# haasoscope_pro_fpga_board.net
KiCad netlist of a schematic drawn in EAGLE
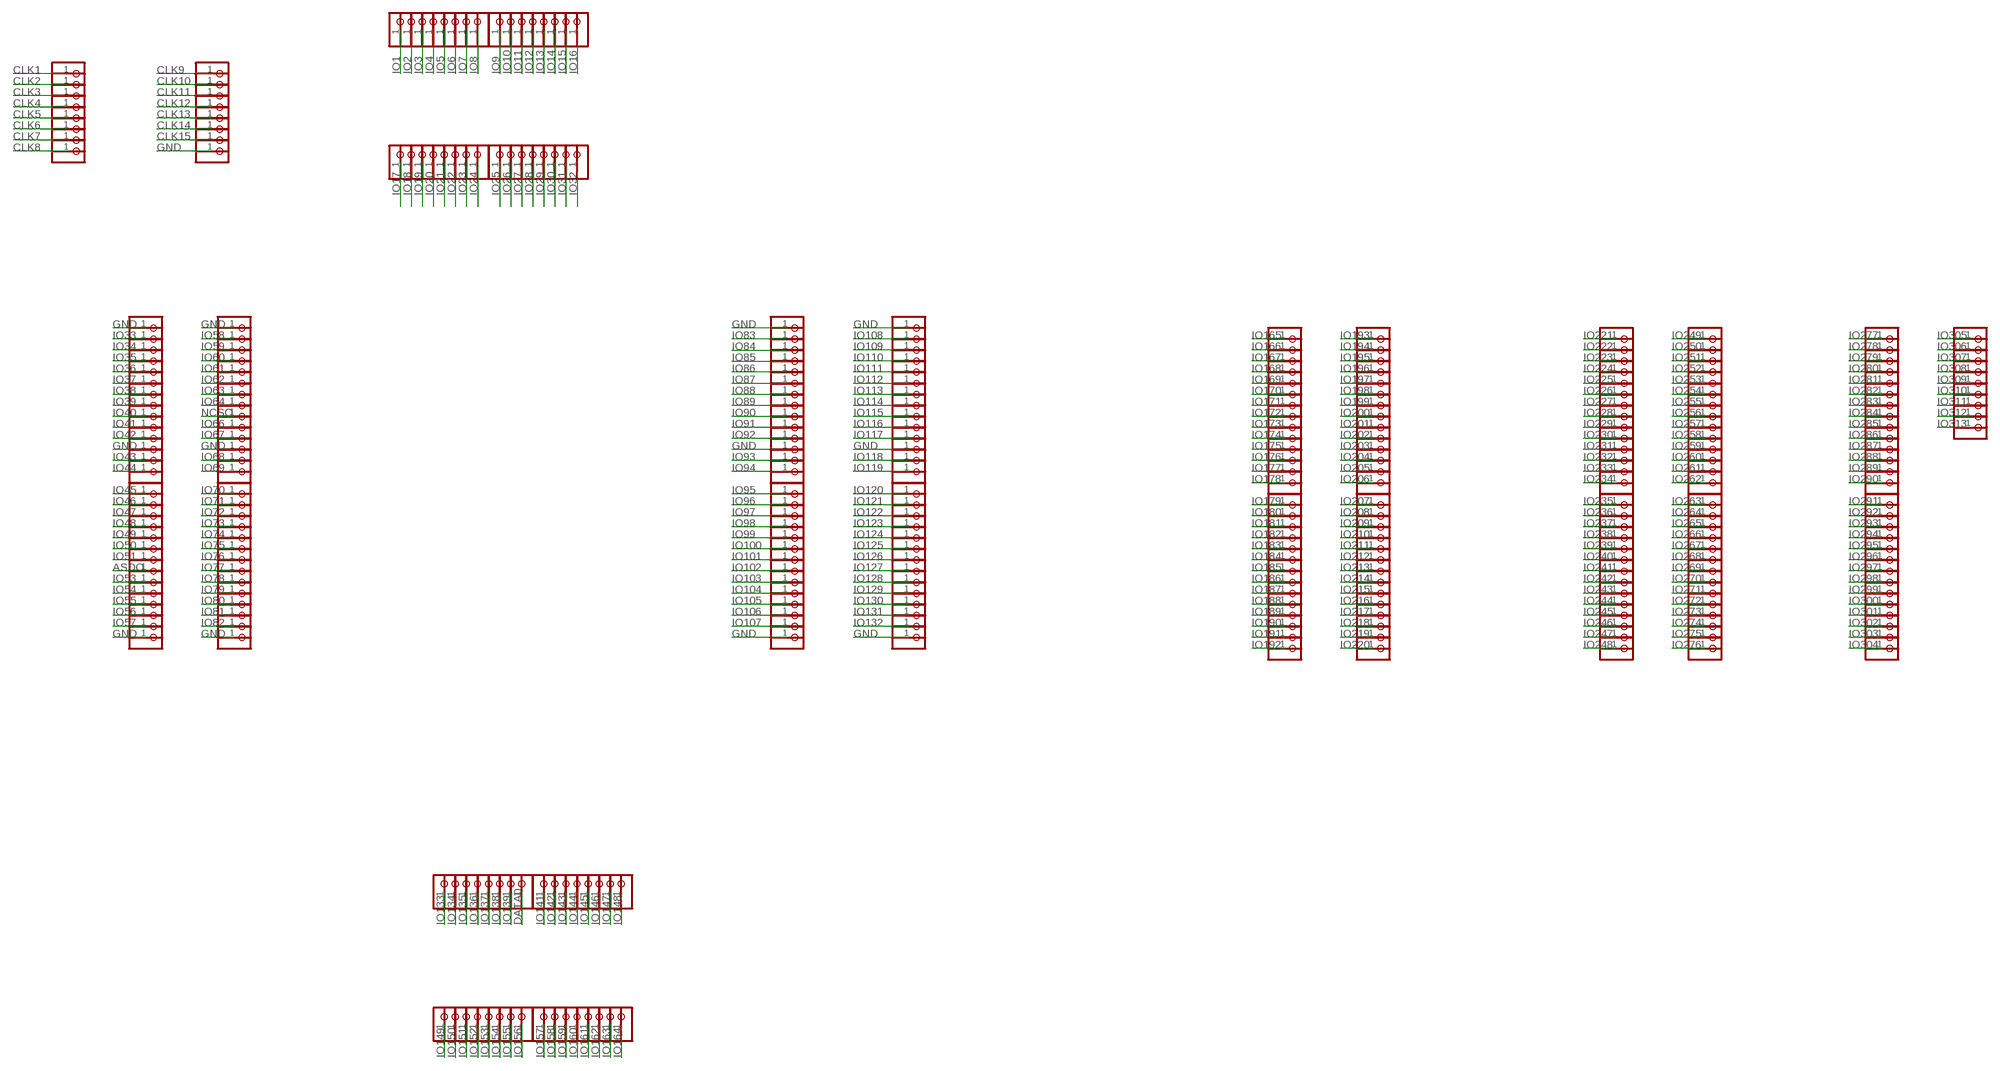
[diagram p0: schematic, sheet 1]
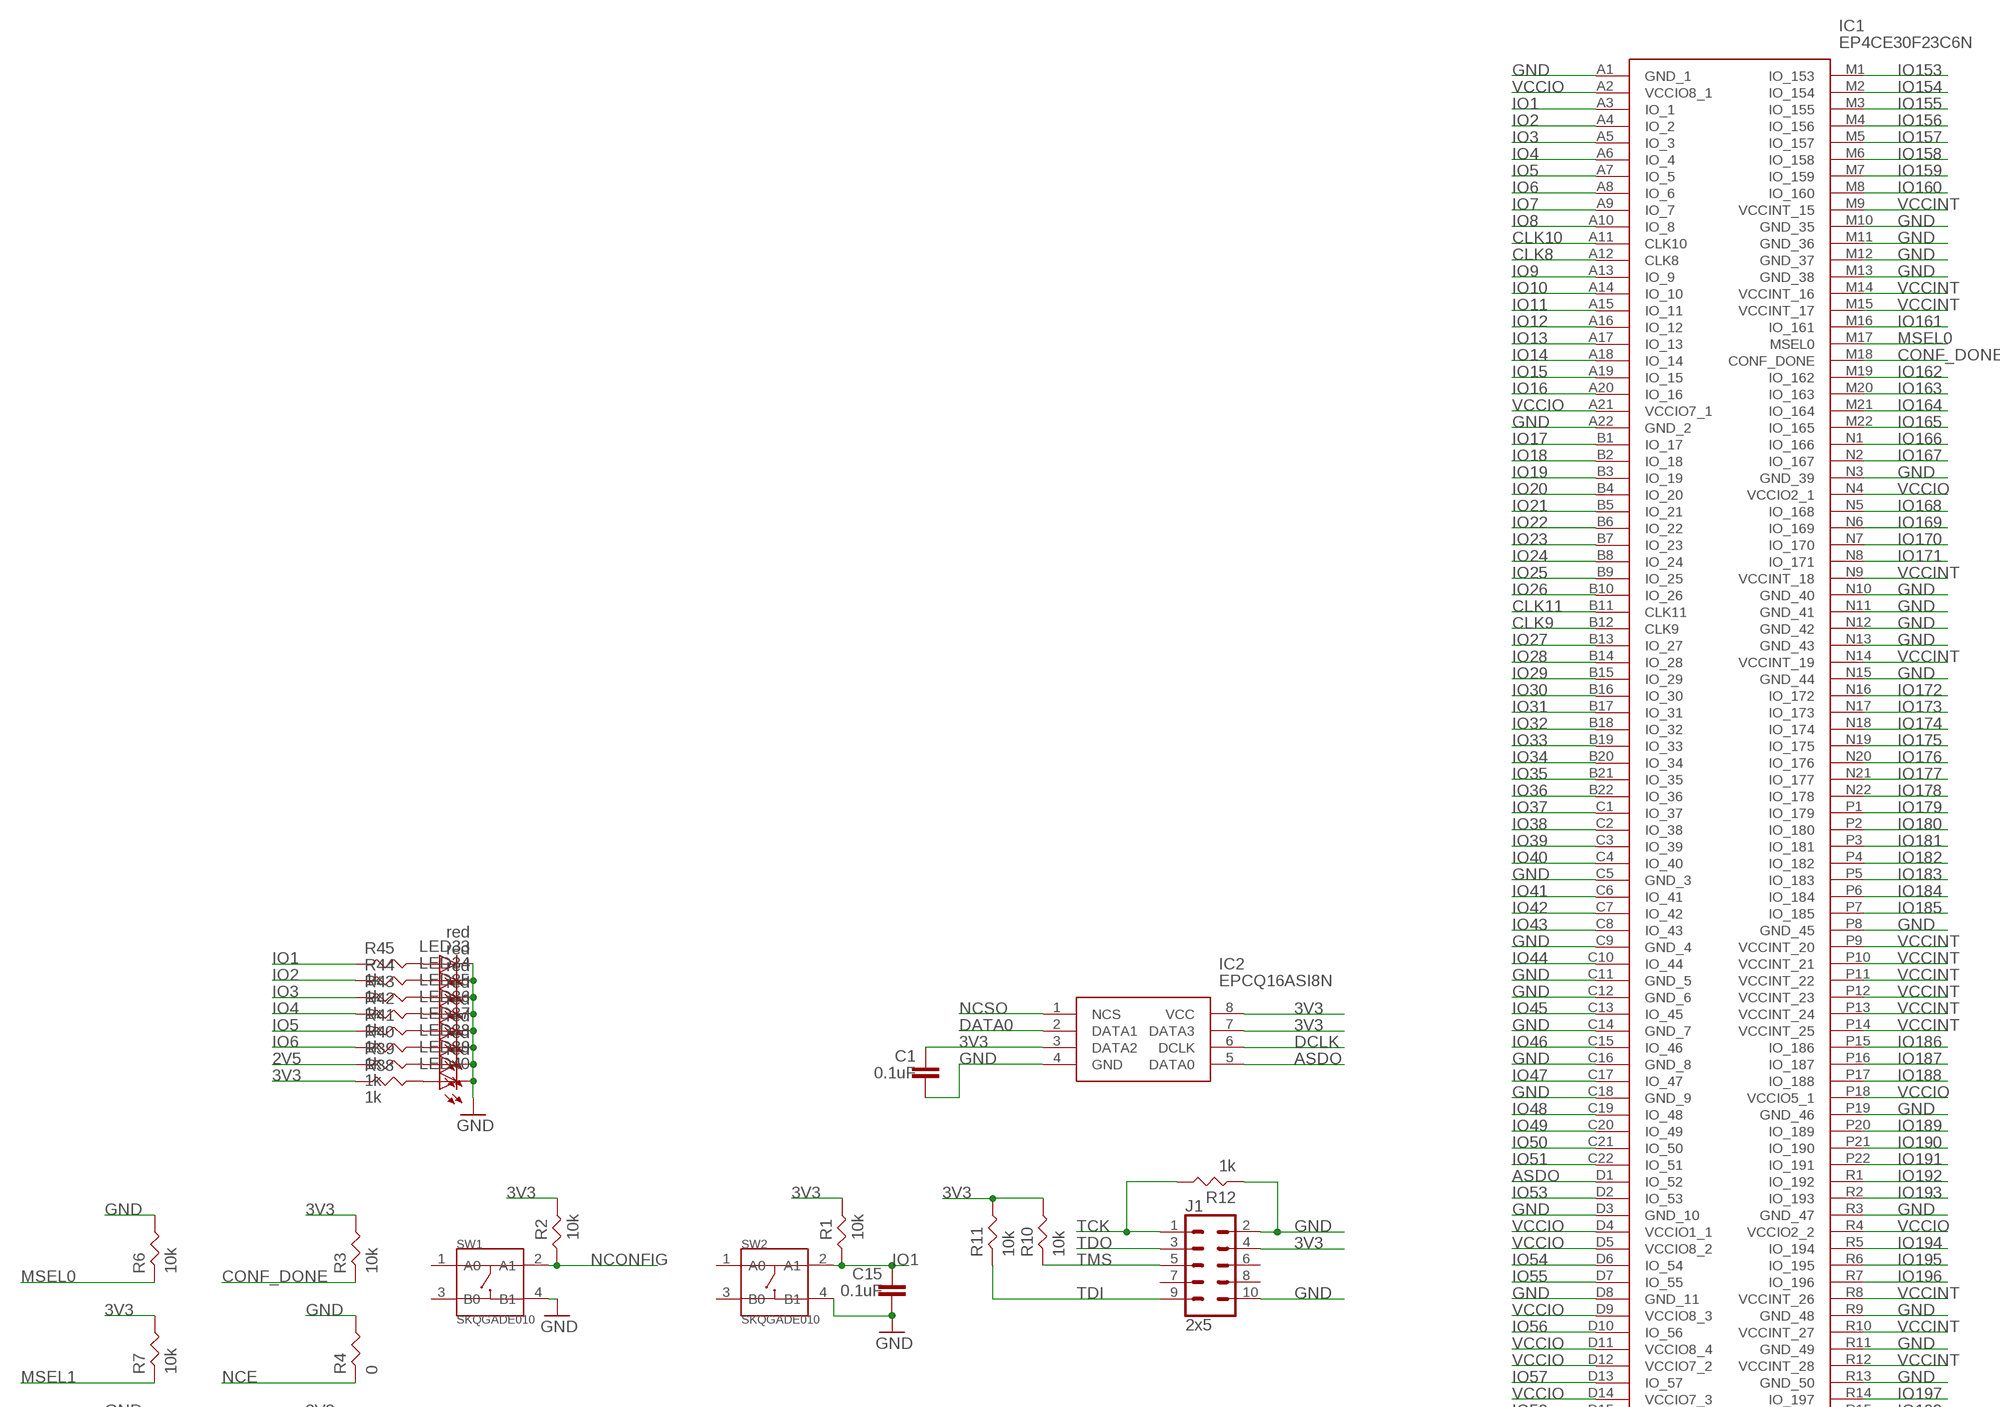
[diagram p1: schematic, sheet 2, part 1 of 2]
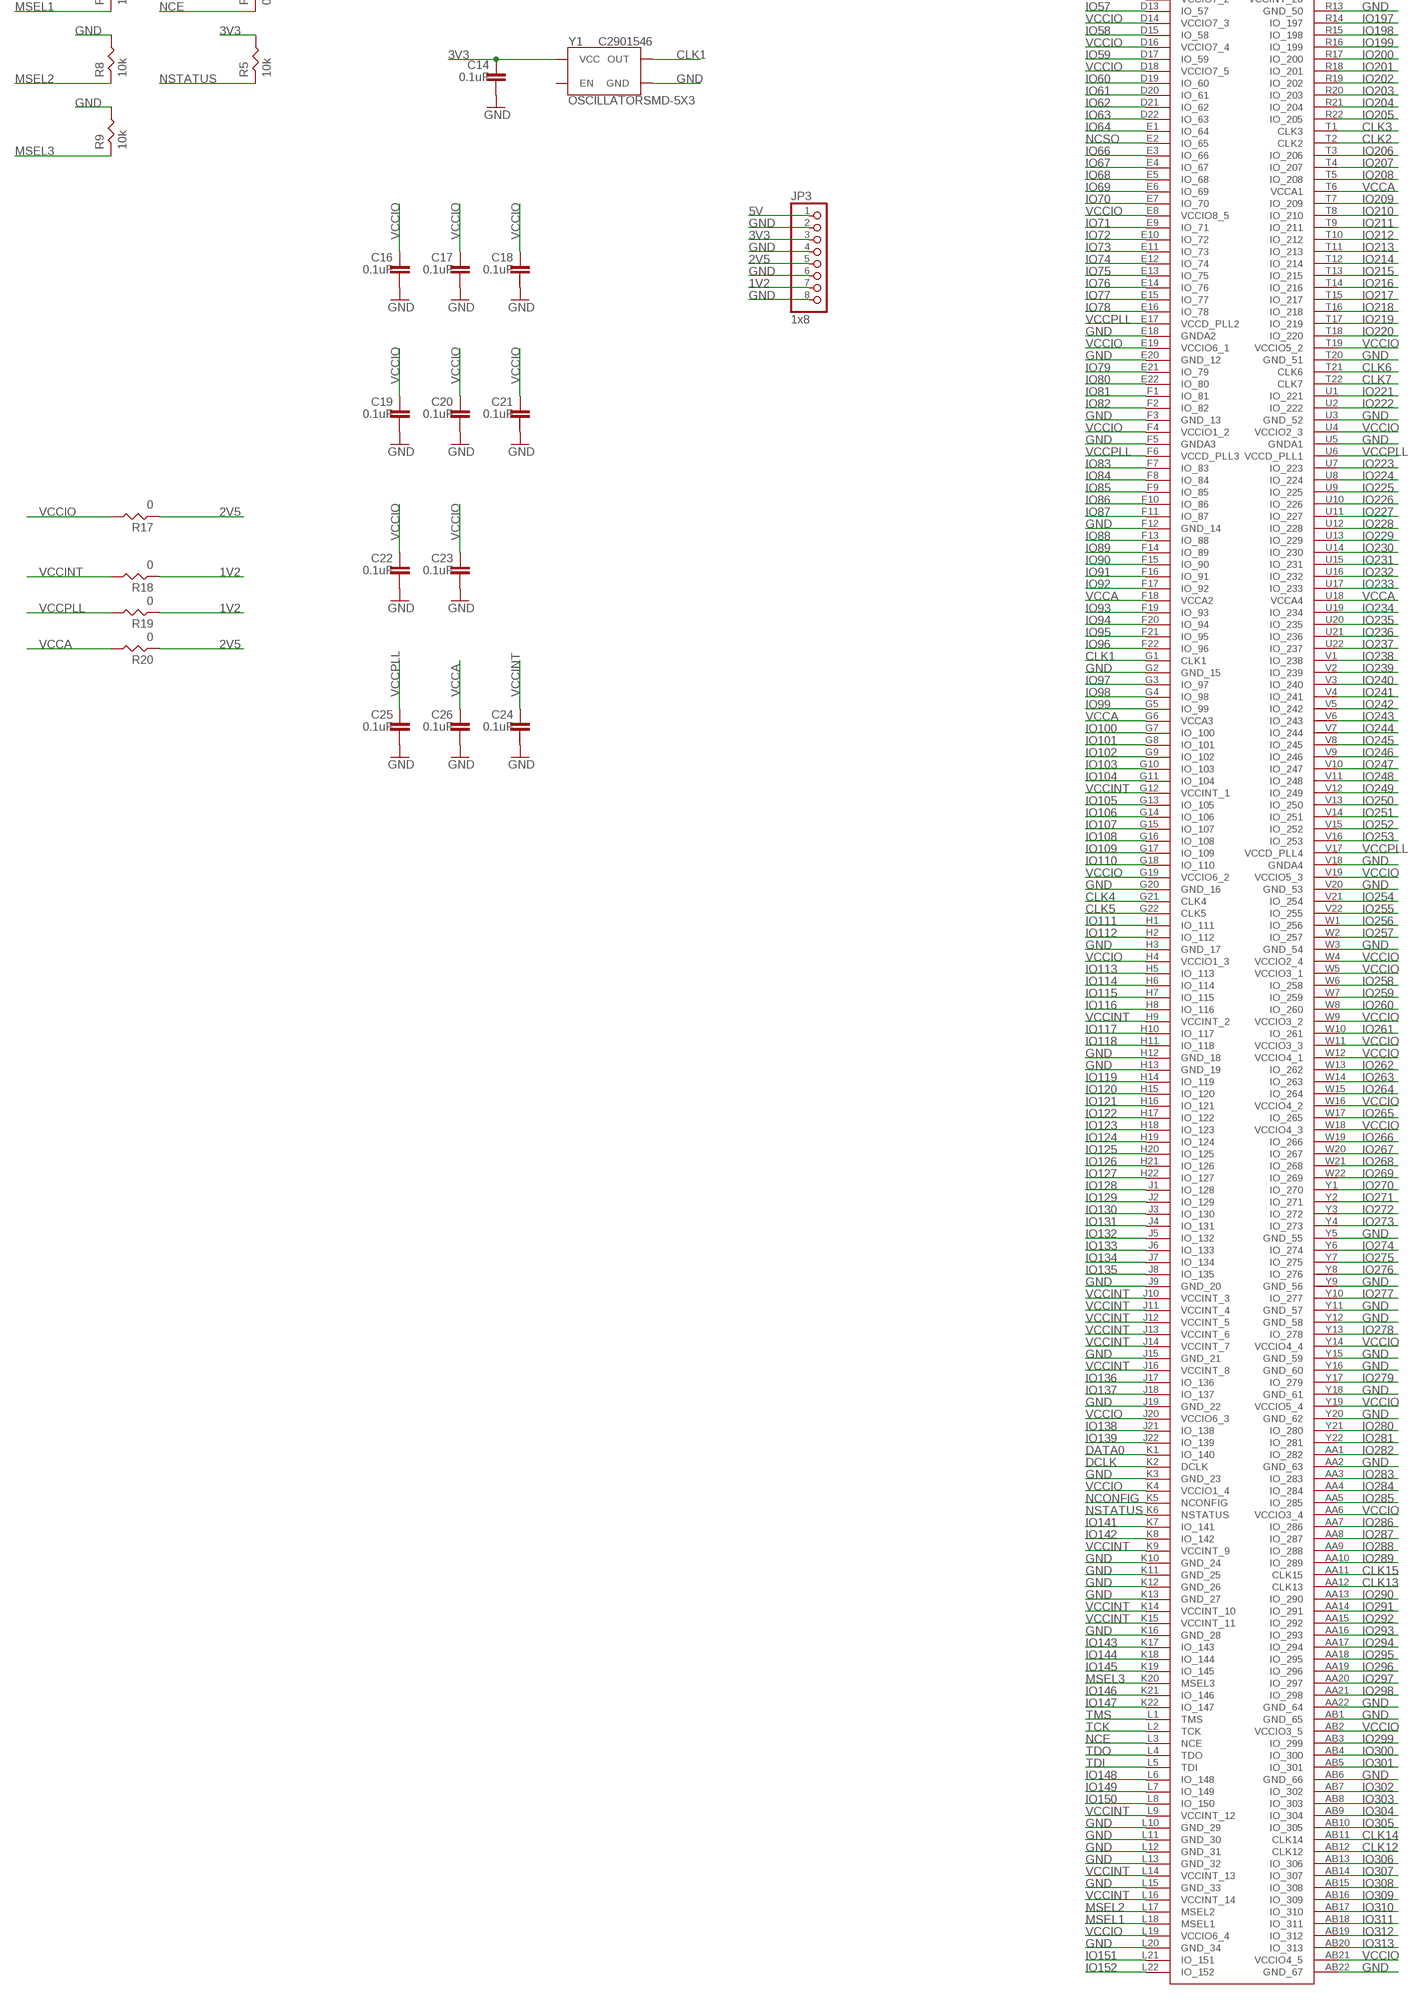
[diagram p2: schematic, sheet 2, part 2 of 2]
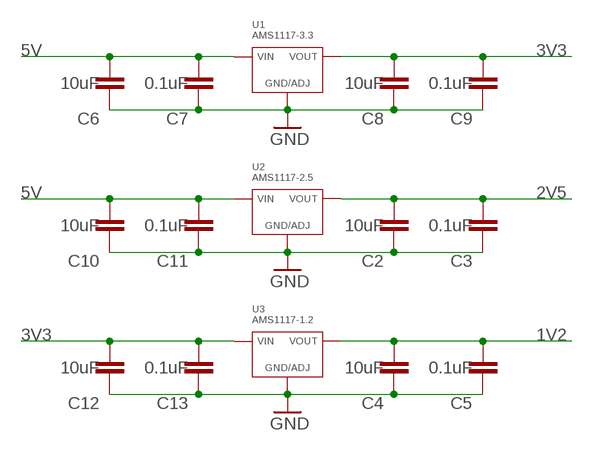
[diagram p3: schematic, sheet 3]

(export (version "E")
  (design (tool "Eeschema 10.0.6"))
  (components
    (comp (ref "C2")
      (value "10uF")
      (footprint "eagle-import:RESC0805_N")
      (libsource (lib "eagle-import") (part "CAPACITOR_0805_N"))
    )
    (comp (ref "C3")
      (value "0.1uF")
      (footprint "eagle-import:RESC0402_N")
      (libsource (lib "eagle-import") (part "CAPACITOR_0402_N"))
    )
    (comp (ref "C4")
      (value "10uF")
      (footprint "eagle-import:RESC0805_N")
      (libsource (lib "eagle-import") (part "CAPACITOR_0805_N"))
    )
    (comp (ref "C5")
      (value "0.1uF")
      (footprint "eagle-import:RESC0402_N")
      (libsource (lib "eagle-import") (part "CAPACITOR_0402_N"))
    )
    (comp (ref "C6")
      (value "10uF")
      (footprint "eagle-import:RESC0805_N")
      (libsource (lib "eagle-import") (part "CAPACITOR_0805_N"))
    )
    (comp (ref "C7")
      (value "0.1uF")
      (footprint "eagle-import:RESC0402_N")
      (libsource (lib "eagle-import") (part "CAPACITOR_0402_N"))
    )
    (comp (ref "C8")
      (value "10uF")
      (footprint "eagle-import:RESC0805_N")
      (libsource (lib "eagle-import") (part "CAPACITOR_0805_N"))
    )
    (comp (ref "C9")
      (value "0.1uF")
      (footprint "eagle-import:RESC0402_N")
      (libsource (lib "eagle-import") (part "CAPACITOR_0402_N"))
    )
    (comp (ref "C10")
      (value "10uF")
      (footprint "eagle-import:RESC0805_N")
      (libsource (lib "eagle-import") (part "CAPACITOR_0805_N"))
    )
    (comp (ref "C11")
      (value "0.1uF")
      (footprint "eagle-import:RESC0402_N")
      (libsource (lib "eagle-import") (part "CAPACITOR_0402_N"))
    )
    (comp (ref "C12")
      (value "10uF")
      (footprint "eagle-import:RESC0805_N")
      (libsource (lib "eagle-import") (part "CAPACITOR_0805_N"))
    )
    (comp (ref "C13")
      (value "0.1uF")
      (footprint "eagle-import:RESC0402_N")
      (libsource (lib "eagle-import") (part "CAPACITOR_0402_N"))
    )
    (comp (ref "U1")
      (value "AMS1117-3.3")
      (footprint "eagle-import:SOT-223-3")
      (fields
        (field (name "HOUSEPART") "NO")
        (field (name "MPN") "NCP1117LPST33T3G")
        (field (name "MPN_1") "AMS1117-3.3")
      )
      (libsource (lib "eagle-import") (part "NCP1117LPST33T3G"))
    )
    (comp (ref "U2")
      (value "AMS1117-2.5")
      (footprint "eagle-import:SOT-223-3")
      (fields
        (field (name "HOUSEPART") "NO")
        (field (name "MPN") "NCP1117LPST33T3G")
        (field (name "MPN_1") "AMS1117-2.5")
      )
      (libsource (lib "eagle-import") (part "NCP1117LPST33T3G"))
    )
    (comp (ref "U3")
      (value "AMS1117-1.2")
      (footprint "eagle-import:SOT-223-3")
      (fields
        (field (name "HOUSEPART") "NO")
        (field (name "MPN") "NCP1117LPST33T3G")
        (field (name "MPN_1") "AMS1117-1.2")
      )
      (libsource (lib "eagle-import") (part "NCP1117LPST33T3G"))
    )
    (comp (ref "C1")
      (value "0.1uF")
      (footprint "eagle-import:RESC0402_N")
      (libsource (lib "eagle-import") (part "CAPACITOR_0402_N"))
    )
    (comp (ref "C14")
      (value "0.1uF")
      (footprint "eagle-import:RESC0402_N")
      (libsource (lib "eagle-import") (part "CAPACITOR_0402_N"))
    )
    (comp (ref "C15")
      (value "0.1uF")
      (footprint "eagle-import:RESC0402_N")
      (libsource (lib "eagle-import") (part "CAPACITOR_0402_N"))
    )
    (comp (ref "C16")
      (value "0.1uF")
      (footprint "eagle-import:RESC0402_N")
      (libsource (lib "eagle-import") (part "CAPACITOR_0402_N"))
    )
    (comp (ref "C17")
      (value "0.1uF")
      (footprint "eagle-import:RESC0402_N")
      (libsource (lib "eagle-import") (part "CAPACITOR_0402_N"))
    )
    (comp (ref "C18")
      (value "0.1uF")
      (footprint "eagle-import:RESC0402_N")
      (libsource (lib "eagle-import") (part "CAPACITOR_0402_N"))
    )
    (comp (ref "C19")
      (value "0.1uF")
      (footprint "eagle-import:RESC0402_N")
      (libsource (lib "eagle-import") (part "CAPACITOR_0402_N"))
    )
    (comp (ref "C20")
      (value "0.1uF")
      (footprint "eagle-import:RESC0402_N")
      (libsource (lib "eagle-import") (part "CAPACITOR_0402_N"))
    )
    (comp (ref "C21")
      (value "0.1uF")
      (footprint "eagle-import:RESC0402_N")
      (libsource (lib "eagle-import") (part "CAPACITOR_0402_N"))
    )
    (comp (ref "C22")
      (value "0.1uF")
      (footprint "eagle-import:RESC0402_N")
      (libsource (lib "eagle-import") (part "CAPACITOR_0402_N"))
    )
    (comp (ref "C23")
      (value "0.1uF")
      (footprint "eagle-import:RESC0402_N")
      (libsource (lib "eagle-import") (part "CAPACITOR_0402_N"))
    )
    (comp (ref "C24")
      (value "0.1uF")
      (footprint "eagle-import:RESC0402_N")
      (libsource (lib "eagle-import") (part "CAPACITOR_0402_N"))
    )
    (comp (ref "C25")
      (value "0.1uF")
      (footprint "eagle-import:RESC0402_N")
      (libsource (lib "eagle-import") (part "CAPACITOR_0402_N"))
    )
    (comp (ref "C26")
      (value "0.1uF")
      (footprint "eagle-import:RESC0402_N")
      (libsource (lib "eagle-import") (part "CAPACITOR_0402_N"))
    )
    (comp (ref "IC1")
      (value "EP4CE30F23C6N")
      (footprint "eagle-import:BGA484C100P22X22_2300X2300X240")
      (fields (field (name "MOUSER_PART_NUMBER") "989-EP4CE30F23C6N"))
      (libsource (lib "eagle-import") (part "EP4CE30F23C6N"))
    )
    (comp (ref "IC2")
      (value "EPCQ16ASI8N")
      (footprint "eagle-import:SOIC127P600X175-8N")
      (fields (field (name "MOUSER_PART_NUMBER") "989-EPCQ16ASI8N"))
      (libsource (lib "eagle-import") (part "EPCQ16ASI8N"))
    )
    (comp (ref "J1")
      (value "2x5")
      (footprint "eagle-import:2X5-SHROUDED")
      (libsource (lib "eagle-import") (part "CONN_05X2SHD"))
    )
    (comp (ref "JP3")
      (value "1x8")
      (footprint "eagle-import:1X08")
      (libsource (lib "eagle-import") (part "PINHD-1X8"))
    )
    (comp (ref "LED33")
      (value "red")
      (footprint "eagle-import:CHIP-LED0603")
      (libsource (lib "eagle-import") (part "LEDCHIP-LED0603"))
    )
    (comp (ref "LED34")
      (value "red")
      (footprint "eagle-import:CHIP-LED0603")
      (libsource (lib "eagle-import") (part "LEDCHIP-LED0603"))
    )
    (comp (ref "LED35")
      (value "red")
      (footprint "eagle-import:CHIP-LED0603")
      (libsource (lib "eagle-import") (part "LEDCHIP-LED0603"))
    )
    (comp (ref "LED36")
      (value "red")
      (footprint "eagle-import:CHIP-LED0603")
      (libsource (lib "eagle-import") (part "LEDCHIP-LED0603"))
    )
    (comp (ref "LED37")
      (value "red")
      (footprint "eagle-import:CHIP-LED0603")
      (libsource (lib "eagle-import") (part "LEDCHIP-LED0603"))
    )
    (comp (ref "LED38")
      (value "red")
      (footprint "eagle-import:CHIP-LED0603")
      (libsource (lib "eagle-import") (part "LEDCHIP-LED0603"))
    )
    (comp (ref "LED39")
      (value "red")
      (footprint "eagle-import:CHIP-LED0603")
      (libsource (lib "eagle-import") (part "LEDCHIP-LED0603"))
    )
    (comp (ref "LED40")
      (value "red")
      (footprint "eagle-import:CHIP-LED0603")
      (libsource (lib "eagle-import") (part "LEDCHIP-LED0603"))
    )
    (comp (ref "R1")
      (value "10k")
      (footprint "eagle-import:RES-0402")
      (libsource (lib "eagle-import") (part "RES-0402"))
    )
    (comp (ref "R2")
      (value "10k")
      (footprint "eagle-import:RES-0402")
      (libsource (lib "eagle-import") (part "RES-0402"))
    )
    (comp (ref "R3")
      (value "10k")
      (footprint "eagle-import:RES-0402")
      (libsource (lib "eagle-import") (part "RES-0402"))
    )
    (comp (ref "R4")
      (value "0")
      (footprint "eagle-import:RES-0402")
      (libsource (lib "eagle-import") (part "RES-0402"))
    )
    (comp (ref "R5")
      (value "10k")
      (footprint "eagle-import:RES-0402")
      (libsource (lib "eagle-import") (part "RES-0402"))
    )
    (comp (ref "R6")
      (value "10k")
      (footprint "eagle-import:RES-0402")
      (libsource (lib "eagle-import") (part "RES-0402"))
    )
    (comp (ref "R7")
      (value "10k")
      (footprint "eagle-import:RES-0402")
      (libsource (lib "eagle-import") (part "RES-0402"))
    )
    (comp (ref "R8")
      (value "10k")
      (footprint "eagle-import:RES-0402")
      (libsource (lib "eagle-import") (part "RES-0402"))
    )
    (comp (ref "R9")
      (value "10k")
      (footprint "eagle-import:RES-0402")
      (libsource (lib "eagle-import") (part "RES-0402"))
    )
    (comp (ref "R10")
      (value "10k")
      (footprint "eagle-import:RES-0402")
      (libsource (lib "eagle-import") (part "RES-0402"))
    )
    (comp (ref "R11")
      (value "10k")
      (footprint "eagle-import:RES-0402")
      (libsource (lib "eagle-import") (part "RES-0402"))
    )
    (comp (ref "R12")
      (value "1k")
      (footprint "eagle-import:RES-0402")
      (libsource (lib "eagle-import") (part "RES-0402"))
    )
    (comp (ref "R17")
      (value "0")
      (footprint "eagle-import:RES-0402")
      (libsource (lib "eagle-import") (part "RES-0402"))
    )
    (comp (ref "R18")
      (value "0")
      (footprint "eagle-import:RES-0402")
      (libsource (lib "eagle-import") (part "RES-0402"))
    )
    (comp (ref "R19")
      (value "0")
      (footprint "eagle-import:RES-0402")
      (libsource (lib "eagle-import") (part "RES-0402"))
    )
    (comp (ref "R20")
      (value "0")
      (footprint "eagle-import:RES-0402")
      (libsource (lib "eagle-import") (part "RES-0402"))
    )
    (comp (ref "R38")
      (value "1k")
      (footprint "eagle-import:RES-0402")
      (libsource (lib "eagle-import") (part "RES-0402"))
    )
    (comp (ref "R39")
      (value "1k")
      (footprint "eagle-import:RES-0402")
      (libsource (lib "eagle-import") (part "RES-0402"))
    )
    (comp (ref "R40")
      (value "1k")
      (footprint "eagle-import:RES-0402")
      (libsource (lib "eagle-import") (part "RES-0402"))
    )
    (comp (ref "R41")
      (value "1k")
      (footprint "eagle-import:RES-0402")
      (libsource (lib "eagle-import") (part "RES-0402"))
    )
    (comp (ref "R42")
      (value "1k")
      (footprint "eagle-import:RES-0402")
      (libsource (lib "eagle-import") (part "RES-0402"))
    )
    (comp (ref "R43")
      (value "1k")
      (footprint "eagle-import:RES-0402")
      (libsource (lib "eagle-import") (part "RES-0402"))
    )
    (comp (ref "R44")
      (value "1k")
      (footprint "eagle-import:RES-0402")
      (libsource (lib "eagle-import") (part "RES-0402"))
    )
    (comp (ref "R45")
      (value "1k")
      (footprint "eagle-import:RES-0402")
      (libsource (lib "eagle-import") (part "RES-0402"))
    )
    (comp (ref "SW1")
      (value "SKQGADE010")
      (footprint "eagle-import:SW4-SMD-5.2X5.2X1.5MM")
      (libsource (lib "eagle-import") (part "SMD-BUTTON(4P-5.2X5.2X1.5MM-SKQGADE010)-SKQGADE010"))
    )
    (comp (ref "SW2")
      (value "SKQGADE010")
      (footprint "eagle-import:SW4-SMD-5.2X5.2X1.5MM")
      (libsource (lib "eagle-import") (part "SMD-BUTTON(4P-5.2X5.2X1.5MM-SKQGADE010)-SKQGADE010"))
    )
    (comp (ref "Y1")
      (value "OSCILLATORSMD-5X3")
      (footprint "eagle-import:OSCILLATOR-SMD-5X3.2")
      (fields (field (name "LCSC") "C2901546"))
      (libsource (lib "eagle-import") (part "OSCILLATORSMD-5X3"))
    )
    (comp (ref "JP1")
      (value "1")
      (footprint "eagle-import:1X01")
      (libsource (lib "eagle-import") (part "PINHD-1X1"))
    )
    (comp (ref "JP2")
      (value "1")
      (footprint "eagle-import:1X01")
      (libsource (lib "eagle-import") (part "PINHD-1X1"))
    )
    (comp (ref "JP4")
      (value "1")
      (footprint "eagle-import:1X01")
      (libsource (lib "eagle-import") (part "PINHD-1X1"))
    )
    (comp (ref "JP5")
      (value "1")
      (footprint "eagle-import:1X01")
      (libsource (lib "eagle-import") (part "PINHD-1X1"))
    )
    (comp (ref "JP6")
      (value "1")
      (footprint "eagle-import:1X01")
      (libsource (lib "eagle-import") (part "PINHD-1X1"))
    )
    (comp (ref "JP7")
      (value "1")
      (footprint "eagle-import:1X01")
      (libsource (lib "eagle-import") (part "PINHD-1X1"))
    )
    (comp (ref "JP8")
      (value "1")
      (footprint "eagle-import:1X01")
      (libsource (lib "eagle-import") (part "PINHD-1X1"))
    )
    (comp (ref "JP9")
      (value "1")
      (footprint "eagle-import:1X01")
      (libsource (lib "eagle-import") (part "PINHD-1X1"))
    )
    (comp (ref "JP10")
      (value "1")
      (footprint "eagle-import:1X01")
      (libsource (lib "eagle-import") (part "PINHD-1X1"))
    )
    (comp (ref "JP11")
      (value "1")
      (footprint "eagle-import:1X01")
      (libsource (lib "eagle-import") (part "PINHD-1X1"))
    )
    (comp (ref "JP12")
      (value "1")
      (footprint "eagle-import:1X01")
      (libsource (lib "eagle-import") (part "PINHD-1X1"))
    )
    (comp (ref "JP13")
      (value "1")
      (footprint "eagle-import:1X01")
      (libsource (lib "eagle-import") (part "PINHD-1X1"))
    )
    (comp (ref "JP14")
      (value "1")
      (footprint "eagle-import:1X01")
      (libsource (lib "eagle-import") (part "PINHD-1X1"))
    )
    (comp (ref "JP15")
      (value "1")
      (footprint "eagle-import:1X01")
      (libsource (lib "eagle-import") (part "PINHD-1X1"))
    )
    (comp (ref "JP16")
      (value "1")
      (footprint "eagle-import:1X01")
      (libsource (lib "eagle-import") (part "PINHD-1X1"))
    )
    (comp (ref "JP17")
      (value "1")
      (footprint "eagle-import:1X01")
      (libsource (lib "eagle-import") (part "PINHD-1X1"))
    )
    (comp (ref "JP18")
      (value "1")
      (footprint "eagle-import:1X01")
      (libsource (lib "eagle-import") (part "PINHD-1X1"))
    )
    (comp (ref "JP19")
      (value "1")
      (footprint "eagle-import:1X01")
      (libsource (lib "eagle-import") (part "PINHD-1X1"))
    )
    (comp (ref "JP20")
      (value "1")
      (footprint "eagle-import:1X01")
      (libsource (lib "eagle-import") (part "PINHD-1X1"))
    )
    (comp (ref "JP21")
      (value "1")
      (footprint "eagle-import:1X01")
      (libsource (lib "eagle-import") (part "PINHD-1X1"))
    )
    (comp (ref "JP22")
      (value "1")
      (footprint "eagle-import:1X01")
      (libsource (lib "eagle-import") (part "PINHD-1X1"))
    )
    (comp (ref "JP23")
      (value "1")
      (footprint "eagle-import:1X01")
      (libsource (lib "eagle-import") (part "PINHD-1X1"))
    )
    (comp (ref "JP24")
      (value "1")
      (footprint "eagle-import:1X01")
      (libsource (lib "eagle-import") (part "PINHD-1X1"))
    )
    (comp (ref "JP25")
      (value "1")
      (footprint "eagle-import:1X01")
      (libsource (lib "eagle-import") (part "PINHD-1X1"))
    )
    (comp (ref "JP26")
      (value "1")
      (footprint "eagle-import:1X01")
      (libsource (lib "eagle-import") (part "PINHD-1X1"))
    )
    (comp (ref "JP27")
      (value "1")
      (footprint "eagle-import:1X01")
      (libsource (lib "eagle-import") (part "PINHD-1X1"))
    )
    (comp (ref "JP28")
      (value "1")
      (footprint "eagle-import:1X01")
      (libsource (lib "eagle-import") (part "PINHD-1X1"))
    )
    (comp (ref "JP29")
      (value "1")
      (footprint "eagle-import:1X01")
      (libsource (lib "eagle-import") (part "PINHD-1X1"))
    )
    (comp (ref "JP30")
      (value "1")
      (footprint "eagle-import:1X01")
      (libsource (lib "eagle-import") (part "PINHD-1X1"))
    )
    (comp (ref "JP31")
      (value "1")
      (footprint "eagle-import:1X01")
      (libsource (lib "eagle-import") (part "PINHD-1X1"))
    )
    (comp (ref "JP32")
      (value "1")
      (footprint "eagle-import:1X01")
      (libsource (lib "eagle-import") (part "PINHD-1X1"))
    )
    (comp (ref "JP33")
      (value "1")
      (footprint "eagle-import:1X01")
      (libsource (lib "eagle-import") (part "PINHD-1X1"))
    )
    (comp (ref "JP34")
      (value "1")
      (footprint "eagle-import:1X01")
      (libsource (lib "eagle-import") (part "PINHD-1X1"))
    )
    (comp (ref "JP35")
      (value "1")
      (footprint "eagle-import:1X01")
      (libsource (lib "eagle-import") (part "PINHD-1X1"))
    )
    (comp (ref "JP36")
      (value "1")
      (footprint "eagle-import:1X01")
      (libsource (lib "eagle-import") (part "PINHD-1X1"))
    )
    (comp (ref "JP37")
      (value "1")
      (footprint "eagle-import:1X01")
      (libsource (lib "eagle-import") (part "PINHD-1X1"))
    )
    (comp (ref "JP38")
      (value "1")
      (footprint "eagle-import:1X01")
      (libsource (lib "eagle-import") (part "PINHD-1X1"))
    )
    (comp (ref "JP39")
      (value "1")
      (footprint "eagle-import:1X01")
      (libsource (lib "eagle-import") (part "PINHD-1X1"))
    )
    (comp (ref "JP40")
      (value "1")
      (footprint "eagle-import:1X01")
      (libsource (lib "eagle-import") (part "PINHD-1X1"))
    )
    (comp (ref "JP41")
      (value "1")
      (footprint "eagle-import:1X01")
      (libsource (lib "eagle-import") (part "PINHD-1X1"))
    )
    (comp (ref "JP42")
      (value "1")
      (footprint "eagle-import:1X01")
      (libsource (lib "eagle-import") (part "PINHD-1X1"))
    )
    (comp (ref "JP43")
      (value "1")
      (footprint "eagle-import:1X01")
      (libsource (lib "eagle-import") (part "PINHD-1X1"))
    )
    (comp (ref "JP44")
      (value "1")
      (footprint "eagle-import:1X01")
      (libsource (lib "eagle-import") (part "PINHD-1X1"))
    )
    (comp (ref "JP45")
      (value "1")
      (footprint "eagle-import:1X01")
      (libsource (lib "eagle-import") (part "PINHD-1X1"))
    )
    (comp (ref "JP46")
      (value "1")
      (footprint "eagle-import:1X01")
      (libsource (lib "eagle-import") (part "PINHD-1X1"))
    )
    (comp (ref "JP47")
      (value "1")
      (footprint "eagle-import:1X01")
      (libsource (lib "eagle-import") (part "PINHD-1X1"))
    )
    (comp (ref "JP48")
      (value "1")
      (footprint "eagle-import:1X01")
      (libsource (lib "eagle-import") (part "PINHD-1X1"))
    )
    (comp (ref "JP49")
      (value "1")
      (footprint "eagle-import:1X01")
      (libsource (lib "eagle-import") (part "PINHD-1X1"))
    )
    (comp (ref "JP50")
      (value "1")
      (footprint "eagle-import:1X01")
      (libsource (lib "eagle-import") (part "PINHD-1X1"))
    )
    (comp (ref "JP51")
      (value "1")
      (footprint "eagle-import:1X01")
      (libsource (lib "eagle-import") (part "PINHD-1X1"))
    )
    (comp (ref "JP52")
      (value "1")
      (footprint "eagle-import:1X01")
      (libsource (lib "eagle-import") (part "PINHD-1X1"))
    )
    (comp (ref "JP53")
      (value "1")
      (footprint "eagle-import:1X01")
      (libsource (lib "eagle-import") (part "PINHD-1X1"))
    )
    (comp (ref "JP54")
      (value "1")
      (footprint "eagle-import:1X01")
      (libsource (lib "eagle-import") (part "PINHD-1X1"))
    )
    (comp (ref "JP55")
      (value "1")
      (footprint "eagle-import:1X01")
      (libsource (lib "eagle-import") (part "PINHD-1X1"))
    )
    (comp (ref "JP56")
      (value "1")
      (footprint "eagle-import:1X01")
      (libsource (lib "eagle-import") (part "PINHD-1X1"))
    )
    (comp (ref "JP57")
      (value "1")
      (footprint "eagle-import:1X01")
      (libsource (lib "eagle-import") (part "PINHD-1X1"))
    )
    (comp (ref "JP58")
      (value "1")
      (footprint "eagle-import:1X01")
      (libsource (lib "eagle-import") (part "PINHD-1X1"))
    )
    (comp (ref "JP59")
      (value "1")
      (footprint "eagle-import:1X01")
      (libsource (lib "eagle-import") (part "PINHD-1X1"))
    )
    (comp (ref "JP60")
      (value "1")
      (footprint "eagle-import:1X01")
      (libsource (lib "eagle-import") (part "PINHD-1X1"))
    )
    (comp (ref "JP61")
      (value "1")
      (footprint "eagle-import:1X01")
      (libsource (lib "eagle-import") (part "PINHD-1X1"))
    )
    (comp (ref "JP62")
      (value "1")
      (footprint "eagle-import:1X01")
      (libsource (lib "eagle-import") (part "PINHD-1X1"))
    )
    (comp (ref "JP63")
      (value "1")
      (footprint "eagle-import:1X01")
      (libsource (lib "eagle-import") (part "PINHD-1X1"))
    )
    (comp (ref "JP64")
      (value "1")
      (footprint "eagle-import:1X01")
      (libsource (lib "eagle-import") (part "PINHD-1X1"))
    )
    (comp (ref "JP65")
      (value "1")
      (footprint "eagle-import:1X01")
      (libsource (lib "eagle-import") (part "PINHD-1X1"))
    )
    (comp (ref "JP66")
      (value "1")
      (footprint "eagle-import:1X01")
      (libsource (lib "eagle-import") (part "PINHD-1X1"))
    )
    (comp (ref "JP67")
      (value "1")
      (footprint "eagle-import:1X01")
      (libsource (lib "eagle-import") (part "PINHD-1X1"))
    )
    (comp (ref "JP68")
      (value "1")
      (footprint "eagle-import:1X01")
      (libsource (lib "eagle-import") (part "PINHD-1X1"))
    )
    (comp (ref "JP69")
      (value "1")
      (footprint "eagle-import:1X01")
      (libsource (lib "eagle-import") (part "PINHD-1X1"))
    )
    (comp (ref "JP70")
      (value "1")
      (footprint "eagle-import:1X01")
      (libsource (lib "eagle-import") (part "PINHD-1X1"))
    )
    (comp (ref "JP71")
      (value "1")
      (footprint "eagle-import:1X01")
      (libsource (lib "eagle-import") (part "PINHD-1X1"))
    )
    (comp (ref "JP72")
      (value "1")
      (footprint "eagle-import:1X01")
      (libsource (lib "eagle-import") (part "PINHD-1X1"))
    )
    (comp (ref "JP73")
      (value "1")
      (footprint "eagle-import:1X01")
      (libsource (lib "eagle-import") (part "PINHD-1X1"))
    )
    (comp (ref "JP74")
      (value "1")
      (footprint "eagle-import:1X01")
      (libsource (lib "eagle-import") (part "PINHD-1X1"))
    )
    (comp (ref "JP75")
      (value "1")
      (footprint "eagle-import:1X01")
      (libsource (lib "eagle-import") (part "PINHD-1X1"))
    )
    (comp (ref "JP76")
      (value "1")
      (footprint "eagle-import:1X01")
      (libsource (lib "eagle-import") (part "PINHD-1X1"))
    )
    (comp (ref "JP77")
      (value "1")
      (footprint "eagle-import:1X01")
      (libsource (lib "eagle-import") (part "PINHD-1X1"))
    )
    (comp (ref "JP78")
      (value "1")
      (footprint "eagle-import:1X01")
      (libsource (lib "eagle-import") (part "PINHD-1X1"))
    )
    (comp (ref "JP79")
      (value "1")
      (footprint "eagle-import:1X01")
      (libsource (lib "eagle-import") (part "PINHD-1X1"))
    )
    (comp (ref "JP80")
      (value "1")
      (footprint "eagle-import:1X01")
      (libsource (lib "eagle-import") (part "PINHD-1X1"))
    )
    (comp (ref "JP81")
      (value "1")
      (footprint "eagle-import:1X01")
      (libsource (lib "eagle-import") (part "PINHD-1X1"))
    )
    (comp (ref "JP82")
      (value "1")
      (footprint "eagle-import:1X01")
      (libsource (lib "eagle-import") (part "PINHD-1X1"))
    )
    (comp (ref "JP83")
      (value "1")
      (footprint "eagle-import:1X01")
      (libsource (lib "eagle-import") (part "PINHD-1X1"))
    )
    (comp (ref "JP84")
      (value "1")
      (footprint "eagle-import:1X01")
      (libsource (lib "eagle-import") (part "PINHD-1X1"))
    )
    (comp (ref "JP85")
      (value "1")
      (footprint "eagle-import:1X01")
      (libsource (lib "eagle-import") (part "PINHD-1X1"))
    )
    (comp (ref "JP86")
      (value "1")
      (footprint "eagle-import:1X01")
      (libsource (lib "eagle-import") (part "PINHD-1X1"))
    )
    (comp (ref "JP87")
      (value "1")
      (footprint "eagle-import:1X01")
      (libsource (lib "eagle-import") (part "PINHD-1X1"))
    )
    (comp (ref "JP88")
      (value "1")
      (footprint "eagle-import:1X01")
      (libsource (lib "eagle-import") (part "PINHD-1X1"))
    )
    (comp (ref "JP89")
      (value "1")
      (footprint "eagle-import:1X01")
      (libsource (lib "eagle-import") (part "PINHD-1X1"))
    )
    (comp (ref "JP90")
      (value "1")
      (footprint "eagle-import:1X01")
      (libsource (lib "eagle-import") (part "PINHD-1X1"))
    )
    (comp (ref "JP91")
      (value "1")
      (footprint "eagle-import:1X01")
      (libsource (lib "eagle-import") (part "PINHD-1X1"))
    )
    (comp (ref "JP92")
      (value "1")
      (footprint "eagle-import:1X01")
      (libsource (lib "eagle-import") (part "PINHD-1X1"))
    )
    (comp (ref "JP93")
      (value "1")
      (footprint "eagle-import:1X01")
      (libsource (lib "eagle-import") (part "PINHD-1X1"))
    )
    (comp (ref "JP94")
      (value "1")
      (footprint "eagle-import:1X01")
      (libsource (lib "eagle-import") (part "PINHD-1X1"))
    )
    (comp (ref "JP95")
      (value "1")
      (footprint "eagle-import:1X01")
      (libsource (lib "eagle-import") (part "PINHD-1X1"))
    )
    (comp (ref "JP96")
      (value "1")
      (footprint "eagle-import:1X01")
      (libsource (lib "eagle-import") (part "PINHD-1X1"))
    )
    (comp (ref "JP97")
      (value "1")
      (footprint "eagle-import:1X01")
      (libsource (lib "eagle-import") (part "PINHD-1X1"))
    )
    (comp (ref "JP98")
      (value "1")
      (footprint "eagle-import:1X01")
      (libsource (lib "eagle-import") (part "PINHD-1X1"))
    )
    (comp (ref "JP99")
      (value "1")
      (footprint "eagle-import:1X01")
      (libsource (lib "eagle-import") (part "PINHD-1X1"))
    )
    (comp (ref "JP100")
      (value "1")
      (footprint "eagle-import:1X01")
      (libsource (lib "eagle-import") (part "PINHD-1X1"))
    )
    (comp (ref "JP101")
      (value "1")
      (footprint "eagle-import:1X01")
      (libsource (lib "eagle-import") (part "PINHD-1X1"))
    )
    (comp (ref "JP102")
      (value "1")
      (footprint "eagle-import:1X01")
      (libsource (lib "eagle-import") (part "PINHD-1X1"))
    )
    (comp (ref "JP103")
      (value "1")
      (footprint "eagle-import:1X01")
      (libsource (lib "eagle-import") (part "PINHD-1X1"))
    )
    (comp (ref "JP104")
      (value "1")
      (footprint "eagle-import:1X01")
      (libsource (lib "eagle-import") (part "PINHD-1X1"))
    )
    (comp (ref "JP105")
      (value "1")
      (footprint "eagle-import:1X01")
      (libsource (lib "eagle-import") (part "PINHD-1X1"))
    )
    (comp (ref "JP106")
      (value "1")
      (footprint "eagle-import:1X01")
      (libsource (lib "eagle-import") (part "PINHD-1X1"))
    )
    (comp (ref "JP107")
      (value "1")
      (footprint "eagle-import:1X01")
      (libsource (lib "eagle-import") (part "PINHD-1X1"))
    )
    (comp (ref "JP108")
      (value "1")
      (footprint "eagle-import:1X01")
      (libsource (lib "eagle-import") (part "PINHD-1X1"))
    )
    (comp (ref "JP109")
      (value "1")
      (footprint "eagle-import:1X01")
      (libsource (lib "eagle-import") (part "PINHD-1X1"))
    )
    (comp (ref "JP110")
      (value "1")
      (footprint "eagle-import:1X01")
      (libsource (lib "eagle-import") (part "PINHD-1X1"))
    )
    (comp (ref "JP111")
      (value "1")
      (footprint "eagle-import:1X01")
      (libsource (lib "eagle-import") (part "PINHD-1X1"))
    )
    (comp (ref "JP112")
      (value "1")
      (footprint "eagle-import:1X01")
      (libsource (lib "eagle-import") (part "PINHD-1X1"))
    )
    (comp (ref "JP113")
      (value "1")
      (footprint "eagle-import:1X01")
      (libsource (lib "eagle-import") (part "PINHD-1X1"))
    )
    (comp (ref "JP114")
      (value "1")
      (footprint "eagle-import:1X01")
      (libsource (lib "eagle-import") (part "PINHD-1X1"))
    )
    (comp (ref "JP115")
      (value "1")
      (footprint "eagle-import:1X01")
      (libsource (lib "eagle-import") (part "PINHD-1X1"))
    )
    (comp (ref "JP116")
      (value "1")
      (footprint "eagle-import:1X01")
      (libsource (lib "eagle-import") (part "PINHD-1X1"))
    )
    (comp (ref "JP117")
      (value "1")
      (footprint "eagle-import:1X01")
      (libsource (lib "eagle-import") (part "PINHD-1X1"))
    )
    (comp (ref "JP118")
      (value "1")
      (footprint "eagle-import:1X01")
      (libsource (lib "eagle-import") (part "PINHD-1X1"))
    )
    (comp (ref "JP119")
      (value "1")
      (footprint "eagle-import:1X01")
      (libsource (lib "eagle-import") (part "PINHD-1X1"))
    )
    (comp (ref "JP120")
      (value "1")
      (footprint "eagle-import:1X01")
      (libsource (lib "eagle-import") (part "PINHD-1X1"))
    )
    (comp (ref "JP121")
      (value "1")
      (footprint "eagle-import:1X01")
      (libsource (lib "eagle-import") (part "PINHD-1X1"))
    )
    (comp (ref "JP122")
      (value "1")
      (footprint "eagle-import:1X01")
      (libsource (lib "eagle-import") (part "PINHD-1X1"))
    )
    (comp (ref "JP123")
      (value "1")
      (footprint "eagle-import:1X01")
      (libsource (lib "eagle-import") (part "PINHD-1X1"))
    )
    (comp (ref "JP124")
      (value "1")
      (footprint "eagle-import:1X01")
      (libsource (lib "eagle-import") (part "PINHD-1X1"))
    )
    (comp (ref "JP125")
      (value "1")
      (footprint "eagle-import:1X01")
      (libsource (lib "eagle-import") (part "PINHD-1X1"))
    )
    (comp (ref "JP126")
      (value "1")
      (footprint "eagle-import:1X01")
      (libsource (lib "eagle-import") (part "PINHD-1X1"))
    )
    (comp (ref "JP127")
      (value "1")
      (footprint "eagle-import:1X01")
      (libsource (lib "eagle-import") (part "PINHD-1X1"))
    )
    (comp (ref "JP128")
      (value "1")
      (footprint "eagle-import:1X01")
      (libsource (lib "eagle-import") (part "PINHD-1X1"))
    )
    (comp (ref "JP129")
      (value "1")
      (footprint "eagle-import:1X01")
      (libsource (lib "eagle-import") (part "PINHD-1X1"))
    )
    (comp (ref "JP130")
      (value "1")
      (footprint "eagle-import:1X01")
      (libsource (lib "eagle-import") (part "PINHD-1X1"))
    )
    (comp (ref "JP131")
      (value "1")
      (footprint "eagle-import:1X01")
      (libsource (lib "eagle-import") (part "PINHD-1X1"))
    )
    (comp (ref "JP132")
      (value "1")
      (footprint "eagle-import:1X01")
      (libsource (lib "eagle-import") (part "PINHD-1X1"))
    )
    (comp (ref "JP133")
      (value "1")
      (footprint "eagle-import:1X01")
      (libsource (lib "eagle-import") (part "PINHD-1X1"))
    )
    (comp (ref "JP134")
      (value "1")
      (footprint "eagle-import:1X01")
      (libsource (lib "eagle-import") (part "PINHD-1X1"))
    )
    (comp (ref "JP135")
      (value "1")
      (footprint "eagle-import:1X01")
      (libsource (lib "eagle-import") (part "PINHD-1X1"))
    )
    (comp (ref "JP136")
      (value "1")
      (footprint "eagle-import:1X01")
      (libsource (lib "eagle-import") (part "PINHD-1X1"))
    )
    (comp (ref "JP137")
      (value "1")
      (footprint "eagle-import:1X01")
      (libsource (lib "eagle-import") (part "PINHD-1X1"))
    )
    (comp (ref "JP138")
      (value "1")
      (footprint "eagle-import:1X01")
      (libsource (lib "eagle-import") (part "PINHD-1X1"))
    )
    (comp (ref "JP139")
      (value "1")
      (footprint "eagle-import:1X01")
      (libsource (lib "eagle-import") (part "PINHD-1X1"))
    )
    (comp (ref "JP140")
      (value "1")
      (footprint "eagle-import:1X01")
      (libsource (lib "eagle-import") (part "PINHD-1X1"))
    )
    (comp (ref "JP141")
      (value "1")
      (footprint "eagle-import:1X01")
      (libsource (lib "eagle-import") (part "PINHD-1X1"))
    )
    (comp (ref "JP142")
      (value "1")
      (footprint "eagle-import:1X01")
      (libsource (lib "eagle-import") (part "PINHD-1X1"))
    )
    (comp (ref "JP143")
      (value "1")
      (footprint "eagle-import:1X01")
      (libsource (lib "eagle-import") (part "PINHD-1X1"))
    )
    (comp (ref "JP144")
      (value "1")
      (footprint "eagle-import:1X01")
      (libsource (lib "eagle-import") (part "PINHD-1X1"))
    )
    (comp (ref "JP145")
      (value "1")
      (footprint "eagle-import:1X01")
      (libsource (lib "eagle-import") (part "PINHD-1X1"))
    )
    (comp (ref "JP146")
      (value "1")
      (footprint "eagle-import:1X01")
      (libsource (lib "eagle-import") (part "PINHD-1X1"))
    )
    (comp (ref "JP147")
      (value "1")
      (footprint "eagle-import:1X01")
      (libsource (lib "eagle-import") (part "PINHD-1X1"))
    )
    (comp (ref "JP148")
      (value "1")
      (footprint "eagle-import:1X01")
      (libsource (lib "eagle-import") (part "PINHD-1X1"))
    )
    (comp (ref "JP149")
      (value "1")
      (footprint "eagle-import:1X01")
      (libsource (lib "eagle-import") (part "PINHD-1X1"))
    )
    (comp (ref "JP150")
      (value "1")
      (footprint "eagle-import:1X01")
      (libsource (lib "eagle-import") (part "PINHD-1X1"))
    )
    (comp (ref "JP151")
      (value "1")
      (footprint "eagle-import:1X01")
      (libsource (lib "eagle-import") (part "PINHD-1X1"))
    )
    (comp (ref "JP152")
      (value "1")
      (footprint "eagle-import:1X01")
      (libsource (lib "eagle-import") (part "PINHD-1X1"))
    )
    (comp (ref "JP153")
      (value "1")
      (footprint "eagle-import:1X01")
      (libsource (lib "eagle-import") (part "PINHD-1X1"))
    )
    (comp (ref "JP154")
      (value "1")
      (footprint "eagle-import:1X01")
      (libsource (lib "eagle-import") (part "PINHD-1X1"))
    )
    (comp (ref "JP155")
      (value "1")
      (footprint "eagle-import:1X01")
      (libsource (lib "eagle-import") (part "PINHD-1X1"))
    )
    (comp (ref "JP156")
      (value "1")
      (footprint "eagle-import:1X01")
      (libsource (lib "eagle-import") (part "PINHD-1X1"))
    )
    (comp (ref "JP157")
      (value "1")
      (footprint "eagle-import:1X01")
      (libsource (lib "eagle-import") (part "PINHD-1X1"))
    )
    (comp (ref "JP158")
      (value "1")
      (footprint "eagle-import:1X01")
      (libsource (lib "eagle-import") (part "PINHD-1X1"))
    )
    (comp (ref "JP159")
      (value "1")
      (footprint "eagle-import:1X01")
      (libsource (lib "eagle-import") (part "PINHD-1X1"))
    )
    (comp (ref "JP160")
      (value "1")
      (footprint "eagle-import:1X01")
      (libsource (lib "eagle-import") (part "PINHD-1X1"))
    )
    (comp (ref "JP161")
      (value "1")
      (footprint "eagle-import:1X01")
      (libsource (lib "eagle-import") (part "PINHD-1X1"))
    )
    (comp (ref "JP162")
      (value "1")
      (footprint "eagle-import:1X01")
      (libsource (lib "eagle-import") (part "PINHD-1X1"))
    )
    (comp (ref "JP163")
      (value "1")
      (footprint "eagle-import:1X01")
      (libsource (lib "eagle-import") (part "PINHD-1X1"))
    )
    (comp (ref "JP164")
      (value "1")
      (footprint "eagle-import:1X01")
      (libsource (lib "eagle-import") (part "PINHD-1X1"))
    )
    (comp (ref "JP165")
      (value "1")
      (footprint "eagle-import:1X01")
      (libsource (lib "eagle-import") (part "PINHD-1X1"))
    )
    (comp (ref "JP166")
      (value "1")
      (footprint "eagle-import:1X01")
      (libsource (lib "eagle-import") (part "PINHD-1X1"))
    )
    (comp (ref "JP167")
      (value "1")
      (footprint "eagle-import:1X01")
      (libsource (lib "eagle-import") (part "PINHD-1X1"))
    )
    (comp (ref "JP168")
      (value "1")
      (footprint "eagle-import:1X01")
      (libsource (lib "eagle-import") (part "PINHD-1X1"))
    )
    (comp (ref "JP169")
      (value "1")
      (footprint "eagle-import:1X01")
      (libsource (lib "eagle-import") (part "PINHD-1X1"))
    )
    (comp (ref "JP170")
      (value "1")
      (footprint "eagle-import:1X01")
      (libsource (lib "eagle-import") (part "PINHD-1X1"))
    )
    (comp (ref "JP171")
      (value "1")
      (footprint "eagle-import:1X01")
      (libsource (lib "eagle-import") (part "PINHD-1X1"))
    )
    (comp (ref "JP172")
      (value "1")
      (footprint "eagle-import:1X01")
      (libsource (lib "eagle-import") (part "PINHD-1X1"))
    )
    (comp (ref "JP173")
      (value "1")
      (footprint "eagle-import:1X01")
      (libsource (lib "eagle-import") (part "PINHD-1X1"))
    )
    (comp (ref "JP174")
      (value "1")
      (footprint "eagle-import:1X01")
      (libsource (lib "eagle-import") (part "PINHD-1X1"))
    )
    (comp (ref "JP175")
      (value "1")
      (footprint "eagle-import:1X01")
      (libsource (lib "eagle-import") (part "PINHD-1X1"))
    )
    (comp (ref "JP176")
      (value "1")
      (footprint "eagle-import:1X01")
      (libsource (lib "eagle-import") (part "PINHD-1X1"))
    )
    (comp (ref "JP177")
      (value "1")
      (footprint "eagle-import:1X01")
      (libsource (lib "eagle-import") (part "PINHD-1X1"))
    )
    (comp (ref "JP178")
      (value "1")
      (footprint "eagle-import:1X01")
      (libsource (lib "eagle-import") (part "PINHD-1X1"))
    )
    (comp (ref "JP179")
      (value "1")
      (footprint "eagle-import:1X01")
      (libsource (lib "eagle-import") (part "PINHD-1X1"))
    )
    (comp (ref "JP180")
      (value "1")
      (footprint "eagle-import:1X01")
      (libsource (lib "eagle-import") (part "PINHD-1X1"))
    )
    (comp (ref "JP181")
      (value "1")
      (footprint "eagle-import:1X01")
      (libsource (lib "eagle-import") (part "PINHD-1X1"))
    )
    (comp (ref "JP182")
      (value "1")
      (footprint "eagle-import:1X01")
      (libsource (lib "eagle-import") (part "PINHD-1X1"))
    )
    (comp (ref "JP183")
      (value "1")
      (footprint "eagle-import:1X01")
      (libsource (lib "eagle-import") (part "PINHD-1X1"))
    )
    (comp (ref "JP184")
      (value "1")
      (footprint "eagle-import:1X01")
      (libsource (lib "eagle-import") (part "PINHD-1X1"))
    )
    (comp (ref "JP185")
      (value "1")
      (footprint "eagle-import:1X01")
      (libsource (lib "eagle-import") (part "PINHD-1X1"))
    )
    (comp (ref "JP186")
      (value "1")
      (footprint "eagle-import:1X01")
      (libsource (lib "eagle-import") (part "PINHD-1X1"))
    )
    (comp (ref "JP187")
      (value "1")
      (footprint "eagle-import:1X01")
      (libsource (lib "eagle-import") (part "PINHD-1X1"))
    )
    (comp (ref "JP188")
      (value "1")
      (footprint "eagle-import:1X01")
      (libsource (lib "eagle-import") (part "PINHD-1X1"))
    )
    (comp (ref "JP189")
      (value "1")
      (footprint "eagle-import:1X01")
      (libsource (lib "eagle-import") (part "PINHD-1X1"))
    )
    (comp (ref "JP190")
      (value "1")
      (footprint "eagle-import:1X01")
      (libsource (lib "eagle-import") (part "PINHD-1X1"))
    )
    (comp (ref "JP191")
      (value "1")
      (footprint "eagle-import:1X01")
      (libsource (lib "eagle-import") (part "PINHD-1X1"))
    )
    (comp (ref "JP192")
      (value "1")
      (footprint "eagle-import:1X01")
      (libsource (lib "eagle-import") (part "PINHD-1X1"))
    )
    (comp (ref "JP193")
      (value "1")
      (footprint "eagle-import:1X01")
      (libsource (lib "eagle-import") (part "PINHD-1X1"))
    )
    (comp (ref "JP194")
      (value "1")
      (footprint "eagle-import:1X01")
      (libsource (lib "eagle-import") (part "PINHD-1X1"))
    )
    (comp (ref "JP195")
      (value "1")
      (footprint "eagle-import:1X01")
      (libsource (lib "eagle-import") (part "PINHD-1X1"))
    )
    (comp (ref "JP196")
      (value "1")
      (footprint "eagle-import:1X01")
      (libsource (lib "eagle-import") (part "PINHD-1X1"))
    )
    (comp (ref "JP197")
      (value "1")
      (footprint "eagle-import:1X01")
      (libsource (lib "eagle-import") (part "PINHD-1X1"))
    )
    (comp (ref "JP198")
      (value "1")
      (footprint "eagle-import:1X01")
      (libsource (lib "eagle-import") (part "PINHD-1X1"))
    )
    (comp (ref "JP199")
      (value "1")
      (footprint "eagle-import:1X01")
      (libsource (lib "eagle-import") (part "PINHD-1X1"))
    )
    (comp (ref "JP200")
      (value "1")
      (footprint "eagle-import:1X01")
      (libsource (lib "eagle-import") (part "PINHD-1X1"))
    )
    (comp (ref "JP201")
      (value "1")
      (footprint "eagle-import:1X01")
      (libsource (lib "eagle-import") (part "PINHD-1X1"))
    )
    (comp (ref "JP202")
      (value "1")
      (footprint "eagle-import:1X01")
      (libsource (lib "eagle-import") (part "PINHD-1X1"))
    )
    (comp (ref "JP203")
      (value "1")
      (footprint "eagle-import:1X01")
      (libsource (lib "eagle-import") (part "PINHD-1X1"))
    )
    (comp (ref "JP204")
      (value "1")
      (footprint "eagle-import:1X01")
      (libsource (lib "eagle-import") (part "PINHD-1X1"))
    )
    (comp (ref "JP205")
      (value "1")
      (footprint "eagle-import:1X01")
      (libsource (lib "eagle-import") (part "PINHD-1X1"))
    )
    (comp (ref "JP206")
      (value "1")
      (footprint "eagle-import:1X01")
      (libsource (lib "eagle-import") (part "PINHD-1X1"))
    )
    (comp (ref "JP207")
      (value "1")
      (footprint "eagle-import:1X01")
      (libsource (lib "eagle-import") (part "PINHD-1X1"))
    )
    (comp (ref "JP208")
      (value "1")
      (footprint "eagle-import:1X01")
      (libsource (lib "eagle-import") (part "PINHD-1X1"))
    )
    (comp (ref "JP209")
      (value "1")
      (footprint "eagle-import:1X01")
      (libsource (lib "eagle-import") (part "PINHD-1X1"))
    )
    (comp (ref "JP210")
      (value "1")
      (footprint "eagle-import:1X01")
      (libsource (lib "eagle-import") (part "PINHD-1X1"))
    )
    (comp (ref "JP211")
      (value "1")
      (footprint "eagle-import:1X01")
      (libsource (lib "eagle-import") (part "PINHD-1X1"))
    )
    (comp (ref "JP212")
      (value "1")
      (footprint "eagle-import:1X01")
      (libsource (lib "eagle-import") (part "PINHD-1X1"))
    )
    (comp (ref "JP213")
      (value "1")
      (footprint "eagle-import:1X01")
      (libsource (lib "eagle-import") (part "PINHD-1X1"))
    )
    (comp (ref "JP214")
      (value "1")
      (footprint "eagle-import:1X01")
      (libsource (lib "eagle-import") (part "PINHD-1X1"))
    )
    (comp (ref "JP215")
      (value "1")
      (footprint "eagle-import:1X01")
      (libsource (lib "eagle-import") (part "PINHD-1X1"))
    )
    (comp (ref "JP216")
      (value "1")
      (footprint "eagle-import:1X01")
      (libsource (lib "eagle-import") (part "PINHD-1X1"))
    )
    (comp (ref "JP217")
      (value "1")
      (footprint "eagle-import:1X01")
      (libsource (lib "eagle-import") (part "PINHD-1X1"))
    )
    (comp (ref "JP218")
      (value "1")
      (footprint "eagle-import:1X01")
      (libsource (lib "eagle-import") (part "PINHD-1X1"))
    )
    (comp (ref "JP219")
      (value "1")
      (footprint "eagle-import:1X01")
      (libsource (lib "eagle-import") (part "PINHD-1X1"))
    )
    (comp (ref "JP220")
      (value "1")
      (footprint "eagle-import:1X01")
      (libsource (lib "eagle-import") (part "PINHD-1X1"))
    )
    (comp (ref "JP221")
      (value "1")
      (footprint "eagle-import:1X01")
      (libsource (lib "eagle-import") (part "PINHD-1X1"))
    )
    (comp (ref "JP222")
      (value "1")
      (footprint "eagle-import:1X01")
      (libsource (lib "eagle-import") (part "PINHD-1X1"))
    )
    (comp (ref "JP223")
      (value "1")
      (footprint "eagle-import:1X01")
      (libsource (lib "eagle-import") (part "PINHD-1X1"))
    )
    (comp (ref "JP224")
      (value "1")
      (footprint "eagle-import:1X01")
      (libsource (lib "eagle-import") (part "PINHD-1X1"))
    )
    (comp (ref "JP225")
      (value "1")
      (footprint "eagle-import:1X01")
      (libsource (lib "eagle-import") (part "PINHD-1X1"))
    )
    (comp (ref "JP226")
      (value "1")
      (footprint "eagle-import:1X01")
      (libsource (lib "eagle-import") (part "PINHD-1X1"))
    )
    (comp (ref "JP227")
      (value "1")
      (footprint "eagle-import:1X01")
      (libsource (lib "eagle-import") (part "PINHD-1X1"))
    )
    (comp (ref "JP228")
      (value "1")
      (footprint "eagle-import:1X01")
      (libsource (lib "eagle-import") (part "PINHD-1X1"))
    )
    (comp (ref "JP229")
      (value "1")
      (footprint "eagle-import:1X01")
      (libsource (lib "eagle-import") (part "PINHD-1X1"))
    )
    (comp (ref "JP230")
      (value "1")
      (footprint "eagle-import:1X01")
      (libsource (lib "eagle-import") (part "PINHD-1X1"))
    )
    (comp (ref "JP231")
      (value "1")
      (footprint "eagle-import:1X01")
      (libsource (lib "eagle-import") (part "PINHD-1X1"))
    )
    (comp (ref "JP232")
      (value "1")
      (footprint "eagle-import:1X01")
      (libsource (lib "eagle-import") (part "PINHD-1X1"))
    )
    (comp (ref "JP233")
      (value "1")
      (footprint "eagle-import:1X01")
      (libsource (lib "eagle-import") (part "PINHD-1X1"))
    )
    (comp (ref "JP234")
      (value "1")
      (footprint "eagle-import:1X01")
      (libsource (lib "eagle-import") (part "PINHD-1X1"))
    )
    (comp (ref "JP235")
      (value "1")
      (footprint "eagle-import:1X01")
      (libsource (lib "eagle-import") (part "PINHD-1X1"))
    )
    (comp (ref "JP236")
      (value "1")
      (footprint "eagle-import:1X01")
      (libsource (lib "eagle-import") (part "PINHD-1X1"))
    )
    (comp (ref "JP237")
      (value "1")
      (footprint "eagle-import:1X01")
      (libsource (lib "eagle-import") (part "PINHD-1X1"))
    )
    (comp (ref "JP238")
      (value "1")
      (footprint "eagle-import:1X01")
      (libsource (lib "eagle-import") (part "PINHD-1X1"))
    )
    (comp (ref "JP239")
      (value "1")
      (footprint "eagle-import:1X01")
      (libsource (lib "eagle-import") (part "PINHD-1X1"))
    )
    (comp (ref "JP240")
      (value "1")
      (footprint "eagle-import:1X01")
      (libsource (lib "eagle-import") (part "PINHD-1X1"))
    )
    (comp (ref "JP241")
      (value "1")
      (footprint "eagle-import:1X01")
      (libsource (lib "eagle-import") (part "PINHD-1X1"))
    )
    (comp (ref "JP242")
      (value "1")
      (footprint "eagle-import:1X01")
      (libsource (lib "eagle-import") (part "PINHD-1X1"))
    )
    (comp (ref "JP243")
      (value "1")
      (footprint "eagle-import:1X01")
      (libsource (lib "eagle-import") (part "PINHD-1X1"))
    )
    (comp (ref "JP244")
      (value "1")
      (footprint "eagle-import:1X01")
      (libsource (lib "eagle-import") (part "PINHD-1X1"))
    )
    (comp (ref "JP245")
      (value "1")
      (footprint "eagle-import:1X01")
      (libsource (lib "eagle-import") (part "PINHD-1X1"))
    )
    (comp (ref "JP246")
      (value "1")
      (footprint "eagle-import:1X01")
      (libsource (lib "eagle-import") (part "PINHD-1X1"))
    )
    (comp (ref "JP247")
      (value "1")
      (footprint "eagle-import:1X01")
      (libsource (lib "eagle-import") (part "PINHD-1X1"))
    )
    (comp (ref "JP248")
      (value "1")
      (footprint "eagle-import:1X01")
      (libsource (lib "eagle-import") (part "PINHD-1X1"))
    )
    (comp (ref "JP249")
      (value "1")
      (footprint "eagle-import:1X01")
      (libsource (lib "eagle-import") (part "PINHD-1X1"))
    )
    (comp (ref "JP250")
      (value "1")
      (footprint "eagle-import:1X01")
      (libsource (lib "eagle-import") (part "PINHD-1X1"))
    )
    (comp (ref "JP251")
      (value "1")
      (footprint "eagle-import:1X01")
      (libsource (lib "eagle-import") (part "PINHD-1X1"))
    )
    (comp (ref "JP252")
      (value "1")
      (footprint "eagle-import:1X01")
      (libsource (lib "eagle-import") (part "PINHD-1X1"))
    )
    (comp (ref "JP253")
      (value "1")
      (footprint "eagle-import:1X01")
      (libsource (lib "eagle-import") (part "PINHD-1X1"))
    )
    (comp (ref "JP254")
      (value "1")
      (footprint "eagle-import:1X01")
      (libsource (lib "eagle-import") (part "PINHD-1X1"))
    )
    (comp (ref "JP255")
      (value "1")
      (footprint "eagle-import:1X01")
      (libsource (lib "eagle-import") (part "PINHD-1X1"))
    )
    (comp (ref "JP256")
      (value "1")
      (footprint "eagle-import:1X01")
      (libsource (lib "eagle-import") (part "PINHD-1X1"))
    )
    (comp (ref "JP257")
      (value "1")
      (footprint "eagle-import:1X01")
      (libsource (lib "eagle-import") (part "PINHD-1X1"))
    )
    (comp (ref "JP258")
      (value "1")
      (footprint "eagle-import:1X01")
      (libsource (lib "eagle-import") (part "PINHD-1X1"))
    )
    (comp (ref "JP259")
      (value "1")
      (footprint "eagle-import:1X01")
      (libsource (lib "eagle-import") (part "PINHD-1X1"))
    )
    (comp (ref "JP260")
      (value "1")
      (footprint "eagle-import:1X01")
      (libsource (lib "eagle-import") (part "PINHD-1X1"))
    )
    (comp (ref "JP261")
      (value "1")
      (footprint "eagle-import:1X01")
      (libsource (lib "eagle-import") (part "PINHD-1X1"))
    )
    (comp (ref "JP262")
      (value "1")
      (footprint "eagle-import:1X01")
      (libsource (lib "eagle-import") (part "PINHD-1X1"))
    )
    (comp (ref "JP263")
      (value "1")
      (footprint "eagle-import:1X01")
      (libsource (lib "eagle-import") (part "PINHD-1X1"))
    )
    (comp (ref "JP264")
      (value "1")
      (footprint "eagle-import:1X01")
      (libsource (lib "eagle-import") (part "PINHD-1X1"))
    )
    (comp (ref "JP265")
      (value "1")
      (footprint "eagle-import:1X01")
      (libsource (lib "eagle-import") (part "PINHD-1X1"))
    )
    (comp (ref "JP266")
      (value "1")
      (footprint "eagle-import:1X01")
      (libsource (lib "eagle-import") (part "PINHD-1X1"))
    )
    (comp (ref "JP267")
      (value "1")
      (footprint "eagle-import:1X01")
      (libsource (lib "eagle-import") (part "PINHD-1X1"))
    )
    (comp (ref "JP268")
      (value "1")
      (footprint "eagle-import:1X01")
      (libsource (lib "eagle-import") (part "PINHD-1X1"))
    )
    (comp (ref "JP269")
      (value "1")
      (footprint "eagle-import:1X01")
      (libsource (lib "eagle-import") (part "PINHD-1X1"))
    )
    (comp (ref "JP270")
      (value "1")
      (footprint "eagle-import:1X01")
      (libsource (lib "eagle-import") (part "PINHD-1X1"))
    )
    (comp (ref "JP271")
      (value "1")
      (footprint "eagle-import:1X01")
      (libsource (lib "eagle-import") (part "PINHD-1X1"))
    )
    (comp (ref "JP272")
      (value "1")
      (footprint "eagle-import:1X01")
      (libsource (lib "eagle-import") (part "PINHD-1X1"))
    )
    (comp (ref "JP273")
      (value "1")
      (footprint "eagle-import:1X01")
      (libsource (lib "eagle-import") (part "PINHD-1X1"))
    )
    (comp (ref "JP274")
      (value "1")
      (footprint "eagle-import:1X01")
      (libsource (lib "eagle-import") (part "PINHD-1X1"))
    )
    (comp (ref "JP275")
      (value "1")
      (footprint "eagle-import:1X01")
      (libsource (lib "eagle-import") (part "PINHD-1X1"))
    )
    (comp (ref "JP276")
      (value "1")
      (footprint "eagle-import:1X01")
      (libsource (lib "eagle-import") (part "PINHD-1X1"))
    )
    (comp (ref "JP277")
      (value "1")
      (footprint "eagle-import:1X01")
      (libsource (lib "eagle-import") (part "PINHD-1X1"))
    )
    (comp (ref "JP278")
      (value "1")
      (footprint "eagle-import:1X01")
      (libsource (lib "eagle-import") (part "PINHD-1X1"))
    )
    (comp (ref "JP279")
      (value "1")
      (footprint "eagle-import:1X01")
      (libsource (lib "eagle-import") (part "PINHD-1X1"))
    )
    (comp (ref "JP280")
      (value "1")
      (footprint "eagle-import:1X01")
      (libsource (lib "eagle-import") (part "PINHD-1X1"))
    )
    (comp (ref "JP281")
      (value "1")
      (footprint "eagle-import:1X01")
      (libsource (lib "eagle-import") (part "PINHD-1X1"))
    )
    (comp (ref "JP282")
      (value "1")
      (footprint "eagle-import:1X01")
      (libsource (lib "eagle-import") (part "PINHD-1X1"))
    )
    (comp (ref "JP283")
      (value "1")
      (footprint "eagle-import:1X01")
      (libsource (lib "eagle-import") (part "PINHD-1X1"))
    )
    (comp (ref "JP284")
      (value "1")
      (footprint "eagle-import:1X01")
      (libsource (lib "eagle-import") (part "PINHD-1X1"))
    )
    (comp (ref "JP285")
      (value "1")
      (footprint "eagle-import:1X01")
      (libsource (lib "eagle-import") (part "PINHD-1X1"))
    )
    (comp (ref "JP286")
      (value "1")
      (footprint "eagle-import:1X01")
      (libsource (lib "eagle-import") (part "PINHD-1X1"))
    )
    (comp (ref "JP287")
      (value "1")
      (footprint "eagle-import:1X01")
      (libsource (lib "eagle-import") (part "PINHD-1X1"))
    )
    (comp (ref "JP288")
      (value "1")
      (footprint "eagle-import:1X01")
      (libsource (lib "eagle-import") (part "PINHD-1X1"))
    )
    (comp (ref "JP289")
      (value "1")
      (footprint "eagle-import:1X01")
      (libsource (lib "eagle-import") (part "PINHD-1X1"))
    )
    (comp (ref "JP290")
      (value "1")
      (footprint "eagle-import:1X01")
      (libsource (lib "eagle-import") (part "PINHD-1X1"))
    )
    (comp (ref "JP291")
      (value "1")
      (footprint "eagle-import:1X01")
      (libsource (lib "eagle-import") (part "PINHD-1X1"))
    )
    (comp (ref "JP292")
      (value "1")
      (footprint "eagle-import:1X01")
      (libsource (lib "eagle-import") (part "PINHD-1X1"))
    )
    (comp (ref "JP293")
      (value "1")
      (footprint "eagle-import:1X01")
      (libsource (lib "eagle-import") (part "PINHD-1X1"))
    )
    (comp (ref "JP294")
      (value "1")
      (footprint "eagle-import:1X01")
      (libsource (lib "eagle-import") (part "PINHD-1X1"))
    )
    (comp (ref "JP295")
      (value "1")
      (footprint "eagle-import:1X01")
      (libsource (lib "eagle-import") (part "PINHD-1X1"))
    )
    (comp (ref "JP296")
      (value "1")
      (footprint "eagle-import:1X01")
      (libsource (lib "eagle-import") (part "PINHD-1X1"))
    )
    (comp (ref "JP297")
      (value "1")
      (footprint "eagle-import:1X01")
      (libsource (lib "eagle-import") (part "PINHD-1X1"))
    )
    (comp (ref "JP298")
      (value "1")
      (footprint "eagle-import:1X01")
      (libsource (lib "eagle-import") (part "PINHD-1X1"))
    )
    (comp (ref "JP299")
      (value "1")
      (footprint "eagle-import:1X01")
      (libsource (lib "eagle-import") (part "PINHD-1X1"))
    )
    (comp (ref "JP300")
      (value "1")
      (footprint "eagle-import:1X01")
      (libsource (lib "eagle-import") (part "PINHD-1X1"))
    )
    (comp (ref "JP301")
      (value "1")
      (footprint "eagle-import:1X01")
      (libsource (lib "eagle-import") (part "PINHD-1X1"))
    )
    (comp (ref "JP302")
      (value "1")
      (footprint "eagle-import:1X01")
      (libsource (lib "eagle-import") (part "PINHD-1X1"))
    )
    (comp (ref "JP303")
      (value "1")
      (footprint "eagle-import:1X01")
      (libsource (lib "eagle-import") (part "PINHD-1X1"))
    )
    (comp (ref "JP304")
      (value "1")
      (footprint "eagle-import:1X01")
      (libsource (lib "eagle-import") (part "PINHD-1X1"))
    )
    (comp (ref "JP305")
      (value "1")
      (footprint "eagle-import:1X01")
      (libsource (lib "eagle-import") (part "PINHD-1X1"))
    )
    (comp (ref "JP306")
      (value "1")
      (footprint "eagle-import:1X01")
      (libsource (lib "eagle-import") (part "PINHD-1X1"))
    )
    (comp (ref "JP307")
      (value "1")
      (footprint "eagle-import:1X01")
      (libsource (lib "eagle-import") (part "PINHD-1X1"))
    )
    (comp (ref "JP308")
      (value "1")
      (footprint "eagle-import:1X01")
      (libsource (lib "eagle-import") (part "PINHD-1X1"))
    )
    (comp (ref "JP309")
      (value "1")
      (footprint "eagle-import:1X01")
      (libsource (lib "eagle-import") (part "PINHD-1X1"))
    )
    (comp (ref "JP310")
      (value "1")
      (footprint "eagle-import:1X01")
      (libsource (lib "eagle-import") (part "PINHD-1X1"))
    )
    (comp (ref "JP311")
      (value "1")
      (footprint "eagle-import:1X01")
      (libsource (lib "eagle-import") (part "PINHD-1X1"))
    )
    (comp (ref "JP312")
      (value "1")
      (footprint "eagle-import:1X01")
      (libsource (lib "eagle-import") (part "PINHD-1X1"))
    )
    (comp (ref "JP313")
      (value "1")
      (footprint "eagle-import:1X01")
      (libsource (lib "eagle-import") (part "PINHD-1X1"))
    )
    (comp (ref "JP314")
      (value "1")
      (footprint "eagle-import:1X01")
      (libsource (lib "eagle-import") (part "PINHD-1X1"))
    )
    (comp (ref "JP315")
      (value "1")
      (footprint "eagle-import:1X01")
      (libsource (lib "eagle-import") (part "PINHD-1X1"))
    )
    (comp (ref "JP316")
      (value "1")
      (footprint "eagle-import:1X01")
      (libsource (lib "eagle-import") (part "PINHD-1X1"))
    )
    (comp (ref "JP317")
      (value "1")
      (footprint "eagle-import:1X01")
      (libsource (lib "eagle-import") (part "PINHD-1X1"))
    )
    (comp (ref "JP318")
      (value "1")
      (footprint "eagle-import:1X01")
      (libsource (lib "eagle-import") (part "PINHD-1X1"))
    )
    (comp (ref "JP319")
      (value "1")
      (footprint "eagle-import:1X01")
      (libsource (lib "eagle-import") (part "PINHD-1X1"))
    )
    (comp (ref "JP320")
      (value "1")
      (footprint "eagle-import:1X01")
      (libsource (lib "eagle-import") (part "PINHD-1X1"))
    )
    (comp (ref "JP321")
      (value "1")
      (footprint "eagle-import:1X01")
      (libsource (lib "eagle-import") (part "PINHD-1X1"))
    )
    (comp (ref "JP322")
      (value "1")
      (footprint "eagle-import:1X01")
      (libsource (lib "eagle-import") (part "PINHD-1X1"))
    )
    (comp (ref "JP323")
      (value "1")
      (footprint "eagle-import:1X01")
      (libsource (lib "eagle-import") (part "PINHD-1X1"))
    )
    (comp (ref "JP324")
      (value "1")
      (footprint "eagle-import:1X01")
      (libsource (lib "eagle-import") (part "PINHD-1X1"))
    )
    (comp (ref "JP325")
      (value "1")
      (footprint "eagle-import:1X01")
      (libsource (lib "eagle-import") (part "PINHD-1X1"))
    )
    (comp (ref "JP326")
      (value "1")
      (footprint "eagle-import:1X01")
      (libsource (lib "eagle-import") (part "PINHD-1X1"))
    )
    (comp (ref "JP327")
      (value "1")
      (footprint "eagle-import:1X01")
      (libsource (lib "eagle-import") (part "PINHD-1X1"))
    )
    (comp (ref "JP328")
      (value "1")
      (footprint "eagle-import:1X01")
      (libsource (lib "eagle-import") (part "PINHD-1X1"))
    )
    (comp (ref "JP329")
      (value "1")
      (footprint "eagle-import:1X01")
      (libsource (lib "eagle-import") (part "PINHD-1X1"))
    )
    (comp (ref "JP330")
      (value "1")
      (footprint "eagle-import:1X01")
      (libsource (lib "eagle-import") (part "PINHD-1X1"))
    )
    (comp (ref "JP331")
      (value "1")
      (footprint "eagle-import:1X01")
      (libsource (lib "eagle-import") (part "PINHD-1X1"))
    )
    (comp (ref "JP332")
      (value "1")
      (footprint "eagle-import:1X01")
      (libsource (lib "eagle-import") (part "PINHD-1X1"))
    )
    (comp (ref "JP333")
      (value "1")
      (footprint "eagle-import:1X01")
      (libsource (lib "eagle-import") (part "PINHD-1X1"))
    )
    (comp (ref "JP334")
      (value "1")
      (footprint "eagle-import:1X01")
      (libsource (lib "eagle-import") (part "PINHD-1X1"))
    )
    (comp (ref "JP335")
      (value "1")
      (footprint "eagle-import:1X01")
      (libsource (lib "eagle-import") (part "PINHD-1X1"))
    )
    (comp (ref "JP336")
      (value "1")
      (footprint "eagle-import:1X01")
      (libsource (lib "eagle-import") (part "PINHD-1X1"))
    )
    (comp (ref "JP337")
      (value "1")
      (footprint "eagle-import:1X01")
      (libsource (lib "eagle-import") (part "PINHD-1X1"))
    )
    (comp (ref "JP338")
      (value "1")
      (footprint "eagle-import:1X01")
      (libsource (lib "eagle-import") (part "PINHD-1X1"))
    )
    (comp (ref "JP339")
      (value "1")
      (footprint "eagle-import:1X01")
      (libsource (lib "eagle-import") (part "PINHD-1X1"))
    )
    (comp (ref "JP340")
      (value "1")
      (footprint "eagle-import:1X01")
      (libsource (lib "eagle-import") (part "PINHD-1X1"))
    )
    (comp (ref "JP341")
      (value "1")
      (footprint "eagle-import:1X01")
      (libsource (lib "eagle-import") (part "PINHD-1X1"))
    )
    (comp (ref "JP342")
      (value "1")
      (footprint "eagle-import:1X01")
      (libsource (lib "eagle-import") (part "PINHD-1X1"))
    )
  )
  (nets
    (net (code "1") (name "1V2") (class "Default")
      (node (ref "C4") (pin "2") (pinfunction "2_2") (pintype "passive"))
      (node (ref "C5") (pin "2") (pinfunction "2_2") (pintype "passive"))
      (node (ref "JP3") (pin "7") (pinfunction "7_7") (pintype "passive"))
      (node (ref "R18") (pin "P$1") (pinfunction "P$1_P$1") (pintype "bidirectional"))
      (node (ref "R19") (pin "P$1") (pinfunction "P$1_P$1") (pintype "bidirectional"))
      (node (ref "U3") (pin "P$1") (pinfunction "VOUT_P$1") (pintype "bidirectional"))
      (node (ref "U3") (pin "P$3") (pinfunction "VOUT_P$3") (pintype "bidirectional"))
    )
    (net (code "2") (name "2V5") (class "Default")
      (node (ref "C2") (pin "2") (pinfunction "2_2") (pintype "passive"))
      (node (ref "C3") (pin "2") (pinfunction "2_2") (pintype "passive"))
      (node (ref "JP3") (pin "5") (pinfunction "5_5") (pintype "passive"))
      (node (ref "R17") (pin "P$1") (pinfunction "P$1_P$1") (pintype "bidirectional"))
      (node (ref "R20") (pin "P$1") (pinfunction "P$1_P$1") (pintype "bidirectional"))
      (node (ref "R39") (pin "P$1") (pinfunction "P$1_P$1") (pintype "bidirectional"))
      (node (ref "U2") (pin "P$1") (pinfunction "VOUT_P$1") (pintype "bidirectional"))
      (node (ref "U2") (pin "P$3") (pinfunction "VOUT_P$3") (pintype "bidirectional"))
    )
    (net (code "3") (name "3V3") (class "Default")
      (node (ref "C1") (pin "2") (pinfunction "2_2") (pintype "passive"))
      (node (ref "C12") (pin "2") (pinfunction "2_2") (pintype "passive"))
      (node (ref "C13") (pin "2") (pinfunction "2_2") (pintype "passive"))
      (node (ref "C14") (pin "2") (pinfunction "2_2") (pintype "passive"))
      (node (ref "C8") (pin "2") (pinfunction "2_2") (pintype "passive"))
      (node (ref "C9") (pin "2") (pinfunction "2_2") (pintype "passive"))
      (node (ref "IC2") (pin "3") (pinfunction "DATA2_3") (pintype "bidirectional"))
      (node (ref "IC2") (pin "7") (pinfunction "DATA3_7") (pintype "bidirectional"))
      (node (ref "IC2") (pin "8") (pinfunction "VCC_8") (pintype "bidirectional"))
      (node (ref "J1") (pin "4") (pinfunction "4_4") (pintype "passive"))
      (node (ref "JP3") (pin "3") (pinfunction "3_3") (pintype "passive"))
      (node (ref "R1") (pin "P$2") (pinfunction "P$2_P$2") (pintype "bidirectional"))
      (node (ref "R10") (pin "P$2") (pinfunction "P$2_P$2") (pintype "bidirectional"))
      (node (ref "R11") (pin "P$2") (pinfunction "P$2_P$2") (pintype "bidirectional"))
      (node (ref "R2") (pin "P$2") (pinfunction "P$2_P$2") (pintype "bidirectional"))
      (node (ref "R3") (pin "P$2") (pinfunction "P$2_P$2") (pintype "bidirectional"))
      (node (ref "R38") (pin "P$1") (pinfunction "P$1_P$1") (pintype "bidirectional"))
      (node (ref "R5") (pin "P$2") (pinfunction "P$2_P$2") (pintype "bidirectional"))
      (node (ref "R7") (pin "P$2") (pinfunction "P$2_P$2") (pintype "bidirectional"))
      (node (ref "U1") (pin "P$1") (pinfunction "VOUT_P$1") (pintype "bidirectional"))
      (node (ref "U1") (pin "P$3") (pinfunction "VOUT_P$3") (pintype "bidirectional"))
      (node (ref "U3") (pin "P$4") (pinfunction "VIN_P$4") (pintype "bidirectional"))
      (node (ref "Y1") (pin "4") (pinfunction "VCC_4") (pintype "bidirectional"))
    )
    (net (code "4") (name "5V") (class "Default")
      (node (ref "C10") (pin "2") (pinfunction "2_2") (pintype "passive"))
      (node (ref "C11") (pin "2") (pinfunction "2_2") (pintype "passive"))
      (node (ref "C6") (pin "2") (pinfunction "2_2") (pintype "passive"))
      (node (ref "C7") (pin "2") (pinfunction "2_2") (pintype "passive"))
      (node (ref "JP3") (pin "1") (pinfunction "1_1") (pintype "passive"))
      (node (ref "U1") (pin "P$4") (pinfunction "VIN_P$4") (pintype "bidirectional"))
      (node (ref "U2") (pin "P$4") (pinfunction "VIN_P$4") (pintype "bidirectional"))
    )
    (net (code "5") (name "ASDO") (class "Default")
      (node (ref "IC1") (pin "D1") (pinfunction "IO_52_D1") (pintype "bidirectional"))
      (node (ref "IC2") (pin "5") (pinfunction "DATA0_5") (pintype "bidirectional"))
      (node (ref "JP39") (pin "1") (pinfunction "1_1") (pintype "passive"))
    )
    (net (code "6") (name "CLK1") (class "Default")
      (node (ref "IC1") (pin "G1") (pinfunction "CLK1_G1") (pintype "bidirectional"))
      (node (ref "JP16") (pin "1") (pinfunction "1_1") (pintype "passive"))
      (node (ref "Y1") (pin "3") (pinfunction "OUT_3") (pintype "bidirectional"))
    )
    (net (code "7") (name "CLK2") (class "Default")
      (node (ref "IC1") (pin "T2") (pinfunction "CLK2_T2") (pintype "bidirectional"))
      (node (ref "JP18") (pin "1") (pinfunction "1_1") (pintype "passive"))
    )
    (net (code "8") (name "CLK3") (class "Default")
      (node (ref "IC1") (pin "T1") (pinfunction "CLK3_T1") (pintype "bidirectional"))
      (node (ref "JP17") (pin "1") (pinfunction "1_1") (pintype "passive"))
    )
    (net (code "9") (name "CLK4") (class "Default")
      (node (ref "IC1") (pin "G21") (pinfunction "CLK4_G21") (pintype "bidirectional"))
      (node (ref "JP19") (pin "1") (pinfunction "1_1") (pintype "passive"))
    )
    (net (code "10") (name "CLK5") (class "Default")
      (node (ref "IC1") (pin "G22") (pinfunction "CLK5_G22") (pintype "bidirectional"))
      (node (ref "JP20") (pin "1") (pinfunction "1_1") (pintype "passive"))
    )
    (net (code "11") (name "CLK6") (class "Default")
      (node (ref "IC1") (pin "T21") (pinfunction "CLK6_T21") (pintype "bidirectional"))
      (node (ref "JP22") (pin "1") (pinfunction "1_1") (pintype "passive"))
    )
    (net (code "12") (name "CLK7") (class "Default")
      (node (ref "IC1") (pin "T22") (pinfunction "CLK7_T22") (pintype "bidirectional"))
      (node (ref "JP21") (pin "1") (pinfunction "1_1") (pintype "passive"))
    )
    (net (code "13") (name "CLK8") (class "Default")
      (node (ref "IC1") (pin "A12") (pinfunction "CLK8_A12") (pintype "bidirectional"))
      (node (ref "JP23") (pin "1") (pinfunction "1_1") (pintype "passive"))
    )
    (net (code "14") (name "CLK9") (class "Default")
      (node (ref "IC1") (pin "B12") (pinfunction "CLK9_B12") (pintype "bidirectional"))
      (node (ref "JP24") (pin "1") (pinfunction "1_1") (pintype "passive"))
    )
    (net (code "15") (name "CLK10") (class "Default")
      (node (ref "IC1") (pin "A11") (pinfunction "CLK10_A11") (pintype "bidirectional"))
      (node (ref "JP26") (pin "1") (pinfunction "1_1") (pintype "passive"))
    )
    (net (code "16") (name "CLK11") (class "Default")
      (node (ref "IC1") (pin "B11") (pinfunction "CLK11_B11") (pintype "bidirectional"))
      (node (ref "JP25") (pin "1") (pinfunction "1_1") (pintype "passive"))
    )
    (net (code "17") (name "CLK12") (class "Default")
      (node (ref "IC1") (pin "AB12") (pinfunction "CLK12_AB12") (pintype "bidirectional"))
      (node (ref "JP27") (pin "1") (pinfunction "1_1") (pintype "passive"))
    )
    (net (code "18") (name "CLK13") (class "Default")
      (node (ref "IC1") (pin "AA12") (pinfunction "CLK13_AA12") (pintype "bidirectional"))
      (node (ref "JP28") (pin "1") (pinfunction "1_1") (pintype "passive"))
    )
    (net (code "19") (name "CLK14") (class "Default")
      (node (ref "IC1") (pin "AB11") (pinfunction "CLK14_AB11") (pintype "bidirectional"))
      (node (ref "JP30") (pin "1") (pinfunction "1_1") (pintype "passive"))
    )
    (net (code "20") (name "CLK15") (class "Default")
      (node (ref "IC1") (pin "AA11") (pinfunction "CLK15_AA11") (pintype "bidirectional"))
      (node (ref "JP29") (pin "1") (pinfunction "1_1") (pintype "passive"))
    )
    (net (code "21") (name "CONF_DONE") (class "Default")
      (node (ref "IC1") (pin "M18") (pinfunction "CONF_DONE_M18") (pintype "bidirectional"))
      (node (ref "R3") (pin "P$1") (pinfunction "P$1_P$1") (pintype "bidirectional"))
    )
    (net (code "22") (name "DATA0") (class "Default")
      (node (ref "IC1") (pin "K1") (pinfunction "IO_140_K1") (pintype "bidirectional"))
      (node (ref "IC2") (pin "2") (pinfunction "DATA1_2") (pintype "bidirectional"))
      (node (ref "JP113") (pin "1") (pinfunction "1_1") (pintype "passive"))
    )
    (net (code "23") (name "DCLK") (class "Default")
      (node (ref "IC1") (pin "K2") (pinfunction "DCLK_K2") (pintype "bidirectional"))
      (node (ref "IC2") (pin "6") (pinfunction "DCLK_6") (pintype "bidirectional"))
    )
    (net (code "24") (name "GND") (class "Default")
      (node (ref "C1") (pin "1") (pinfunction "1_1") (pintype "passive"))
      (node (ref "C10") (pin "1") (pinfunction "1_1") (pintype "passive"))
      (node (ref "C11") (pin "1") (pinfunction "1_1") (pintype "passive"))
      (node (ref "C12") (pin "1") (pinfunction "1_1") (pintype "passive"))
      (node (ref "C13") (pin "1") (pinfunction "1_1") (pintype "passive"))
      (node (ref "C14") (pin "1") (pinfunction "1_1") (pintype "passive"))
      (node (ref "C15") (pin "1") (pinfunction "1_1") (pintype "passive"))
      (node (ref "C16") (pin "1") (pinfunction "1_1") (pintype "passive"))
      (node (ref "C17") (pin "1") (pinfunction "1_1") (pintype "passive"))
      (node (ref "C18") (pin "1") (pinfunction "1_1") (pintype "passive"))
      (node (ref "C19") (pin "1") (pinfunction "1_1") (pintype "passive"))
      (node (ref "C2") (pin "1") (pinfunction "1_1") (pintype "passive"))
      (node (ref "C20") (pin "1") (pinfunction "1_1") (pintype "passive"))
      (node (ref "C21") (pin "1") (pinfunction "1_1") (pintype "passive"))
      (node (ref "C22") (pin "1") (pinfunction "1_1") (pintype "passive"))
      (node (ref "C23") (pin "1") (pinfunction "1_1") (pintype "passive"))
      (node (ref "C24") (pin "1") (pinfunction "1_1") (pintype "passive"))
      (node (ref "C25") (pin "1") (pinfunction "1_1") (pintype "passive"))
      (node (ref "C26") (pin "1") (pinfunction "1_1") (pintype "passive"))
      (node (ref "C3") (pin "1") (pinfunction "1_1") (pintype "passive"))
      (node (ref "C4") (pin "1") (pinfunction "1_1") (pintype "passive"))
      (node (ref "C5") (pin "1") (pinfunction "1_1") (pintype "passive"))
      (node (ref "C6") (pin "1") (pinfunction "1_1") (pintype "passive"))
      (node (ref "C7") (pin "1") (pinfunction "1_1") (pintype "passive"))
      (node (ref "C8") (pin "1") (pinfunction "1_1") (pintype "passive"))
      (node (ref "C9") (pin "1") (pinfunction "1_1") (pintype "passive"))
      (node (ref "IC1") (pin "A1") (pinfunction "GND_1_A1") (pintype "bidirectional"))
      (node (ref "IC1") (pin "A22") (pinfunction "GND_2_A22") (pintype "bidirectional"))
      (node (ref "IC1") (pin "AA2") (pinfunction "GND_63_AA2") (pintype "bidirectional"))
      (node (ref "IC1") (pin "AA22") (pinfunction "GND_64_AA22") (pintype "bidirectional"))
      (node (ref "IC1") (pin "AB1") (pinfunction "GND_65_AB1") (pintype "bidirectional"))
      (node (ref "IC1") (pin "AB22") (pinfunction "GND_67_AB22") (pintype "bidirectional"))
      (node (ref "IC1") (pin "AB6") (pinfunction "GND_66_AB6") (pintype "bidirectional"))
      (node (ref "IC1") (pin "C11") (pinfunction "GND_5_C11") (pintype "bidirectional"))
      (node (ref "IC1") (pin "C12") (pinfunction "GND_6_C12") (pintype "bidirectional"))
      (node (ref "IC1") (pin "C14") (pinfunction "GND_7_C14") (pintype "bidirectional"))
      (node (ref "IC1") (pin "C16") (pinfunction "GND_8_C16") (pintype "bidirectional"))
      (node (ref "IC1") (pin "C18") (pinfunction "GND_9_C18") (pintype "bidirectional"))
      (node (ref "IC1") (pin "C5") (pinfunction "GND_3_C5") (pintype "bidirectional"))
      (node (ref "IC1") (pin "C9") (pinfunction "GND_4_C9") (pintype "bidirectional"))
      (node (ref "IC1") (pin "D3") (pinfunction "GND_10_D3") (pintype "bidirectional"))
      (node (ref "IC1") (pin "D8") (pinfunction "GND_11_D8") (pintype "bidirectional"))
      (node (ref "IC1") (pin "E18") (pinfunction "GNDA2_E18") (pintype "bidirectional"))
      (node (ref "IC1") (pin "E20") (pinfunction "GND_12_E20") (pintype "bidirectional"))
      (node (ref "IC1") (pin "F12") (pinfunction "GND_14_F12") (pintype "bidirectional"))
      (node (ref "IC1") (pin "F3") (pinfunction "GND_13_F3") (pintype "bidirectional"))
      (node (ref "IC1") (pin "F5") (pinfunction "GNDA3_F5") (pintype "bidirectional"))
      (node (ref "IC1") (pin "G2") (pinfunction "GND_15_G2") (pintype "bidirectional"))
      (node (ref "IC1") (pin "G20") (pinfunction "GND_16_G20") (pintype "bidirectional"))
      (node (ref "IC1") (pin "H12") (pinfunction "GND_18_H12") (pintype "bidirectional"))
      (node (ref "IC1") (pin "H13") (pinfunction "GND_19_H13") (pintype "bidirectional"))
      (node (ref "IC1") (pin "H3") (pinfunction "GND_17_H3") (pintype "bidirectional"))
      (node (ref "IC1") (pin "J15") (pinfunction "GND_21_J15") (pintype "bidirectional"))
      (node (ref "IC1") (pin "J19") (pinfunction "GND_22_J19") (pintype "bidirectional"))
      (node (ref "IC1") (pin "J9") (pinfunction "GND_20_J9") (pintype "bidirectional"))
      (node (ref "IC1") (pin "K10") (pinfunction "GND_24_K10") (pintype "bidirectional"))
      (node (ref "IC1") (pin "K11") (pinfunction "GND_25_K11") (pintype "bidirectional"))
      (node (ref "IC1") (pin "K12") (pinfunction "GND_26_K12") (pintype "bidirectional"))
      (node (ref "IC1") (pin "K13") (pinfunction "GND_27_K13") (pintype "bidirectional"))
      (node (ref "IC1") (pin "K16") (pinfunction "GND_28_K16") (pintype "bidirectional"))
      (node (ref "IC1") (pin "K3") (pinfunction "GND_23_K3") (pintype "bidirectional"))
      (node (ref "IC1") (pin "L10") (pinfunction "GND_29_L10") (pintype "bidirectional"))
      (node (ref "IC1") (pin "L11") (pinfunction "GND_30_L11") (pintype "bidirectional"))
      (node (ref "IC1") (pin "L12") (pinfunction "GND_31_L12") (pintype "bidirectional"))
      (node (ref "IC1") (pin "L13") (pinfunction "GND_32_L13") (pintype "bidirectional"))
      (node (ref "IC1") (pin "L15") (pinfunction "GND_33_L15") (pintype "bidirectional"))
      (node (ref "IC1") (pin "L20") (pinfunction "GND_34_L20") (pintype "bidirectional"))
      (node (ref "IC1") (pin "M10") (pinfunction "GND_35_M10") (pintype "bidirectional"))
      (node (ref "IC1") (pin "M11") (pinfunction "GND_36_M11") (pintype "bidirectional"))
      (node (ref "IC1") (pin "M12") (pinfunction "GND_37_M12") (pintype "bidirectional"))
      (node (ref "IC1") (pin "M13") (pinfunction "GND_38_M13") (pintype "bidirectional"))
      (node (ref "IC1") (pin "N10") (pinfunction "GND_40_N10") (pintype "bidirectional"))
      (node (ref "IC1") (pin "N11") (pinfunction "GND_41_N11") (pintype "bidirectional"))
      (node (ref "IC1") (pin "N12") (pinfunction "GND_42_N12") (pintype "bidirectional"))
      (node (ref "IC1") (pin "N13") (pinfunction "GND_43_N13") (pintype "bidirectional"))
      (node (ref "IC1") (pin "N15") (pinfunction "GND_44_N15") (pintype "bidirectional"))
      (node (ref "IC1") (pin "N3") (pinfunction "GND_39_N3") (pintype "bidirectional"))
      (node (ref "IC1") (pin "P19") (pinfunction "GND_46_P19") (pintype "bidirectional"))
      (node (ref "IC1") (pin "P8") (pinfunction "GND_45_P8") (pintype "bidirectional"))
      (node (ref "IC1") (pin "R11") (pinfunction "GND_49_R11") (pintype "bidirectional"))
      (node (ref "IC1") (pin "R13") (pinfunction "GND_50_R13") (pintype "bidirectional"))
      (node (ref "IC1") (pin "R3") (pinfunction "GND_47_R3") (pintype "bidirectional"))
      (node (ref "IC1") (pin "R9") (pinfunction "GND_48_R9") (pintype "bidirectional"))
      (node (ref "IC1") (pin "T20") (pinfunction "GND_51_T20") (pintype "bidirectional"))
      (node (ref "IC1") (pin "U3") (pinfunction "GND_52_U3") (pintype "bidirectional"))
      (node (ref "IC1") (pin "U5") (pinfunction "GNDA1_U5") (pintype "bidirectional"))
      (node (ref "IC1") (pin "V18") (pinfunction "GNDA4_V18") (pintype "bidirectional"))
      (node (ref "IC1") (pin "V20") (pinfunction "GND_53_V20") (pintype "bidirectional"))
      (node (ref "IC1") (pin "W3") (pinfunction "GND_54_W3") (pintype "bidirectional"))
      (node (ref "IC1") (pin "Y11") (pinfunction "GND_57_Y11") (pintype "bidirectional"))
      (node (ref "IC1") (pin "Y12") (pinfunction "GND_58_Y12") (pintype "bidirectional"))
      (node (ref "IC1") (pin "Y15") (pinfunction "GND_59_Y15") (pintype "bidirectional"))
      (node (ref "IC1") (pin "Y16") (pinfunction "GND_60_Y16") (pintype "bidirectional"))
      (node (ref "IC1") (pin "Y18") (pinfunction "GND_61_Y18") (pintype "bidirectional"))
      (node (ref "IC1") (pin "Y20") (pinfunction "GND_62_Y20") (pintype "bidirectional"))
      (node (ref "IC1") (pin "Y5") (pinfunction "GND_55_Y5") (pintype "bidirectional"))
      (node (ref "IC1") (pin "Y9") (pinfunction "GND_56_Y9") (pintype "bidirectional"))
      (node (ref "IC2") (pin "4") (pinfunction "GND_4") (pintype "bidirectional"))
      (node (ref "J1") (pin "10") (pinfunction "10_10") (pintype "passive"))
      (node (ref "J1") (pin "2") (pinfunction "2_2") (pintype "passive"))
      (node (ref "JP1") (pin "1") (pinfunction "1_1") (pintype "passive"))
      (node (ref "JP13") (pin "1") (pinfunction "1_1") (pintype "passive"))
      (node (ref "JP138") (pin "1") (pinfunction "1_1") (pintype "passive"))
      (node (ref "JP149") (pin "1") (pinfunction "1_1") (pintype "passive"))
      (node (ref "JP165") (pin "1") (pinfunction "1_1") (pintype "passive"))
      (node (ref "JP166") (pin "1") (pinfunction "1_1") (pintype "passive"))
      (node (ref "JP177") (pin "1") (pinfunction "1_1") (pintype "passive"))
      (node (ref "JP193") (pin "1") (pinfunction "1_1") (pintype "passive"))
      (node (ref "JP3") (pin "2") (pinfunction "2_2") (pintype "passive"))
      (node (ref "JP3") (pin "4") (pinfunction "4_4") (pintype "passive"))
      (node (ref "JP3") (pin "6") (pinfunction "6_6") (pintype "passive"))
      (node (ref "JP3") (pin "8") (pinfunction "8_8") (pintype "passive"))
      (node (ref "JP31") (pin "1") (pinfunction "1_1") (pintype "passive"))
      (node (ref "JP45") (pin "1") (pinfunction "1_1") (pintype "passive"))
      (node (ref "JP46") (pin "1") (pinfunction "1_1") (pintype "passive"))
      (node (ref "JP57") (pin "1") (pinfunction "1_1") (pintype "passive"))
      (node (ref "JP73") (pin "1") (pinfunction "1_1") (pintype "passive"))
      (node (ref "LED33") (pin "C") (pinfunction "C_C") (pintype "passive"))
      (node (ref "LED34") (pin "C") (pinfunction "C_C") (pintype "passive"))
      (node (ref "LED35") (pin "C") (pinfunction "C_C") (pintype "passive"))
      (node (ref "LED36") (pin "C") (pinfunction "C_C") (pintype "passive"))
      (node (ref "LED37") (pin "C") (pinfunction "C_C") (pintype "passive"))
      (node (ref "LED38") (pin "C") (pinfunction "C_C") (pintype "passive"))
      (node (ref "LED39") (pin "C") (pinfunction "C_C") (pintype "passive"))
      (node (ref "LED40") (pin "C") (pinfunction "C_C") (pintype "passive"))
      (node (ref "R12") (pin "P$1") (pinfunction "P$1_P$1") (pintype "bidirectional"))
      (node (ref "R4") (pin "P$2") (pinfunction "P$2_P$2") (pintype "bidirectional"))
      (node (ref "R6") (pin "P$2") (pinfunction "P$2_P$2") (pintype "bidirectional"))
      (node (ref "R8") (pin "P$2") (pinfunction "P$2_P$2") (pintype "bidirectional"))
      (node (ref "R9") (pin "P$2") (pinfunction "P$2_P$2") (pintype "bidirectional"))
      (node (ref "SW1") (pin "4") (pinfunction "B1_4") (pintype "bidirectional"))
      (node (ref "SW2") (pin "4") (pinfunction "B1_4") (pintype "bidirectional"))
      (node (ref "U1") (pin "P$2") (pinfunction "GND/ADJ_P$2") (pintype "bidirectional"))
      (node (ref "U2") (pin "P$2") (pinfunction "GND/ADJ_P$2") (pintype "bidirectional"))
      (node (ref "U3") (pin "P$2") (pinfunction "GND/ADJ_P$2") (pintype "bidirectional"))
      (node (ref "Y1") (pin "2") (pinfunction "GND_2") (pintype "bidirectional"))
    )
    (net (code "25") (name "IO1") (class "Default")
      (node (ref "C15") (pin "2") (pinfunction "2_2") (pintype "passive"))
      (node (ref "IC1") (pin "A3") (pinfunction "IO_1_A3") (pintype "bidirectional"))
      (node (ref "JP74") (pin "1") (pinfunction "1_1") (pintype "passive"))
      (node (ref "R1") (pin "P$1") (pinfunction "P$1_P$1") (pintype "bidirectional"))
      (node (ref "R45") (pin "P$1") (pinfunction "P$1_P$1") (pintype "bidirectional"))
      (node (ref "SW2") (pin "2") (pinfunction "A1_2") (pintype "bidirectional"))
    )
    (net (code "26") (name "IO2") (class "Default")
      (node (ref "IC1") (pin "A4") (pinfunction "IO_2_A4") (pintype "bidirectional"))
      (node (ref "JP76") (pin "1") (pinfunction "1_1") (pintype "passive"))
      (node (ref "R44") (pin "P$1") (pinfunction "P$1_P$1") (pintype "bidirectional"))
    )
    (net (code "27") (name "IO3") (class "Default")
      (node (ref "IC1") (pin "A5") (pinfunction "IO_3_A5") (pintype "bidirectional"))
      (node (ref "JP75") (pin "1") (pinfunction "1_1") (pintype "passive"))
      (node (ref "R43") (pin "P$1") (pinfunction "P$1_P$1") (pintype "bidirectional"))
    )
    (net (code "28") (name "IO4") (class "Default")
      (node (ref "IC1") (pin "A6") (pinfunction "IO_4_A6") (pintype "bidirectional"))
      (node (ref "JP77") (pin "1") (pinfunction "1_1") (pintype "passive"))
      (node (ref "R42") (pin "P$1") (pinfunction "P$1_P$1") (pintype "bidirectional"))
    )
    (net (code "29") (name "IO5") (class "Default")
      (node (ref "IC1") (pin "A7") (pinfunction "IO_5_A7") (pintype "bidirectional"))
      (node (ref "JP78") (pin "1") (pinfunction "1_1") (pintype "passive"))
      (node (ref "R41") (pin "P$1") (pinfunction "P$1_P$1") (pintype "bidirectional"))
    )
    (net (code "30") (name "IO6") (class "Default")
      (node (ref "IC1") (pin "A8") (pinfunction "IO_6_A8") (pintype "bidirectional"))
      (node (ref "JP80") (pin "1") (pinfunction "1_1") (pintype "passive"))
      (node (ref "R40") (pin "P$1") (pinfunction "P$1_P$1") (pintype "bidirectional"))
    )
    (net (code "31") (name "IO7") (class "Default")
      (node (ref "IC1") (pin "A9") (pinfunction "IO_7_A9") (pintype "bidirectional"))
      (node (ref "JP79") (pin "1") (pinfunction "1_1") (pintype "passive"))
    )
    (net (code "32") (name "IO8") (class "Default")
      (node (ref "IC1") (pin "A10") (pinfunction "IO_8_A10") (pintype "bidirectional"))
      (node (ref "JP81") (pin "1") (pinfunction "1_1") (pintype "passive"))
    )
    (net (code "33") (name "IO9") (class "Default")
      (node (ref "IC1") (pin "A13") (pinfunction "IO_9_A13") (pintype "bidirectional"))
      (node (ref "JP82") (pin "1") (pinfunction "1_1") (pintype "passive"))
    )
    (net (code "34") (name "IO10") (class "Default")
      (node (ref "IC1") (pin "A14") (pinfunction "IO_10_A14") (pintype "bidirectional"))
      (node (ref "JP84") (pin "1") (pinfunction "1_1") (pintype "passive"))
    )
    (net (code "35") (name "IO11") (class "Default")
      (node (ref "IC1") (pin "A15") (pinfunction "IO_11_A15") (pintype "bidirectional"))
      (node (ref "JP83") (pin "1") (pinfunction "1_1") (pintype "passive"))
    )
    (net (code "36") (name "IO12") (class "Default")
      (node (ref "IC1") (pin "A16") (pinfunction "IO_12_A16") (pintype "bidirectional"))
      (node (ref "JP85") (pin "1") (pinfunction "1_1") (pintype "passive"))
    )
    (net (code "37") (name "IO13") (class "Default")
      (node (ref "IC1") (pin "A17") (pinfunction "IO_13_A17") (pintype "bidirectional"))
      (node (ref "JP86") (pin "1") (pinfunction "1_1") (pintype "passive"))
    )
    (net (code "38") (name "IO14") (class "Default")
      (node (ref "IC1") (pin "A18") (pinfunction "IO_14_A18") (pintype "bidirectional"))
      (node (ref "JP88") (pin "1") (pinfunction "1_1") (pintype "passive"))
    )
    (net (code "39") (name "IO15") (class "Default")
      (node (ref "IC1") (pin "A19") (pinfunction "IO_15_A19") (pintype "bidirectional"))
      (node (ref "JP87") (pin "1") (pinfunction "1_1") (pintype "passive"))
    )
    (net (code "40") (name "IO16") (class "Default")
      (node (ref "IC1") (pin "A20") (pinfunction "IO_16_A20") (pintype "bidirectional"))
      (node (ref "JP89") (pin "1") (pinfunction "1_1") (pintype "passive"))
    )
    (net (code "41") (name "IO17") (class "Default")
      (node (ref "IC1") (pin "B1") (pinfunction "IO_17_B1") (pintype "bidirectional"))
      (node (ref "JP90") (pin "1") (pinfunction "1_1") (pintype "passive"))
    )
    (net (code "42") (name "IO18") (class "Default")
      (node (ref "IC1") (pin "B2") (pinfunction "IO_18_B2") (pintype "bidirectional"))
      (node (ref "JP92") (pin "1") (pinfunction "1_1") (pintype "passive"))
    )
    (net (code "43") (name "IO19") (class "Default")
      (node (ref "IC1") (pin "B3") (pinfunction "IO_19_B3") (pintype "bidirectional"))
      (node (ref "JP91") (pin "1") (pinfunction "1_1") (pintype "passive"))
    )
    (net (code "44") (name "IO20") (class "Default")
      (node (ref "IC1") (pin "B4") (pinfunction "IO_20_B4") (pintype "bidirectional"))
      (node (ref "JP93") (pin "1") (pinfunction "1_1") (pintype "passive"))
    )
    (net (code "45") (name "IO21") (class "Default")
      (node (ref "IC1") (pin "B5") (pinfunction "IO_21_B5") (pintype "bidirectional"))
      (node (ref "JP94") (pin "1") (pinfunction "1_1") (pintype "passive"))
    )
    (net (code "46") (name "IO22") (class "Default")
      (node (ref "IC1") (pin "B6") (pinfunction "IO_22_B6") (pintype "bidirectional"))
      (node (ref "JP96") (pin "1") (pinfunction "1_1") (pintype "passive"))
    )
    (net (code "47") (name "IO23") (class "Default")
      (node (ref "IC1") (pin "B7") (pinfunction "IO_23_B7") (pintype "bidirectional"))
      (node (ref "JP95") (pin "1") (pinfunction "1_1") (pintype "passive"))
    )
    (net (code "48") (name "IO24") (class "Default")
      (node (ref "IC1") (pin "B8") (pinfunction "IO_24_B8") (pintype "bidirectional"))
      (node (ref "JP97") (pin "1") (pinfunction "1_1") (pintype "passive"))
    )
    (net (code "49") (name "IO25") (class "Default")
      (node (ref "IC1") (pin "B9") (pinfunction "IO_25_B9") (pintype "bidirectional"))
      (node (ref "JP98") (pin "1") (pinfunction "1_1") (pintype "passive"))
    )
    (net (code "50") (name "IO26") (class "Default")
      (node (ref "IC1") (pin "B10") (pinfunction "IO_26_B10") (pintype "bidirectional"))
      (node (ref "JP100") (pin "1") (pinfunction "1_1") (pintype "passive"))
    )
    (net (code "51") (name "IO27") (class "Default")
      (node (ref "IC1") (pin "B13") (pinfunction "IO_27_B13") (pintype "bidirectional"))
      (node (ref "JP99") (pin "1") (pinfunction "1_1") (pintype "passive"))
    )
    (net (code "52") (name "IO28") (class "Default")
      (node (ref "IC1") (pin "B14") (pinfunction "IO_28_B14") (pintype "bidirectional"))
      (node (ref "JP101") (pin "1") (pinfunction "1_1") (pintype "passive"))
    )
    (net (code "53") (name "IO29") (class "Default")
      (node (ref "IC1") (pin "B15") (pinfunction "IO_29_B15") (pintype "bidirectional"))
      (node (ref "JP102") (pin "1") (pinfunction "1_1") (pintype "passive"))
    )
    (net (code "54") (name "IO30") (class "Default")
      (node (ref "IC1") (pin "B16") (pinfunction "IO_30_B16") (pintype "bidirectional"))
      (node (ref "JP104") (pin "1") (pinfunction "1_1") (pintype "passive"))
    )
    (net (code "55") (name "IO31") (class "Default")
      (node (ref "IC1") (pin "B17") (pinfunction "IO_31_B17") (pintype "bidirectional"))
      (node (ref "JP103") (pin "1") (pinfunction "1_1") (pintype "passive"))
    )
    (net (code "56") (name "IO32") (class "Default")
      (node (ref "IC1") (pin "B18") (pinfunction "IO_32_B18") (pintype "bidirectional"))
      (node (ref "JP105") (pin "1") (pinfunction "1_1") (pintype "passive"))
    )
    (net (code "57") (name "IO33") (class "Default")
      (node (ref "IC1") (pin "B19") (pinfunction "IO_33_B19") (pintype "bidirectional"))
      (node (ref "JP4") (pin "1") (pinfunction "1_1") (pintype "passive"))
    )
    (net (code "58") (name "IO34") (class "Default")
      (node (ref "IC1") (pin "B20") (pinfunction "IO_34_B20") (pintype "bidirectional"))
      (node (ref "JP2") (pin "1") (pinfunction "1_1") (pintype "passive"))
    )
    (net (code "59") (name "IO35") (class "Default")
      (node (ref "IC1") (pin "B21") (pinfunction "IO_35_B21") (pintype "bidirectional"))
      (node (ref "JP5") (pin "1") (pinfunction "1_1") (pintype "passive"))
    )
    (net (code "60") (name "IO36") (class "Default")
      (node (ref "IC1") (pin "B22") (pinfunction "IO_36_B22") (pintype "bidirectional"))
      (node (ref "JP6") (pin "1") (pinfunction "1_1") (pintype "passive"))
    )
    (net (code "61") (name "IO37") (class "Default")
      (node (ref "IC1") (pin "C1") (pinfunction "IO_37_C1") (pintype "bidirectional"))
      (node (ref "JP8") (pin "1") (pinfunction "1_1") (pintype "passive"))
    )
    (net (code "62") (name "IO38") (class "Default")
      (node (ref "IC1") (pin "C2") (pinfunction "IO_38_C2") (pintype "bidirectional"))
      (node (ref "JP7") (pin "1") (pinfunction "1_1") (pintype "passive"))
    )
    (net (code "63") (name "IO39") (class "Default")
      (node (ref "IC1") (pin "C3") (pinfunction "IO_39_C3") (pintype "bidirectional"))
      (node (ref "JP9") (pin "1") (pinfunction "1_1") (pintype "passive"))
    )
    (net (code "64") (name "IO40") (class "Default")
      (node (ref "IC1") (pin "C4") (pinfunction "IO_40_C4") (pintype "bidirectional"))
      (node (ref "JP10") (pin "1") (pinfunction "1_1") (pintype "passive"))
    )
    (net (code "65") (name "IO41") (class "Default")
      (node (ref "IC1") (pin "C6") (pinfunction "IO_41_C6") (pintype "bidirectional"))
      (node (ref "JP12") (pin "1") (pinfunction "1_1") (pintype "passive"))
    )
    (net (code "66") (name "IO42") (class "Default")
      (node (ref "IC1") (pin "C7") (pinfunction "IO_42_C7") (pintype "bidirectional"))
      (node (ref "JP11") (pin "1") (pinfunction "1_1") (pintype "passive"))
    )
    (net (code "67") (name "IO43") (class "Default")
      (node (ref "IC1") (pin "C8") (pinfunction "IO_43_C8") (pintype "bidirectional"))
      (node (ref "JP14") (pin "1") (pinfunction "1_1") (pintype "passive"))
    )
    (net (code "68") (name "IO44") (class "Default")
      (node (ref "IC1") (pin "C10") (pinfunction "IO_44_C10") (pintype "bidirectional"))
      (node (ref "JP15") (pin "1") (pinfunction "1_1") (pintype "passive"))
    )
    (net (code "69") (name "IO45") (class "Default")
      (node (ref "IC1") (pin "C13") (pinfunction "IO_45_C13") (pintype "bidirectional"))
      (node (ref "JP32") (pin "1") (pinfunction "1_1") (pintype "passive"))
    )
    (net (code "70") (name "IO46") (class "Default")
      (node (ref "IC1") (pin "C15") (pinfunction "IO_46_C15") (pintype "bidirectional"))
      (node (ref "JP34") (pin "1") (pinfunction "1_1") (pintype "passive"))
    )
    (net (code "71") (name "IO47") (class "Default")
      (node (ref "IC1") (pin "C17") (pinfunction "IO_47_C17") (pintype "bidirectional"))
      (node (ref "JP33") (pin "1") (pinfunction "1_1") (pintype "passive"))
    )
    (net (code "72") (name "IO48") (class "Default")
      (node (ref "IC1") (pin "C19") (pinfunction "IO_48_C19") (pintype "bidirectional"))
      (node (ref "JP35") (pin "1") (pinfunction "1_1") (pintype "passive"))
    )
    (net (code "73") (name "IO49") (class "Default")
      (node (ref "IC1") (pin "C20") (pinfunction "IO_49_C20") (pintype "bidirectional"))
      (node (ref "JP36") (pin "1") (pinfunction "1_1") (pintype "passive"))
    )
    (net (code "74") (name "IO50") (class "Default")
      (node (ref "IC1") (pin "C21") (pinfunction "IO_50_C21") (pintype "bidirectional"))
      (node (ref "JP38") (pin "1") (pinfunction "1_1") (pintype "passive"))
    )
    (net (code "75") (name "IO51") (class "Default")
      (node (ref "IC1") (pin "C22") (pinfunction "IO_51_C22") (pintype "bidirectional"))
      (node (ref "JP37") (pin "1") (pinfunction "1_1") (pintype "passive"))
    )
    (net (code "76") (name "IO53") (class "Default")
      (node (ref "IC1") (pin "D2") (pinfunction "IO_53_D2") (pintype "bidirectional"))
      (node (ref "JP40") (pin "1") (pinfunction "1_1") (pintype "passive"))
    )
    (net (code "77") (name "IO54") (class "Default")
      (node (ref "IC1") (pin "D6") (pinfunction "IO_54_D6") (pintype "bidirectional"))
      (node (ref "JP42") (pin "1") (pinfunction "1_1") (pintype "passive"))
    )
    (net (code "78") (name "IO55") (class "Default")
      (node (ref "IC1") (pin "D7") (pinfunction "IO_55_D7") (pintype "bidirectional"))
      (node (ref "JP41") (pin "1") (pinfunction "1_1") (pintype "passive"))
    )
    (net (code "79") (name "IO56") (class "Default")
      (node (ref "IC1") (pin "D10") (pinfunction "IO_56_D10") (pintype "bidirectional"))
      (node (ref "JP43") (pin "1") (pinfunction "1_1") (pintype "passive"))
    )
    (net (code "80") (name "IO57") (class "Default")
      (node (ref "IC1") (pin "D13") (pinfunction "IO_57_D13") (pintype "bidirectional"))
      (node (ref "JP44") (pin "1") (pinfunction "1_1") (pintype "passive"))
    )
    (net (code "81") (name "IO58") (class "Default")
      (node (ref "IC1") (pin "D15") (pinfunction "IO_58_D15") (pintype "bidirectional"))
      (node (ref "JP48") (pin "1") (pinfunction "1_1") (pintype "passive"))
    )
    (net (code "82") (name "IO59") (class "Default")
      (node (ref "IC1") (pin "D17") (pinfunction "IO_59_D17") (pintype "bidirectional"))
      (node (ref "JP47") (pin "1") (pinfunction "1_1") (pintype "passive"))
    )
    (net (code "83") (name "IO60") (class "Default")
      (node (ref "IC1") (pin "D19") (pinfunction "IO_60_D19") (pintype "bidirectional"))
      (node (ref "JP49") (pin "1") (pinfunction "1_1") (pintype "passive"))
    )
    (net (code "84") (name "IO61") (class "Default")
      (node (ref "IC1") (pin "D20") (pinfunction "IO_61_D20") (pintype "bidirectional"))
      (node (ref "JP50") (pin "1") (pinfunction "1_1") (pintype "passive"))
    )
    (net (code "85") (name "IO62") (class "Default")
      (node (ref "IC1") (pin "D21") (pinfunction "IO_62_D21") (pintype "bidirectional"))
      (node (ref "JP52") (pin "1") (pinfunction "1_1") (pintype "passive"))
    )
    (net (code "86") (name "IO63") (class "Default")
      (node (ref "IC1") (pin "D22") (pinfunction "IO_63_D22") (pintype "bidirectional"))
      (node (ref "JP51") (pin "1") (pinfunction "1_1") (pintype "passive"))
    )
    (net (code "87") (name "IO64") (class "Default")
      (node (ref "IC1") (pin "E1") (pinfunction "IO_64_E1") (pintype "bidirectional"))
      (node (ref "JP53") (pin "1") (pinfunction "1_1") (pintype "passive"))
    )
    (net (code "88") (name "IO66") (class "Default")
      (node (ref "IC1") (pin "E3") (pinfunction "IO_66_E3") (pintype "bidirectional"))
      (node (ref "JP56") (pin "1") (pinfunction "1_1") (pintype "passive"))
    )
    (net (code "89") (name "IO67") (class "Default")
      (node (ref "IC1") (pin "E4") (pinfunction "IO_67_E4") (pintype "bidirectional"))
      (node (ref "JP55") (pin "1") (pinfunction "1_1") (pintype "passive"))
    )
    (net (code "90") (name "IO68") (class "Default")
      (node (ref "IC1") (pin "E5") (pinfunction "IO_68_E5") (pintype "bidirectional"))
      (node (ref "JP58") (pin "1") (pinfunction "1_1") (pintype "passive"))
    )
    (net (code "91") (name "IO69") (class "Default")
      (node (ref "IC1") (pin "E6") (pinfunction "IO_69_E6") (pintype "bidirectional"))
      (node (ref "JP59") (pin "1") (pinfunction "1_1") (pintype "passive"))
    )
    (net (code "92") (name "IO70") (class "Default")
      (node (ref "IC1") (pin "E7") (pinfunction "IO_70_E7") (pintype "bidirectional"))
      (node (ref "JP60") (pin "1") (pinfunction "1_1") (pintype "passive"))
    )
    (net (code "93") (name "IO71") (class "Default")
      (node (ref "IC1") (pin "E9") (pinfunction "IO_71_E9") (pintype "bidirectional"))
      (node (ref "JP62") (pin "1") (pinfunction "1_1") (pintype "passive"))
    )
    (net (code "94") (name "IO72") (class "Default")
      (node (ref "IC1") (pin "E10") (pinfunction "IO_72_E10") (pintype "bidirectional"))
      (node (ref "JP61") (pin "1") (pinfunction "1_1") (pintype "passive"))
    )
    (net (code "95") (name "IO73") (class "Default")
      (node (ref "IC1") (pin "E11") (pinfunction "IO_73_E11") (pintype "bidirectional"))
      (node (ref "JP63") (pin "1") (pinfunction "1_1") (pintype "passive"))
    )
    (net (code "96") (name "IO74") (class "Default")
      (node (ref "IC1") (pin "E12") (pinfunction "IO_74_E12") (pintype "bidirectional"))
      (node (ref "JP64") (pin "1") (pinfunction "1_1") (pintype "passive"))
    )
    (net (code "97") (name "IO75") (class "Default")
      (node (ref "IC1") (pin "E13") (pinfunction "IO_75_E13") (pintype "bidirectional"))
      (node (ref "JP66") (pin "1") (pinfunction "1_1") (pintype "passive"))
    )
    (net (code "98") (name "IO76") (class "Default")
      (node (ref "IC1") (pin "E14") (pinfunction "IO_76_E14") (pintype "bidirectional"))
      (node (ref "JP65") (pin "1") (pinfunction "1_1") (pintype "passive"))
    )
    (net (code "99") (name "IO77") (class "Default")
      (node (ref "IC1") (pin "E15") (pinfunction "IO_77_E15") (pintype "bidirectional"))
      (node (ref "JP67") (pin "1") (pinfunction "1_1") (pintype "passive"))
    )
    (net (code "100") (name "IO78") (class "Default")
      (node (ref "IC1") (pin "E16") (pinfunction "IO_78_E16") (pintype "bidirectional"))
      (node (ref "JP68") (pin "1") (pinfunction "1_1") (pintype "passive"))
    )
    (net (code "101") (name "IO79") (class "Default")
      (node (ref "IC1") (pin "E21") (pinfunction "IO_79_E21") (pintype "bidirectional"))
      (node (ref "JP70") (pin "1") (pinfunction "1_1") (pintype "passive"))
    )
    (net (code "102") (name "IO80") (class "Default")
      (node (ref "IC1") (pin "E22") (pinfunction "IO_80_E22") (pintype "bidirectional"))
      (node (ref "JP69") (pin "1") (pinfunction "1_1") (pintype "passive"))
    )
    (net (code "103") (name "IO81") (class "Default")
      (node (ref "IC1") (pin "F1") (pinfunction "IO_81_F1") (pintype "bidirectional"))
      (node (ref "JP71") (pin "1") (pinfunction "1_1") (pintype "passive"))
    )
    (net (code "104") (name "IO82") (class "Default")
      (node (ref "IC1") (pin "F2") (pinfunction "IO_82_F2") (pintype "bidirectional"))
      (node (ref "JP72") (pin "1") (pinfunction "1_1") (pintype "passive"))
    )
    (net (code "105") (name "IO83") (class "Default")
      (node (ref "IC1") (pin "F7") (pinfunction "IO_83_F7") (pintype "bidirectional"))
      (node (ref "JP140") (pin "1") (pinfunction "1_1") (pintype "passive"))
    )
    (net (code "106") (name "IO84") (class "Default")
      (node (ref "IC1") (pin "F8") (pinfunction "IO_84_F8") (pintype "bidirectional"))
      (node (ref "JP139") (pin "1") (pinfunction "1_1") (pintype "passive"))
    )
    (net (code "107") (name "IO85") (class "Default")
      (node (ref "IC1") (pin "F9") (pinfunction "IO_85_F9") (pintype "bidirectional"))
      (node (ref "JP141") (pin "1") (pinfunction "1_1") (pintype "passive"))
    )
    (net (code "108") (name "IO86") (class "Default")
      (node (ref "IC1") (pin "F10") (pinfunction "IO_86_F10") (pintype "bidirectional"))
      (node (ref "JP142") (pin "1") (pinfunction "1_1") (pintype "passive"))
    )
    (net (code "109") (name "IO87") (class "Default")
      (node (ref "IC1") (pin "F11") (pinfunction "IO_87_F11") (pintype "bidirectional"))
      (node (ref "JP144") (pin "1") (pinfunction "1_1") (pintype "passive"))
    )
    (net (code "110") (name "IO88") (class "Default")
      (node (ref "IC1") (pin "F13") (pinfunction "IO_88_F13") (pintype "bidirectional"))
      (node (ref "JP143") (pin "1") (pinfunction "1_1") (pintype "passive"))
    )
    (net (code "111") (name "IO89") (class "Default")
      (node (ref "IC1") (pin "F14") (pinfunction "IO_89_F14") (pintype "bidirectional"))
      (node (ref "JP145") (pin "1") (pinfunction "1_1") (pintype "passive"))
    )
    (net (code "112") (name "IO90") (class "Default")
      (node (ref "IC1") (pin "F15") (pinfunction "IO_90_F15") (pintype "bidirectional"))
      (node (ref "JP146") (pin "1") (pinfunction "1_1") (pintype "passive"))
    )
    (net (code "113") (name "IO91") (class "Default")
      (node (ref "IC1") (pin "F16") (pinfunction "IO_91_F16") (pintype "bidirectional"))
      (node (ref "JP148") (pin "1") (pinfunction "1_1") (pintype "passive"))
    )
    (net (code "114") (name "IO92") (class "Default")
      (node (ref "IC1") (pin "F17") (pinfunction "IO_92_F17") (pintype "bidirectional"))
      (node (ref "JP147") (pin "1") (pinfunction "1_1") (pintype "passive"))
    )
    (net (code "115") (name "IO93") (class "Default")
      (node (ref "IC1") (pin "F19") (pinfunction "IO_93_F19") (pintype "bidirectional"))
      (node (ref "JP150") (pin "1") (pinfunction "1_1") (pintype "passive"))
    )
    (net (code "116") (name "IO94") (class "Default")
      (node (ref "IC1") (pin "F20") (pinfunction "IO_94_F20") (pintype "bidirectional"))
      (node (ref "JP151") (pin "1") (pinfunction "1_1") (pintype "passive"))
    )
    (net (code "117") (name "IO95") (class "Default")
      (node (ref "IC1") (pin "F21") (pinfunction "IO_95_F21") (pintype "bidirectional"))
      (node (ref "JP152") (pin "1") (pinfunction "1_1") (pintype "passive"))
    )
    (net (code "118") (name "IO96") (class "Default")
      (node (ref "IC1") (pin "F22") (pinfunction "IO_96_F22") (pintype "bidirectional"))
      (node (ref "JP154") (pin "1") (pinfunction "1_1") (pintype "passive"))
    )
    (net (code "119") (name "IO97") (class "Default")
      (node (ref "IC1") (pin "G3") (pinfunction "IO_97_G3") (pintype "bidirectional"))
      (node (ref "JP153") (pin "1") (pinfunction "1_1") (pintype "passive"))
    )
    (net (code "120") (name "IO98") (class "Default")
      (node (ref "IC1") (pin "G4") (pinfunction "IO_98_G4") (pintype "bidirectional"))
      (node (ref "JP155") (pin "1") (pinfunction "1_1") (pintype "passive"))
    )
    (net (code "121") (name "IO99") (class "Default")
      (node (ref "IC1") (pin "G5") (pinfunction "IO_99_G5") (pintype "bidirectional"))
      (node (ref "JP156") (pin "1") (pinfunction "1_1") (pintype "passive"))
    )
    (net (code "122") (name "IO100") (class "Default")
      (node (ref "IC1") (pin "G7") (pinfunction "IO_100_G7") (pintype "bidirectional"))
      (node (ref "JP158") (pin "1") (pinfunction "1_1") (pintype "passive"))
    )
    (net (code "123") (name "IO101") (class "Default")
      (node (ref "IC1") (pin "G8") (pinfunction "IO_101_G8") (pintype "bidirectional"))
      (node (ref "JP157") (pin "1") (pinfunction "1_1") (pintype "passive"))
    )
    (net (code "124") (name "IO102") (class "Default")
      (node (ref "IC1") (pin "G9") (pinfunction "IO_102_G9") (pintype "bidirectional"))
      (node (ref "JP159") (pin "1") (pinfunction "1_1") (pintype "passive"))
    )
    (net (code "125") (name "IO103") (class "Default")
      (node (ref "IC1") (pin "G10") (pinfunction "IO_103_G10") (pintype "bidirectional"))
      (node (ref "JP160") (pin "1") (pinfunction "1_1") (pintype "passive"))
    )
    (net (code "126") (name "IO104") (class "Default")
      (node (ref "IC1") (pin "G11") (pinfunction "IO_104_G11") (pintype "bidirectional"))
      (node (ref "JP162") (pin "1") (pinfunction "1_1") (pintype "passive"))
    )
    (net (code "127") (name "IO105") (class "Default")
      (node (ref "IC1") (pin "G13") (pinfunction "IO_105_G13") (pintype "bidirectional"))
      (node (ref "JP161") (pin "1") (pinfunction "1_1") (pintype "passive"))
    )
    (net (code "128") (name "IO106") (class "Default")
      (node (ref "IC1") (pin "G14") (pinfunction "IO_106_G14") (pintype "bidirectional"))
      (node (ref "JP163") (pin "1") (pinfunction "1_1") (pintype "passive"))
    )
    (net (code "129") (name "IO107") (class "Default")
      (node (ref "IC1") (pin "G15") (pinfunction "IO_107_G15") (pintype "bidirectional"))
      (node (ref "JP164") (pin "1") (pinfunction "1_1") (pintype "passive"))
    )
    (net (code "130") (name "IO108") (class "Default")
      (node (ref "IC1") (pin "G16") (pinfunction "IO_108_G16") (pintype "bidirectional"))
      (node (ref "JP168") (pin "1") (pinfunction "1_1") (pintype "passive"))
    )
    (net (code "131") (name "IO109") (class "Default")
      (node (ref "IC1") (pin "G17") (pinfunction "IO_109_G17") (pintype "bidirectional"))
      (node (ref "JP167") (pin "1") (pinfunction "1_1") (pintype "passive"))
    )
    (net (code "132") (name "IO110") (class "Default")
      (node (ref "IC1") (pin "G18") (pinfunction "IO_110_G18") (pintype "bidirectional"))
      (node (ref "JP169") (pin "1") (pinfunction "1_1") (pintype "passive"))
    )
    (net (code "133") (name "IO111") (class "Default")
      (node (ref "IC1") (pin "H1") (pinfunction "IO_111_H1") (pintype "bidirectional"))
      (node (ref "JP170") (pin "1") (pinfunction "1_1") (pintype "passive"))
    )
    (net (code "134") (name "IO112") (class "Default")
      (node (ref "IC1") (pin "H2") (pinfunction "IO_112_H2") (pintype "bidirectional"))
      (node (ref "JP172") (pin "1") (pinfunction "1_1") (pintype "passive"))
    )
    (net (code "135") (name "IO113") (class "Default")
      (node (ref "IC1") (pin "H5") (pinfunction "IO_113_H5") (pintype "bidirectional"))
      (node (ref "JP171") (pin "1") (pinfunction "1_1") (pintype "passive"))
    )
    (net (code "136") (name "IO114") (class "Default")
      (node (ref "IC1") (pin "H6") (pinfunction "IO_114_H6") (pintype "bidirectional"))
      (node (ref "JP173") (pin "1") (pinfunction "1_1") (pintype "passive"))
    )
    (net (code "137") (name "IO115") (class "Default")
      (node (ref "IC1") (pin "H7") (pinfunction "IO_115_H7") (pintype "bidirectional"))
      (node (ref "JP174") (pin "1") (pinfunction "1_1") (pintype "passive"))
    )
    (net (code "138") (name "IO116") (class "Default")
      (node (ref "IC1") (pin "H8") (pinfunction "IO_116_H8") (pintype "bidirectional"))
      (node (ref "JP176") (pin "1") (pinfunction "1_1") (pintype "passive"))
    )
    (net (code "139") (name "IO117") (class "Default")
      (node (ref "IC1") (pin "H10") (pinfunction "IO_117_H10") (pintype "bidirectional"))
      (node (ref "JP175") (pin "1") (pinfunction "1_1") (pintype "passive"))
    )
    (net (code "140") (name "IO118") (class "Default")
      (node (ref "IC1") (pin "H11") (pinfunction "IO_118_H11") (pintype "bidirectional"))
      (node (ref "JP178") (pin "1") (pinfunction "1_1") (pintype "passive"))
    )
    (net (code "141") (name "IO119") (class "Default")
      (node (ref "IC1") (pin "H14") (pinfunction "IO_119_H14") (pintype "bidirectional"))
      (node (ref "JP179") (pin "1") (pinfunction "1_1") (pintype "passive"))
    )
    (net (code "142") (name "IO120") (class "Default")
      (node (ref "IC1") (pin "H15") (pinfunction "IO_120_H15") (pintype "bidirectional"))
      (node (ref "JP180") (pin "1") (pinfunction "1_1") (pintype "passive"))
    )
    (net (code "143") (name "IO121") (class "Default")
      (node (ref "IC1") (pin "H16") (pinfunction "IO_121_H16") (pintype "bidirectional"))
      (node (ref "JP182") (pin "1") (pinfunction "1_1") (pintype "passive"))
    )
    (net (code "144") (name "IO122") (class "Default")
      (node (ref "IC1") (pin "H17") (pinfunction "IO_122_H17") (pintype "bidirectional"))
      (node (ref "JP181") (pin "1") (pinfunction "1_1") (pintype "passive"))
    )
    (net (code "145") (name "IO123") (class "Default")
      (node (ref "IC1") (pin "H18") (pinfunction "IO_123_H18") (pintype "bidirectional"))
      (node (ref "JP183") (pin "1") (pinfunction "1_1") (pintype "passive"))
    )
    (net (code "146") (name "IO124") (class "Default")
      (node (ref "IC1") (pin "H19") (pinfunction "IO_124_H19") (pintype "bidirectional"))
      (node (ref "JP184") (pin "1") (pinfunction "1_1") (pintype "passive"))
    )
    (net (code "147") (name "IO125") (class "Default")
      (node (ref "IC1") (pin "H20") (pinfunction "IO_125_H20") (pintype "bidirectional"))
      (node (ref "JP186") (pin "1") (pinfunction "1_1") (pintype "passive"))
    )
    (net (code "148") (name "IO126") (class "Default")
      (node (ref "IC1") (pin "H21") (pinfunction "IO_126_H21") (pintype "bidirectional"))
      (node (ref "JP185") (pin "1") (pinfunction "1_1") (pintype "passive"))
    )
    (net (code "149") (name "IO127") (class "Default")
      (node (ref "IC1") (pin "H22") (pinfunction "IO_127_H22") (pintype "bidirectional"))
      (node (ref "JP187") (pin "1") (pinfunction "1_1") (pintype "passive"))
    )
    (net (code "150") (name "IO128") (class "Default")
      (node (ref "IC1") (pin "J1") (pinfunction "IO_128_J1") (pintype "bidirectional"))
      (node (ref "JP188") (pin "1") (pinfunction "1_1") (pintype "passive"))
    )
    (net (code "151") (name "IO129") (class "Default")
      (node (ref "IC1") (pin "J2") (pinfunction "IO_129_J2") (pintype "bidirectional"))
      (node (ref "JP190") (pin "1") (pinfunction "1_1") (pintype "passive"))
    )
    (net (code "152") (name "IO130") (class "Default")
      (node (ref "IC1") (pin "J3") (pinfunction "IO_130_J3") (pintype "bidirectional"))
      (node (ref "JP189") (pin "1") (pinfunction "1_1") (pintype "passive"))
    )
    (net (code "153") (name "IO131") (class "Default")
      (node (ref "IC1") (pin "J4") (pinfunction "IO_131_J4") (pintype "bidirectional"))
      (node (ref "JP191") (pin "1") (pinfunction "1_1") (pintype "passive"))
    )
    (net (code "154") (name "IO132") (class "Default")
      (node (ref "IC1") (pin "J5") (pinfunction "IO_132_J5") (pintype "bidirectional"))
      (node (ref "JP192") (pin "1") (pinfunction "1_1") (pintype "passive"))
    )
    (net (code "155") (name "IO133") (class "Default")
      (node (ref "IC1") (pin "J6") (pinfunction "IO_133_J6") (pintype "bidirectional"))
      (node (ref "JP106") (pin "1") (pinfunction "1_1") (pintype "passive"))
    )
    (net (code "156") (name "IO134") (class "Default")
      (node (ref "IC1") (pin "J7") (pinfunction "IO_134_J7") (pintype "bidirectional"))
      (node (ref "JP108") (pin "1") (pinfunction "1_1") (pintype "passive"))
    )
    (net (code "157") (name "IO135") (class "Default")
      (node (ref "IC1") (pin "J8") (pinfunction "IO_135_J8") (pintype "bidirectional"))
      (node (ref "JP107") (pin "1") (pinfunction "1_1") (pintype "passive"))
    )
    (net (code "158") (name "IO136") (class "Default")
      (node (ref "IC1") (pin "J17") (pinfunction "IO_136_J17") (pintype "bidirectional"))
      (node (ref "JP109") (pin "1") (pinfunction "1_1") (pintype "passive"))
    )
    (net (code "159") (name "IO137") (class "Default")
      (node (ref "IC1") (pin "J18") (pinfunction "IO_137_J18") (pintype "bidirectional"))
      (node (ref "JP110") (pin "1") (pinfunction "1_1") (pintype "passive"))
    )
    (net (code "160") (name "IO138") (class "Default")
      (node (ref "IC1") (pin "J21") (pinfunction "IO_138_J21") (pintype "bidirectional"))
      (node (ref "JP112") (pin "1") (pinfunction "1_1") (pintype "passive"))
    )
    (net (code "161") (name "IO139") (class "Default")
      (node (ref "IC1") (pin "J22") (pinfunction "IO_139_J22") (pintype "bidirectional"))
      (node (ref "JP111") (pin "1") (pinfunction "1_1") (pintype "passive"))
    )
    (net (code "162") (name "IO141") (class "Default")
      (node (ref "IC1") (pin "K7") (pinfunction "IO_141_K7") (pintype "bidirectional"))
      (node (ref "JP114") (pin "1") (pinfunction "1_1") (pintype "passive"))
    )
    (net (code "163") (name "IO142") (class "Default")
      (node (ref "IC1") (pin "K8") (pinfunction "IO_142_K8") (pintype "bidirectional"))
      (node (ref "JP116") (pin "1") (pinfunction "1_1") (pintype "passive"))
    )
    (net (code "164") (name "IO143") (class "Default")
      (node (ref "IC1") (pin "K17") (pinfunction "IO_143_K17") (pintype "bidirectional"))
      (node (ref "JP115") (pin "1") (pinfunction "1_1") (pintype "passive"))
    )
    (net (code "165") (name "IO144") (class "Default")
      (node (ref "IC1") (pin "K18") (pinfunction "IO_144_K18") (pintype "bidirectional"))
      (node (ref "JP117") (pin "1") (pinfunction "1_1") (pintype "passive"))
    )
    (net (code "166") (name "IO145") (class "Default")
      (node (ref "IC1") (pin "K19") (pinfunction "IO_145_K19") (pintype "bidirectional"))
      (node (ref "JP118") (pin "1") (pinfunction "1_1") (pintype "passive"))
    )
    (net (code "167") (name "IO146") (class "Default")
      (node (ref "IC1") (pin "K21") (pinfunction "IO_146_K21") (pintype "bidirectional"))
      (node (ref "JP120") (pin "1") (pinfunction "1_1") (pintype "passive"))
    )
    (net (code "168") (name "IO147") (class "Default")
      (node (ref "IC1") (pin "K22") (pinfunction "IO_147_K22") (pintype "bidirectional"))
      (node (ref "JP119") (pin "1") (pinfunction "1_1") (pintype "passive"))
    )
    (net (code "169") (name "IO148") (class "Default")
      (node (ref "IC1") (pin "L6") (pinfunction "IO_148_L6") (pintype "bidirectional"))
      (node (ref "JP121") (pin "1") (pinfunction "1_1") (pintype "passive"))
    )
    (net (code "170") (name "IO149") (class "Default")
      (node (ref "IC1") (pin "L7") (pinfunction "IO_149_L7") (pintype "bidirectional"))
      (node (ref "JP122") (pin "1") (pinfunction "1_1") (pintype "passive"))
    )
    (net (code "171") (name "IO150") (class "Default")
      (node (ref "IC1") (pin "L8") (pinfunction "IO_150_L8") (pintype "bidirectional"))
      (node (ref "JP124") (pin "1") (pinfunction "1_1") (pintype "passive"))
    )
    (net (code "172") (name "IO151") (class "Default")
      (node (ref "IC1") (pin "L21") (pinfunction "IO_151_L21") (pintype "bidirectional"))
      (node (ref "JP123") (pin "1") (pinfunction "1_1") (pintype "passive"))
    )
    (net (code "173") (name "IO152") (class "Default")
      (node (ref "IC1") (pin "L22") (pinfunction "IO_152_L22") (pintype "bidirectional"))
      (node (ref "JP125") (pin "1") (pinfunction "1_1") (pintype "passive"))
    )
    (net (code "174") (name "IO153") (class "Default")
      (node (ref "IC1") (pin "M1") (pinfunction "IO_153_M1") (pintype "bidirectional"))
      (node (ref "JP126") (pin "1") (pinfunction "1_1") (pintype "passive"))
    )
    (net (code "175") (name "IO154") (class "Default")
      (node (ref "IC1") (pin "M2") (pinfunction "IO_154_M2") (pintype "bidirectional"))
      (node (ref "JP128") (pin "1") (pinfunction "1_1") (pintype "passive"))
    )
    (net (code "176") (name "IO155") (class "Default")
      (node (ref "IC1") (pin "M3") (pinfunction "IO_155_M3") (pintype "bidirectional"))
      (node (ref "JP127") (pin "1") (pinfunction "1_1") (pintype "passive"))
    )
    (net (code "177") (name "IO156") (class "Default")
      (node (ref "IC1") (pin "M4") (pinfunction "IO_156_M4") (pintype "bidirectional"))
      (node (ref "JP129") (pin "1") (pinfunction "1_1") (pintype "passive"))
    )
    (net (code "178") (name "IO157") (class "Default")
      (node (ref "IC1") (pin "M5") (pinfunction "IO_157_M5") (pintype "bidirectional"))
      (node (ref "JP130") (pin "1") (pinfunction "1_1") (pintype "passive"))
    )
    (net (code "179") (name "IO158") (class "Default")
      (node (ref "IC1") (pin "M6") (pinfunction "IO_158_M6") (pintype "bidirectional"))
      (node (ref "JP132") (pin "1") (pinfunction "1_1") (pintype "passive"))
    )
    (net (code "180") (name "IO159") (class "Default")
      (node (ref "IC1") (pin "M7") (pinfunction "IO_159_M7") (pintype "bidirectional"))
      (node (ref "JP131") (pin "1") (pinfunction "1_1") (pintype "passive"))
    )
    (net (code "181") (name "IO160") (class "Default")
      (node (ref "IC1") (pin "M8") (pinfunction "IO_160_M8") (pintype "bidirectional"))
      (node (ref "JP133") (pin "1") (pinfunction "1_1") (pintype "passive"))
    )
    (net (code "182") (name "IO161") (class "Default")
      (node (ref "IC1") (pin "M16") (pinfunction "IO_161_M16") (pintype "bidirectional"))
      (node (ref "JP134") (pin "1") (pinfunction "1_1") (pintype "passive"))
    )
    (net (code "183") (name "IO162") (class "Default")
      (node (ref "IC1") (pin "M19") (pinfunction "IO_162_M19") (pintype "bidirectional"))
      (node (ref "JP136") (pin "1") (pinfunction "1_1") (pintype "passive"))
    )
    (net (code "184") (name "IO163") (class "Default")
      (node (ref "IC1") (pin "M20") (pinfunction "IO_163_M20") (pintype "bidirectional"))
      (node (ref "JP135") (pin "1") (pinfunction "1_1") (pintype "passive"))
    )
    (net (code "185") (name "IO164") (class "Default")
      (node (ref "IC1") (pin "M21") (pinfunction "IO_164_M21") (pintype "bidirectional"))
      (node (ref "JP137") (pin "1") (pinfunction "1_1") (pintype "passive"))
    )
    (net (code "186") (name "IO165") (class "Default")
      (node (ref "IC1") (pin "M22") (pinfunction "IO_165_M22") (pintype "bidirectional"))
      (node (ref "JP194") (pin "1") (pinfunction "1_1") (pintype "passive"))
    )
    (net (code "187") (name "IO166") (class "Default")
      (node (ref "IC1") (pin "N1") (pinfunction "IO_166_N1") (pintype "bidirectional"))
      (node (ref "JP196") (pin "1") (pinfunction "1_1") (pintype "passive"))
    )
    (net (code "188") (name "IO167") (class "Default")
      (node (ref "IC1") (pin "N2") (pinfunction "IO_167_N2") (pintype "bidirectional"))
      (node (ref "JP195") (pin "1") (pinfunction "1_1") (pintype "passive"))
    )
    (net (code "189") (name "IO168") (class "Default")
      (node (ref "IC1") (pin "N5") (pinfunction "IO_168_N5") (pintype "bidirectional"))
      (node (ref "JP197") (pin "1") (pinfunction "1_1") (pintype "passive"))
    )
    (net (code "190") (name "IO169") (class "Default")
      (node (ref "IC1") (pin "N6") (pinfunction "IO_169_N6") (pintype "bidirectional"))
      (node (ref "JP198") (pin "1") (pinfunction "1_1") (pintype "passive"))
    )
    (net (code "191") (name "IO170") (class "Default")
      (node (ref "IC1") (pin "N7") (pinfunction "IO_170_N7") (pintype "bidirectional"))
      (node (ref "JP200") (pin "1") (pinfunction "1_1") (pintype "passive"))
    )
    (net (code "192") (name "IO171") (class "Default")
      (node (ref "IC1") (pin "N8") (pinfunction "IO_171_N8") (pintype "bidirectional"))
      (node (ref "JP199") (pin "1") (pinfunction "1_1") (pintype "passive"))
    )
    (net (code "193") (name "IO172") (class "Default")
      (node (ref "IC1") (pin "N16") (pinfunction "IO_172_N16") (pintype "bidirectional"))
      (node (ref "JP201") (pin "1") (pinfunction "1_1") (pintype "passive"))
    )
    (net (code "194") (name "IO173") (class "Default")
      (node (ref "IC1") (pin "N17") (pinfunction "IO_173_N17") (pintype "bidirectional"))
      (node (ref "JP202") (pin "1") (pinfunction "1_1") (pintype "passive"))
    )
    (net (code "195") (name "IO174") (class "Default")
      (node (ref "IC1") (pin "N18") (pinfunction "IO_174_N18") (pintype "bidirectional"))
      (node (ref "JP204") (pin "1") (pinfunction "1_1") (pintype "passive"))
    )
    (net (code "196") (name "IO175") (class "Default")
      (node (ref "IC1") (pin "N19") (pinfunction "IO_175_N19") (pintype "bidirectional"))
      (node (ref "JP203") (pin "1") (pinfunction "1_1") (pintype "passive"))
    )
    (net (code "197") (name "IO176") (class "Default")
      (node (ref "IC1") (pin "N20") (pinfunction "IO_176_N20") (pintype "bidirectional"))
      (node (ref "JP205") (pin "1") (pinfunction "1_1") (pintype "passive"))
    )
    (net (code "198") (name "IO177") (class "Default")
      (node (ref "IC1") (pin "N21") (pinfunction "IO_177_N21") (pintype "bidirectional"))
      (node (ref "JP206") (pin "1") (pinfunction "1_1") (pintype "passive"))
    )
    (net (code "199") (name "IO178") (class "Default")
      (node (ref "IC1") (pin "N22") (pinfunction "IO_178_N22") (pintype "bidirectional"))
      (node (ref "JP207") (pin "1") (pinfunction "1_1") (pintype "passive"))
    )
    (net (code "200") (name "IO179") (class "Default")
      (node (ref "IC1") (pin "P1") (pinfunction "IO_179_P1") (pintype "bidirectional"))
      (node (ref "JP208") (pin "1") (pinfunction "1_1") (pintype "passive"))
    )
    (net (code "201") (name "IO180") (class "Default")
      (node (ref "IC1") (pin "P2") (pinfunction "IO_180_P2") (pintype "bidirectional"))
      (node (ref "JP210") (pin "1") (pinfunction "1_1") (pintype "passive"))
    )
    (net (code "202") (name "IO181") (class "Default")
      (node (ref "IC1") (pin "P3") (pinfunction "IO_181_P3") (pintype "bidirectional"))
      (node (ref "JP209") (pin "1") (pinfunction "1_1") (pintype "passive"))
    )
    (net (code "203") (name "IO182") (class "Default")
      (node (ref "IC1") (pin "P4") (pinfunction "IO_182_P4") (pintype "bidirectional"))
      (node (ref "JP211") (pin "1") (pinfunction "1_1") (pintype "passive"))
    )
    (net (code "204") (name "IO183") (class "Default")
      (node (ref "IC1") (pin "P5") (pinfunction "IO_183_P5") (pintype "bidirectional"))
      (node (ref "JP212") (pin "1") (pinfunction "1_1") (pintype "passive"))
    )
    (net (code "205") (name "IO184") (class "Default")
      (node (ref "IC1") (pin "P6") (pinfunction "IO_184_P6") (pintype "bidirectional"))
      (node (ref "JP214") (pin "1") (pinfunction "1_1") (pintype "passive"))
    )
    (net (code "206") (name "IO185") (class "Default")
      (node (ref "IC1") (pin "P7") (pinfunction "IO_185_P7") (pintype "bidirectional"))
      (node (ref "JP213") (pin "1") (pinfunction "1_1") (pintype "passive"))
    )
    (net (code "207") (name "IO186") (class "Default")
      (node (ref "IC1") (pin "P15") (pinfunction "IO_186_P15") (pintype "bidirectional"))
      (node (ref "JP215") (pin "1") (pinfunction "1_1") (pintype "passive"))
    )
    (net (code "208") (name "IO187") (class "Default")
      (node (ref "IC1") (pin "P16") (pinfunction "IO_187_P16") (pintype "bidirectional"))
      (node (ref "JP216") (pin "1") (pinfunction "1_1") (pintype "passive"))
    )
    (net (code "209") (name "IO188") (class "Default")
      (node (ref "IC1") (pin "P17") (pinfunction "IO_188_P17") (pintype "bidirectional"))
      (node (ref "JP218") (pin "1") (pinfunction "1_1") (pintype "passive"))
    )
    (net (code "210") (name "IO189") (class "Default")
      (node (ref "IC1") (pin "P20") (pinfunction "IO_189_P20") (pintype "bidirectional"))
      (node (ref "JP217") (pin "1") (pinfunction "1_1") (pintype "passive"))
    )
    (net (code "211") (name "IO190") (class "Default")
      (node (ref "IC1") (pin "P21") (pinfunction "IO_190_P21") (pintype "bidirectional"))
      (node (ref "JP219") (pin "1") (pinfunction "1_1") (pintype "passive"))
    )
    (net (code "212") (name "IO191") (class "Default")
      (node (ref "IC1") (pin "P22") (pinfunction "IO_191_P22") (pintype "bidirectional"))
      (node (ref "JP220") (pin "1") (pinfunction "1_1") (pintype "passive"))
    )
    (net (code "213") (name "IO192") (class "Default")
      (node (ref "IC1") (pin "R1") (pinfunction "IO_192_R1") (pintype "bidirectional"))
      (node (ref "JP221") (pin "1") (pinfunction "1_1") (pintype "passive"))
    )
    (net (code "214") (name "IO193") (class "Default")
      (node (ref "IC1") (pin "R2") (pinfunction "IO_193_R2") (pintype "bidirectional"))
      (node (ref "JP222") (pin "1") (pinfunction "1_1") (pintype "passive"))
    )
    (net (code "215") (name "IO194") (class "Default")
      (node (ref "IC1") (pin "R5") (pinfunction "IO_194_R5") (pintype "bidirectional"))
      (node (ref "JP224") (pin "1") (pinfunction "1_1") (pintype "passive"))
    )
    (net (code "216") (name "IO195") (class "Default")
      (node (ref "IC1") (pin "R6") (pinfunction "IO_195_R6") (pintype "bidirectional"))
      (node (ref "JP223") (pin "1") (pinfunction "1_1") (pintype "passive"))
    )
    (net (code "217") (name "IO196") (class "Default")
      (node (ref "IC1") (pin "R7") (pinfunction "IO_196_R7") (pintype "bidirectional"))
      (node (ref "JP225") (pin "1") (pinfunction "1_1") (pintype "passive"))
    )
    (net (code "218") (name "IO197") (class "Default")
      (node (ref "IC1") (pin "R14") (pinfunction "IO_197_R14") (pintype "bidirectional"))
      (node (ref "JP226") (pin "1") (pinfunction "1_1") (pintype "passive"))
    )
    (net (code "219") (name "IO198") (class "Default")
      (node (ref "IC1") (pin "R15") (pinfunction "IO_198_R15") (pintype "bidirectional"))
      (node (ref "JP228") (pin "1") (pinfunction "1_1") (pintype "passive"))
    )
    (net (code "220") (name "IO199") (class "Default")
      (node (ref "IC1") (pin "R16") (pinfunction "IO_199_R16") (pintype "bidirectional"))
      (node (ref "JP227") (pin "1") (pinfunction "1_1") (pintype "passive"))
    )
    (net (code "221") (name "IO200") (class "Default")
      (node (ref "IC1") (pin "R17") (pinfunction "IO_200_R17") (pintype "bidirectional"))
      (node (ref "JP229") (pin "1") (pinfunction "1_1") (pintype "passive"))
    )
    (net (code "222") (name "IO201") (class "Default")
      (node (ref "IC1") (pin "R18") (pinfunction "IO_201_R18") (pintype "bidirectional"))
      (node (ref "JP230") (pin "1") (pinfunction "1_1") (pintype "passive"))
    )
    (net (code "223") (name "IO202") (class "Default")
      (node (ref "IC1") (pin "R19") (pinfunction "IO_202_R19") (pintype "bidirectional"))
      (node (ref "JP232") (pin "1") (pinfunction "1_1") (pintype "passive"))
    )
    (net (code "224") (name "IO203") (class "Default")
      (node (ref "IC1") (pin "R20") (pinfunction "IO_203_R20") (pintype "bidirectional"))
      (node (ref "JP231") (pin "1") (pinfunction "1_1") (pintype "passive"))
    )
    (net (code "225") (name "IO204") (class "Default")
      (node (ref "IC1") (pin "R21") (pinfunction "IO_204_R21") (pintype "bidirectional"))
      (node (ref "JP233") (pin "1") (pinfunction "1_1") (pintype "passive"))
    )
    (net (code "226") (name "IO205") (class "Default")
      (node (ref "IC1") (pin "R22") (pinfunction "IO_205_R22") (pintype "bidirectional"))
      (node (ref "JP234") (pin "1") (pinfunction "1_1") (pintype "passive"))
    )
    (net (code "227") (name "IO206") (class "Default")
      (node (ref "IC1") (pin "T3") (pinfunction "IO_206_T3") (pintype "bidirectional"))
      (node (ref "JP235") (pin "1") (pinfunction "1_1") (pintype "passive"))
    )
    (net (code "228") (name "IO207") (class "Default")
      (node (ref "IC1") (pin "T4") (pinfunction "IO_207_T4") (pintype "bidirectional"))
      (node (ref "JP236") (pin "1") (pinfunction "1_1") (pintype "passive"))
    )
    (net (code "229") (name "IO208") (class "Default")
      (node (ref "IC1") (pin "T5") (pinfunction "IO_208_T5") (pintype "bidirectional"))
      (node (ref "JP238") (pin "1") (pinfunction "1_1") (pintype "passive"))
    )
    (net (code "230") (name "IO209") (class "Default")
      (node (ref "IC1") (pin "T7") (pinfunction "IO_209_T7") (pintype "bidirectional"))
      (node (ref "JP237") (pin "1") (pinfunction "1_1") (pintype "passive"))
    )
    (net (code "231") (name "IO210") (class "Default")
      (node (ref "IC1") (pin "T8") (pinfunction "IO_210_T8") (pintype "bidirectional"))
      (node (ref "JP239") (pin "1") (pinfunction "1_1") (pintype "passive"))
    )
    (net (code "232") (name "IO211") (class "Default")
      (node (ref "IC1") (pin "T9") (pinfunction "IO_211_T9") (pintype "bidirectional"))
      (node (ref "JP240") (pin "1") (pinfunction "1_1") (pintype "passive"))
    )
    (net (code "233") (name "IO212") (class "Default")
      (node (ref "IC1") (pin "T10") (pinfunction "IO_212_T10") (pintype "bidirectional"))
      (node (ref "JP242") (pin "1") (pinfunction "1_1") (pintype "passive"))
    )
    (net (code "234") (name "IO213") (class "Default")
      (node (ref "IC1") (pin "T11") (pinfunction "IO_213_T11") (pintype "bidirectional"))
      (node (ref "JP241") (pin "1") (pinfunction "1_1") (pintype "passive"))
    )
    (net (code "235") (name "IO214") (class "Default")
      (node (ref "IC1") (pin "T12") (pinfunction "IO_214_T12") (pintype "bidirectional"))
      (node (ref "JP243") (pin "1") (pinfunction "1_1") (pintype "passive"))
    )
    (net (code "236") (name "IO215") (class "Default")
      (node (ref "IC1") (pin "T13") (pinfunction "IO_215_T13") (pintype "bidirectional"))
      (node (ref "JP244") (pin "1") (pinfunction "1_1") (pintype "passive"))
    )
    (net (code "237") (name "IO216") (class "Default")
      (node (ref "IC1") (pin "T14") (pinfunction "IO_216_T14") (pintype "bidirectional"))
      (node (ref "JP246") (pin "1") (pinfunction "1_1") (pintype "passive"))
    )
    (net (code "238") (name "IO217") (class "Default")
      (node (ref "IC1") (pin "T15") (pinfunction "IO_217_T15") (pintype "bidirectional"))
      (node (ref "JP245") (pin "1") (pinfunction "1_1") (pintype "passive"))
    )
    (net (code "239") (name "IO218") (class "Default")
      (node (ref "IC1") (pin "T16") (pinfunction "IO_218_T16") (pintype "bidirectional"))
      (node (ref "JP247") (pin "1") (pinfunction "1_1") (pintype "passive"))
    )
    (net (code "240") (name "IO219") (class "Default")
      (node (ref "IC1") (pin "T17") (pinfunction "IO_219_T17") (pintype "bidirectional"))
      (node (ref "JP248") (pin "1") (pinfunction "1_1") (pintype "passive"))
    )
    (net (code "241") (name "IO220") (class "Default")
      (node (ref "IC1") (pin "T18") (pinfunction "IO_220_T18") (pintype "bidirectional"))
      (node (ref "JP249") (pin "1") (pinfunction "1_1") (pintype "passive"))
    )
    (net (code "242") (name "IO221") (class "Default")
      (node (ref "IC1") (pin "U1") (pinfunction "IO_221_U1") (pintype "bidirectional"))
      (node (ref "JP250") (pin "1") (pinfunction "1_1") (pintype "passive"))
    )
    (net (code "243") (name "IO222") (class "Default")
      (node (ref "IC1") (pin "U2") (pinfunction "IO_222_U2") (pintype "bidirectional"))
      (node (ref "JP252") (pin "1") (pinfunction "1_1") (pintype "passive"))
    )
    (net (code "244") (name "IO223") (class "Default")
      (node (ref "IC1") (pin "U7") (pinfunction "IO_223_U7") (pintype "bidirectional"))
      (node (ref "JP251") (pin "1") (pinfunction "1_1") (pintype "passive"))
    )
    (net (code "245") (name "IO224") (class "Default")
      (node (ref "IC1") (pin "U8") (pinfunction "IO_224_U8") (pintype "bidirectional"))
      (node (ref "JP253") (pin "1") (pinfunction "1_1") (pintype "passive"))
    )
    (net (code "246") (name "IO225") (class "Default")
      (node (ref "IC1") (pin "U9") (pinfunction "IO_225_U9") (pintype "bidirectional"))
      (node (ref "JP254") (pin "1") (pinfunction "1_1") (pintype "passive"))
    )
    (net (code "247") (name "IO226") (class "Default")
      (node (ref "IC1") (pin "U10") (pinfunction "IO_226_U10") (pintype "bidirectional"))
      (node (ref "JP256") (pin "1") (pinfunction "1_1") (pintype "passive"))
    )
    (net (code "248") (name "IO227") (class "Default")
      (node (ref "IC1") (pin "U11") (pinfunction "IO_227_U11") (pintype "bidirectional"))
      (node (ref "JP255") (pin "1") (pinfunction "1_1") (pintype "passive"))
    )
    (net (code "249") (name "IO228") (class "Default")
      (node (ref "IC1") (pin "U12") (pinfunction "IO_228_U12") (pintype "bidirectional"))
      (node (ref "JP257") (pin "1") (pinfunction "1_1") (pintype "passive"))
    )
    (net (code "250") (name "IO229") (class "Default")
      (node (ref "IC1") (pin "U13") (pinfunction "IO_229_U13") (pintype "bidirectional"))
      (node (ref "JP258") (pin "1") (pinfunction "1_1") (pintype "passive"))
    )
    (net (code "251") (name "IO230") (class "Default")
      (node (ref "IC1") (pin "U14") (pinfunction "IO_230_U14") (pintype "bidirectional"))
      (node (ref "JP260") (pin "1") (pinfunction "1_1") (pintype "passive"))
    )
    (net (code "252") (name "IO231") (class "Default")
      (node (ref "IC1") (pin "U15") (pinfunction "IO_231_U15") (pintype "bidirectional"))
      (node (ref "JP259") (pin "1") (pinfunction "1_1") (pintype "passive"))
    )
    (net (code "253") (name "IO232") (class "Default")
      (node (ref "IC1") (pin "U16") (pinfunction "IO_232_U16") (pintype "bidirectional"))
      (node (ref "JP261") (pin "1") (pinfunction "1_1") (pintype "passive"))
    )
    (net (code "254") (name "IO233") (class "Default")
      (node (ref "IC1") (pin "U17") (pinfunction "IO_233_U17") (pintype "bidirectional"))
      (node (ref "JP262") (pin "1") (pinfunction "1_1") (pintype "passive"))
    )
    (net (code "255") (name "IO234") (class "Default")
      (node (ref "IC1") (pin "U19") (pinfunction "IO_234_U19") (pintype "bidirectional"))
      (node (ref "JP263") (pin "1") (pinfunction "1_1") (pintype "passive"))
    )
    (net (code "256") (name "IO235") (class "Default")
      (node (ref "IC1") (pin "U20") (pinfunction "IO_235_U20") (pintype "bidirectional"))
      (node (ref "JP264") (pin "1") (pinfunction "1_1") (pintype "passive"))
    )
    (net (code "257") (name "IO236") (class "Default")
      (node (ref "IC1") (pin "U21") (pinfunction "IO_236_U21") (pintype "bidirectional"))
      (node (ref "JP266") (pin "1") (pinfunction "1_1") (pintype "passive"))
    )
    (net (code "258") (name "IO237") (class "Default")
      (node (ref "IC1") (pin "U22") (pinfunction "IO_237_U22") (pintype "bidirectional"))
      (node (ref "JP265") (pin "1") (pinfunction "1_1") (pintype "passive"))
    )
    (net (code "259") (name "IO238") (class "Default")
      (node (ref "IC1") (pin "V1") (pinfunction "IO_238_V1") (pintype "bidirectional"))
      (node (ref "JP267") (pin "1") (pinfunction "1_1") (pintype "passive"))
    )
    (net (code "260") (name "IO239") (class "Default")
      (node (ref "IC1") (pin "V2") (pinfunction "IO_239_V2") (pintype "bidirectional"))
      (node (ref "JP268") (pin "1") (pinfunction "1_1") (pintype "passive"))
    )
    (net (code "261") (name "IO240") (class "Default")
      (node (ref "IC1") (pin "V3") (pinfunction "IO_240_V3") (pintype "bidirectional"))
      (node (ref "JP270") (pin "1") (pinfunction "1_1") (pintype "passive"))
    )
    (net (code "262") (name "IO241") (class "Default")
      (node (ref "IC1") (pin "V4") (pinfunction "IO_241_V4") (pintype "bidirectional"))
      (node (ref "JP269") (pin "1") (pinfunction "1_1") (pintype "passive"))
    )
    (net (code "263") (name "IO242") (class "Default")
      (node (ref "IC1") (pin "V5") (pinfunction "IO_242_V5") (pintype "bidirectional"))
      (node (ref "JP271") (pin "1") (pinfunction "1_1") (pintype "passive"))
    )
    (net (code "264") (name "IO243") (class "Default")
      (node (ref "IC1") (pin "V6") (pinfunction "IO_243_V6") (pintype "bidirectional"))
      (node (ref "JP272") (pin "1") (pinfunction "1_1") (pintype "passive"))
    )
    (net (code "265") (name "IO244") (class "Default")
      (node (ref "IC1") (pin "V7") (pinfunction "IO_244_V7") (pintype "bidirectional"))
      (node (ref "JP274") (pin "1") (pinfunction "1_1") (pintype "passive"))
    )
    (net (code "266") (name "IO245") (class "Default")
      (node (ref "IC1") (pin "V8") (pinfunction "IO_245_V8") (pintype "bidirectional"))
      (node (ref "JP273") (pin "1") (pinfunction "1_1") (pintype "passive"))
    )
    (net (code "267") (name "IO246") (class "Default")
      (node (ref "IC1") (pin "V9") (pinfunction "IO_246_V9") (pintype "bidirectional"))
      (node (ref "JP275") (pin "1") (pinfunction "1_1") (pintype "passive"))
    )
    (net (code "268") (name "IO247") (class "Default")
      (node (ref "IC1") (pin "V10") (pinfunction "IO_247_V10") (pintype "bidirectional"))
      (node (ref "JP276") (pin "1") (pinfunction "1_1") (pintype "passive"))
    )
    (net (code "269") (name "IO248") (class "Default")
      (node (ref "IC1") (pin "V11") (pinfunction "IO_248_V11") (pintype "bidirectional"))
      (node (ref "JP277") (pin "1") (pinfunction "1_1") (pintype "passive"))
    )
    (net (code "270") (name "IO249") (class "Default")
      (node (ref "IC1") (pin "V12") (pinfunction "IO_249_V12") (pintype "bidirectional"))
      (node (ref "JP278") (pin "1") (pinfunction "1_1") (pintype "passive"))
    )
    (net (code "271") (name "IO250") (class "Default")
      (node (ref "IC1") (pin "V13") (pinfunction "IO_250_V13") (pintype "bidirectional"))
      (node (ref "JP280") (pin "1") (pinfunction "1_1") (pintype "passive"))
    )
    (net (code "272") (name "IO251") (class "Default")
      (node (ref "IC1") (pin "V14") (pinfunction "IO_251_V14") (pintype "bidirectional"))
      (node (ref "JP279") (pin "1") (pinfunction "1_1") (pintype "passive"))
    )
    (net (code "273") (name "IO252") (class "Default")
      (node (ref "IC1") (pin "V15") (pinfunction "IO_252_V15") (pintype "bidirectional"))
      (node (ref "JP281") (pin "1") (pinfunction "1_1") (pintype "passive"))
    )
    (net (code "274") (name "IO253") (class "Default")
      (node (ref "IC1") (pin "V16") (pinfunction "IO_253_V16") (pintype "bidirectional"))
      (node (ref "JP282") (pin "1") (pinfunction "1_1") (pintype "passive"))
    )
    (net (code "275") (name "IO254") (class "Default")
      (node (ref "IC1") (pin "V21") (pinfunction "IO_254_V21") (pintype "bidirectional"))
      (node (ref "JP284") (pin "1") (pinfunction "1_1") (pintype "passive"))
    )
    (net (code "276") (name "IO255") (class "Default")
      (node (ref "IC1") (pin "V22") (pinfunction "IO_255_V22") (pintype "bidirectional"))
      (node (ref "JP283") (pin "1") (pinfunction "1_1") (pintype "passive"))
    )
    (net (code "277") (name "IO256") (class "Default")
      (node (ref "IC1") (pin "W1") (pinfunction "IO_256_W1") (pintype "bidirectional"))
      (node (ref "JP285") (pin "1") (pinfunction "1_1") (pintype "passive"))
    )
    (net (code "278") (name "IO257") (class "Default")
      (node (ref "IC1") (pin "W2") (pinfunction "IO_257_W2") (pintype "bidirectional"))
      (node (ref "JP286") (pin "1") (pinfunction "1_1") (pintype "passive"))
    )
    (net (code "279") (name "IO258") (class "Default")
      (node (ref "IC1") (pin "W6") (pinfunction "IO_258_W6") (pintype "bidirectional"))
      (node (ref "JP288") (pin "1") (pinfunction "1_1") (pintype "passive"))
    )
    (net (code "280") (name "IO259") (class "Default")
      (node (ref "IC1") (pin "W7") (pinfunction "IO_259_W7") (pintype "bidirectional"))
      (node (ref "JP287") (pin "1") (pinfunction "1_1") (pintype "passive"))
    )
    (net (code "281") (name "IO260") (class "Default")
      (node (ref "IC1") (pin "W8") (pinfunction "IO_260_W8") (pintype "bidirectional"))
      (node (ref "JP289") (pin "1") (pinfunction "1_1") (pintype "passive"))
    )
    (net (code "282") (name "IO261") (class "Default")
      (node (ref "IC1") (pin "W10") (pinfunction "IO_261_W10") (pintype "bidirectional"))
      (node (ref "JP290") (pin "1") (pinfunction "1_1") (pintype "passive"))
    )
    (net (code "283") (name "IO262") (class "Default")
      (node (ref "IC1") (pin "W13") (pinfunction "IO_262_W13") (pintype "bidirectional"))
      (node (ref "JP291") (pin "1") (pinfunction "1_1") (pintype "passive"))
    )
    (net (code "284") (name "IO263") (class "Default")
      (node (ref "IC1") (pin "W14") (pinfunction "IO_263_W14") (pintype "bidirectional"))
      (node (ref "JP292") (pin "1") (pinfunction "1_1") (pintype "passive"))
    )
    (net (code "285") (name "IO264") (class "Default")
      (node (ref "IC1") (pin "W15") (pinfunction "IO_264_W15") (pintype "bidirectional"))
      (node (ref "JP294") (pin "1") (pinfunction "1_1") (pintype "passive"))
    )
    (net (code "286") (name "IO265") (class "Default")
      (node (ref "IC1") (pin "W17") (pinfunction "IO_265_W17") (pintype "bidirectional"))
      (node (ref "JP293") (pin "1") (pinfunction "1_1") (pintype "passive"))
    )
    (net (code "287") (name "IO266") (class "Default")
      (node (ref "IC1") (pin "W19") (pinfunction "IO_266_W19") (pintype "bidirectional"))
      (node (ref "JP295") (pin "1") (pinfunction "1_1") (pintype "passive"))
    )
    (net (code "288") (name "IO267") (class "Default")
      (node (ref "IC1") (pin "W20") (pinfunction "IO_267_W20") (pintype "bidirectional"))
      (node (ref "JP296") (pin "1") (pinfunction "1_1") (pintype "passive"))
    )
    (net (code "289") (name "IO268") (class "Default")
      (node (ref "IC1") (pin "W21") (pinfunction "IO_268_W21") (pintype "bidirectional"))
      (node (ref "JP298") (pin "1") (pinfunction "1_1") (pintype "passive"))
    )
    (net (code "290") (name "IO269") (class "Default")
      (node (ref "IC1") (pin "W22") (pinfunction "IO_269_W22") (pintype "bidirectional"))
      (node (ref "JP297") (pin "1") (pinfunction "1_1") (pintype "passive"))
    )
    (net (code "291") (name "IO270") (class "Default")
      (node (ref "IC1") (pin "Y1") (pinfunction "IO_270_Y1") (pintype "bidirectional"))
      (node (ref "JP299") (pin "1") (pinfunction "1_1") (pintype "passive"))
    )
    (net (code "292") (name "IO271") (class "Default")
      (node (ref "IC1") (pin "Y2") (pinfunction "IO_271_Y2") (pintype "bidirectional"))
      (node (ref "JP300") (pin "1") (pinfunction "1_1") (pintype "passive"))
    )
    (net (code "293") (name "IO272") (class "Default")
      (node (ref "IC1") (pin "Y3") (pinfunction "IO_272_Y3") (pintype "bidirectional"))
      (node (ref "JP302") (pin "1") (pinfunction "1_1") (pintype "passive"))
    )
    (net (code "294") (name "IO273") (class "Default")
      (node (ref "IC1") (pin "Y4") (pinfunction "IO_273_Y4") (pintype "bidirectional"))
      (node (ref "JP301") (pin "1") (pinfunction "1_1") (pintype "passive"))
    )
    (net (code "295") (name "IO274") (class "Default")
      (node (ref "IC1") (pin "Y6") (pinfunction "IO_274_Y6") (pintype "bidirectional"))
      (node (ref "JP303") (pin "1") (pinfunction "1_1") (pintype "passive"))
    )
    (net (code "296") (name "IO275") (class "Default")
      (node (ref "IC1") (pin "Y7") (pinfunction "IO_275_Y7") (pintype "bidirectional"))
      (node (ref "JP304") (pin "1") (pinfunction "1_1") (pintype "passive"))
    )
    (net (code "297") (name "IO276") (class "Default")
      (node (ref "IC1") (pin "Y8") (pinfunction "IO_276_Y8") (pintype "bidirectional"))
      (node (ref "JP305") (pin "1") (pinfunction "1_1") (pintype "passive"))
    )
    (net (code "298") (name "IO277") (class "Default")
      (node (ref "IC1") (pin "Y10") (pinfunction "IO_277_Y10") (pintype "bidirectional"))
      (node (ref "JP306") (pin "1") (pinfunction "1_1") (pintype "passive"))
    )
    (net (code "299") (name "IO278") (class "Default")
      (node (ref "IC1") (pin "Y13") (pinfunction "IO_278_Y13") (pintype "bidirectional"))
      (node (ref "JP308") (pin "1") (pinfunction "1_1") (pintype "passive"))
    )
    (net (code "300") (name "IO279") (class "Default")
      (node (ref "IC1") (pin "Y17") (pinfunction "IO_279_Y17") (pintype "bidirectional"))
      (node (ref "JP307") (pin "1") (pinfunction "1_1") (pintype "passive"))
    )
    (net (code "301") (name "IO280") (class "Default")
      (node (ref "IC1") (pin "Y21") (pinfunction "IO_280_Y21") (pintype "bidirectional"))
      (node (ref "JP309") (pin "1") (pinfunction "1_1") (pintype "passive"))
    )
    (net (code "302") (name "IO281") (class "Default")
      (node (ref "IC1") (pin "Y22") (pinfunction "IO_281_Y22") (pintype "bidirectional"))
      (node (ref "JP310") (pin "1") (pinfunction "1_1") (pintype "passive"))
    )
    (net (code "303") (name "IO282") (class "Default")
      (node (ref "IC1") (pin "AA1") (pinfunction "IO_282_AA1") (pintype "bidirectional"))
      (node (ref "JP312") (pin "1") (pinfunction "1_1") (pintype "passive"))
    )
    (net (code "304") (name "IO283") (class "Default")
      (node (ref "IC1") (pin "AA3") (pinfunction "IO_283_AA3") (pintype "bidirectional"))
      (node (ref "JP311") (pin "1") (pinfunction "1_1") (pintype "passive"))
    )
    (net (code "305") (name "IO284") (class "Default")
      (node (ref "IC1") (pin "AA4") (pinfunction "IO_284_AA4") (pintype "bidirectional"))
      (node (ref "JP313") (pin "1") (pinfunction "1_1") (pintype "passive"))
    )
    (net (code "306") (name "IO285") (class "Default")
      (node (ref "IC1") (pin "AA5") (pinfunction "IO_285_AA5") (pintype "bidirectional"))
      (node (ref "JP314") (pin "1") (pinfunction "1_1") (pintype "passive"))
    )
    (net (code "307") (name "IO286") (class "Default")
      (node (ref "IC1") (pin "AA7") (pinfunction "IO_286_AA7") (pintype "bidirectional"))
      (node (ref "JP316") (pin "1") (pinfunction "1_1") (pintype "passive"))
    )
    (net (code "308") (name "IO287") (class "Default")
      (node (ref "IC1") (pin "AA8") (pinfunction "IO_287_AA8") (pintype "bidirectional"))
      (node (ref "JP315") (pin "1") (pinfunction "1_1") (pintype "passive"))
    )
    (net (code "309") (name "IO288") (class "Default")
      (node (ref "IC1") (pin "AA9") (pinfunction "IO_288_AA9") (pintype "bidirectional"))
      (node (ref "JP317") (pin "1") (pinfunction "1_1") (pintype "passive"))
    )
    (net (code "310") (name "IO289") (class "Default")
      (node (ref "IC1") (pin "AA10") (pinfunction "IO_289_AA10") (pintype "bidirectional"))
      (node (ref "JP318") (pin "1") (pinfunction "1_1") (pintype "passive"))
    )
    (net (code "311") (name "IO290") (class "Default")
      (node (ref "IC1") (pin "AA13") (pinfunction "IO_290_AA13") (pintype "bidirectional"))
      (node (ref "JP319") (pin "1") (pinfunction "1_1") (pintype "passive"))
    )
    (net (code "312") (name "IO291") (class "Default")
      (node (ref "IC1") (pin "AA14") (pinfunction "IO_291_AA14") (pintype "bidirectional"))
      (node (ref "JP320") (pin "1") (pinfunction "1_1") (pintype "passive"))
    )
    (net (code "313") (name "IO292") (class "Default")
      (node (ref "IC1") (pin "AA15") (pinfunction "IO_292_AA15") (pintype "bidirectional"))
      (node (ref "JP322") (pin "1") (pinfunction "1_1") (pintype "passive"))
    )
    (net (code "314") (name "IO293") (class "Default")
      (node (ref "IC1") (pin "AA16") (pinfunction "IO_293_AA16") (pintype "bidirectional"))
      (node (ref "JP321") (pin "1") (pinfunction "1_1") (pintype "passive"))
    )
    (net (code "315") (name "IO294") (class "Default")
      (node (ref "IC1") (pin "AA17") (pinfunction "IO_294_AA17") (pintype "bidirectional"))
      (node (ref "JP323") (pin "1") (pinfunction "1_1") (pintype "passive"))
    )
    (net (code "316") (name "IO295") (class "Default")
      (node (ref "IC1") (pin "AA18") (pinfunction "IO_295_AA18") (pintype "bidirectional"))
      (node (ref "JP324") (pin "1") (pinfunction "1_1") (pintype "passive"))
    )
    (net (code "317") (name "IO296") (class "Default")
      (node (ref "IC1") (pin "AA19") (pinfunction "IO_296_AA19") (pintype "bidirectional"))
      (node (ref "JP326") (pin "1") (pinfunction "1_1") (pintype "passive"))
    )
    (net (code "318") (name "IO297") (class "Default")
      (node (ref "IC1") (pin "AA20") (pinfunction "IO_297_AA20") (pintype "bidirectional"))
      (node (ref "JP325") (pin "1") (pinfunction "1_1") (pintype "passive"))
    )
    (net (code "319") (name "IO298") (class "Default")
      (node (ref "IC1") (pin "AA21") (pinfunction "IO_298_AA21") (pintype "bidirectional"))
      (node (ref "JP327") (pin "1") (pinfunction "1_1") (pintype "passive"))
    )
    (net (code "320") (name "IO299") (class "Default")
      (node (ref "IC1") (pin "AB3") (pinfunction "IO_299_AB3") (pintype "bidirectional"))
      (node (ref "JP328") (pin "1") (pinfunction "1_1") (pintype "passive"))
    )
    (net (code "321") (name "IO300") (class "Default")
      (node (ref "IC1") (pin "AB4") (pinfunction "IO_300_AB4") (pintype "bidirectional"))
      (node (ref "JP330") (pin "1") (pinfunction "1_1") (pintype "passive"))
    )
    (net (code "322") (name "IO301") (class "Default")
      (node (ref "IC1") (pin "AB5") (pinfunction "IO_301_AB5") (pintype "bidirectional"))
      (node (ref "JP329") (pin "1") (pinfunction "1_1") (pintype "passive"))
    )
    (net (code "323") (name "IO302") (class "Default")
      (node (ref "IC1") (pin "AB7") (pinfunction "IO_302_AB7") (pintype "bidirectional"))
      (node (ref "JP331") (pin "1") (pinfunction "1_1") (pintype "passive"))
    )
    (net (code "324") (name "IO303") (class "Default")
      (node (ref "IC1") (pin "AB8") (pinfunction "IO_303_AB8") (pintype "bidirectional"))
      (node (ref "JP332") (pin "1") (pinfunction "1_1") (pintype "passive"))
    )
    (net (code "325") (name "IO304") (class "Default")
      (node (ref "IC1") (pin "AB9") (pinfunction "IO_304_AB9") (pintype "bidirectional"))
      (node (ref "JP333") (pin "1") (pinfunction "1_1") (pintype "passive"))
    )
    (net (code "326") (name "IO305") (class "Default")
      (node (ref "IC1") (pin "AB10") (pinfunction "IO_305_AB10") (pintype "bidirectional"))
      (node (ref "JP334") (pin "1") (pinfunction "1_1") (pintype "passive"))
    )
    (net (code "327") (name "IO306") (class "Default")
      (node (ref "IC1") (pin "AB13") (pinfunction "IO_306_AB13") (pintype "bidirectional"))
      (node (ref "JP336") (pin "1") (pinfunction "1_1") (pintype "passive"))
    )
    (net (code "328") (name "IO307") (class "Default")
      (node (ref "IC1") (pin "AB14") (pinfunction "IO_307_AB14") (pintype "bidirectional"))
      (node (ref "JP335") (pin "1") (pinfunction "1_1") (pintype "passive"))
    )
    (net (code "329") (name "IO308") (class "Default")
      (node (ref "IC1") (pin "AB15") (pinfunction "IO_308_AB15") (pintype "bidirectional"))
      (node (ref "JP337") (pin "1") (pinfunction "1_1") (pintype "passive"))
    )
    (net (code "330") (name "IO309") (class "Default")
      (node (ref "IC1") (pin "AB16") (pinfunction "IO_309_AB16") (pintype "bidirectional"))
      (node (ref "JP338") (pin "1") (pinfunction "1_1") (pintype "passive"))
    )
    (net (code "331") (name "IO310") (class "Default")
      (node (ref "IC1") (pin "AB17") (pinfunction "IO_310_AB17") (pintype "bidirectional"))
      (node (ref "JP340") (pin "1") (pinfunction "1_1") (pintype "passive"))
    )
    (net (code "332") (name "IO311") (class "Default")
      (node (ref "IC1") (pin "AB18") (pinfunction "IO_311_AB18") (pintype "bidirectional"))
      (node (ref "JP339") (pin "1") (pinfunction "1_1") (pintype "passive"))
    )
    (net (code "333") (name "IO312") (class "Default")
      (node (ref "IC1") (pin "AB19") (pinfunction "IO_312_AB19") (pintype "bidirectional"))
      (node (ref "JP341") (pin "1") (pinfunction "1_1") (pintype "passive"))
    )
    (net (code "334") (name "IO313") (class "Default")
      (node (ref "IC1") (pin "AB20") (pinfunction "IO_313_AB20") (pintype "bidirectional"))
      (node (ref "JP342") (pin "1") (pinfunction "1_1") (pintype "passive"))
    )
    (net (code "335") (name "MSEL0") (class "Default")
      (node (ref "IC1") (pin "M17") (pinfunction "MSEL0_M17") (pintype "bidirectional"))
      (node (ref "R6") (pin "P$1") (pinfunction "P$1_P$1") (pintype "bidirectional"))
    )
    (net (code "336") (name "MSEL1") (class "Default")
      (node (ref "IC1") (pin "L18") (pinfunction "MSEL1_L18") (pintype "bidirectional"))
      (node (ref "R7") (pin "P$1") (pinfunction "P$1_P$1") (pintype "bidirectional"))
    )
    (net (code "337") (name "MSEL2") (class "Default")
      (node (ref "IC1") (pin "L17") (pinfunction "MSEL2_L17") (pintype "bidirectional"))
      (node (ref "R8") (pin "P$1") (pinfunction "P$1_P$1") (pintype "bidirectional"))
    )
    (net (code "338") (name "MSEL3") (class "Default")
      (node (ref "IC1") (pin "K20") (pinfunction "MSEL3_K20") (pintype "bidirectional"))
      (node (ref "R9") (pin "P$1") (pinfunction "P$1_P$1") (pintype "bidirectional"))
    )
    (net (code "339") (name "NCE") (class "Default")
      (node (ref "IC1") (pin "L3") (pinfunction "NCE_L3") (pintype "bidirectional"))
      (node (ref "R4") (pin "P$1") (pinfunction "P$1_P$1") (pintype "bidirectional"))
    )
    (net (code "340") (name "NCONFIG") (class "Default")
      (node (ref "IC1") (pin "K5") (pinfunction "NCONFIG_K5") (pintype "bidirectional"))
      (node (ref "R2") (pin "P$1") (pinfunction "P$1_P$1") (pintype "bidirectional"))
      (node (ref "SW1") (pin "2") (pinfunction "A1_2") (pintype "bidirectional"))
    )
    (net (code "341") (name "NCSO") (class "Default")
      (node (ref "IC1") (pin "E2") (pinfunction "IO_65_E2") (pintype "bidirectional"))
      (node (ref "IC2") (pin "1") (pinfunction "NCS_1") (pintype "bidirectional"))
      (node (ref "JP54") (pin "1") (pinfunction "1_1") (pintype "passive"))
    )
    (net (code "342") (name "NSTATUS") (class "Default")
      (node (ref "IC1") (pin "K6") (pinfunction "NSTATUS_K6") (pintype "bidirectional"))
      (node (ref "R5") (pin "P$1") (pinfunction "P$1_P$1") (pintype "bidirectional"))
    )
    (net (code "343") (name "Net-(LED33-PadA)") (class "Default")
      (node (ref "LED33") (pin "A") (pinfunction "A_A") (pintype "passive"))
      (node (ref "R45") (pin "P$2") (pinfunction "P$2_P$2") (pintype "bidirectional"))
    )
    (net (code "344") (name "Net-(LED34-PadA)") (class "Default")
      (node (ref "LED34") (pin "A") (pinfunction "A_A") (pintype "passive"))
      (node (ref "R44") (pin "P$2") (pinfunction "P$2_P$2") (pintype "bidirectional"))
    )
    (net (code "345") (name "Net-(LED35-PadA)") (class "Default")
      (node (ref "LED35") (pin "A") (pinfunction "A_A") (pintype "passive"))
      (node (ref "R43") (pin "P$2") (pinfunction "P$2_P$2") (pintype "bidirectional"))
    )
    (net (code "346") (name "Net-(LED36-PadA)") (class "Default")
      (node (ref "LED36") (pin "A") (pinfunction "A_A") (pintype "passive"))
      (node (ref "R42") (pin "P$2") (pinfunction "P$2_P$2") (pintype "bidirectional"))
    )
    (net (code "347") (name "Net-(LED37-PadA)") (class "Default")
      (node (ref "LED37") (pin "A") (pinfunction "A_A") (pintype "passive"))
      (node (ref "R41") (pin "P$2") (pinfunction "P$2_P$2") (pintype "bidirectional"))
    )
    (net (code "348") (name "Net-(LED38-PadA)") (class "Default")
      (node (ref "LED38") (pin "A") (pinfunction "A_A") (pintype "passive"))
      (node (ref "R40") (pin "P$2") (pinfunction "P$2_P$2") (pintype "bidirectional"))
    )
    (net (code "349") (name "Net-(LED39-PadA)") (class "Default")
      (node (ref "LED39") (pin "A") (pinfunction "A_A") (pintype "passive"))
      (node (ref "R39") (pin "P$2") (pinfunction "P$2_P$2") (pintype "bidirectional"))
    )
    (net (code "350") (name "Net-(LED40-PadA)") (class "Default")
      (node (ref "LED40") (pin "A") (pinfunction "A_A") (pintype "passive"))
      (node (ref "R38") (pin "P$2") (pinfunction "P$2_P$2") (pintype "bidirectional"))
    )
    (net (code "351") (name "TCK") (class "Default")
      (node (ref "IC1") (pin "L2") (pinfunction "TCK_L2") (pintype "bidirectional"))
      (node (ref "J1") (pin "1") (pinfunction "1_1") (pintype "passive"))
      (node (ref "R12") (pin "P$2") (pinfunction "P$2_P$2") (pintype "bidirectional"))
    )
    (net (code "352") (name "TDI") (class "Default")
      (node (ref "IC1") (pin "L5") (pinfunction "TDI_L5") (pintype "bidirectional"))
      (node (ref "J1") (pin "9") (pinfunction "9_9") (pintype "passive"))
      (node (ref "R11") (pin "P$1") (pinfunction "P$1_P$1") (pintype "bidirectional"))
    )
    (net (code "353") (name "TDO") (class "Default")
      (node (ref "IC1") (pin "L4") (pinfunction "TDO_L4") (pintype "bidirectional"))
      (node (ref "J1") (pin "3") (pinfunction "3_3") (pintype "passive"))
    )
    (net (code "354") (name "TMS") (class "Default")
      (node (ref "IC1") (pin "L1") (pinfunction "TMS_L1") (pintype "bidirectional"))
      (node (ref "J1") (pin "5") (pinfunction "5_5") (pintype "passive"))
      (node (ref "R10") (pin "P$1") (pinfunction "P$1_P$1") (pintype "bidirectional"))
    )
    (net (code "355") (name "VCCA") (class "Default")
      (node (ref "C26") (pin "2") (pinfunction "2_2") (pintype "passive"))
      (node (ref "IC1") (pin "F18") (pinfunction "VCCA2_F18") (pintype "bidirectional"))
      (node (ref "IC1") (pin "G6") (pinfunction "VCCA3_G6") (pintype "bidirectional"))
      (node (ref "IC1") (pin "T6") (pinfunction "VCCA1_T6") (pintype "bidirectional"))
      (node (ref "IC1") (pin "U18") (pinfunction "VCCA4_U18") (pintype "bidirectional"))
      (node (ref "R20") (pin "P$2") (pinfunction "P$2_P$2") (pintype "bidirectional"))
    )
    (net (code "356") (name "VCCINT") (class "Default")
      (node (ref "C24") (pin "2") (pinfunction "2_2") (pintype "passive"))
      (node (ref "IC1") (pin "G12") (pinfunction "VCCINT_1_G12") (pintype "bidirectional"))
      (node (ref "IC1") (pin "H9") (pinfunction "VCCINT_2_H9") (pintype "bidirectional"))
      (node (ref "IC1") (pin "J10") (pinfunction "VCCINT_3_J10") (pintype "bidirectional"))
      (node (ref "IC1") (pin "J11") (pinfunction "VCCINT_4_J11") (pintype "bidirectional"))
      (node (ref "IC1") (pin "J12") (pinfunction "VCCINT_5_J12") (pintype "bidirectional"))
      (node (ref "IC1") (pin "J13") (pinfunction "VCCINT_6_J13") (pintype "bidirectional"))
      (node (ref "IC1") (pin "J14") (pinfunction "VCCINT_7_J14") (pintype "bidirectional"))
      (node (ref "IC1") (pin "J16") (pinfunction "VCCINT_8_J16") (pintype "bidirectional"))
      (node (ref "IC1") (pin "K14") (pinfunction "VCCINT_10_K14") (pintype "bidirectional"))
      (node (ref "IC1") (pin "K15") (pinfunction "VCCINT_11_K15") (pintype "bidirectional"))
      (node (ref "IC1") (pin "K9") (pinfunction "VCCINT_9_K9") (pintype "bidirectional"))
      (node (ref "IC1") (pin "L14") (pinfunction "VCCINT_13_L14") (pintype "bidirectional"))
      (node (ref "IC1") (pin "L16") (pinfunction "VCCINT_14_L16") (pintype "bidirectional"))
      (node (ref "IC1") (pin "L9") (pinfunction "VCCINT_12_L9") (pintype "bidirectional"))
      (node (ref "IC1") (pin "M14") (pinfunction "VCCINT_16_M14") (pintype "bidirectional"))
      (node (ref "IC1") (pin "M15") (pinfunction "VCCINT_17_M15") (pintype "bidirectional"))
      (node (ref "IC1") (pin "M9") (pinfunction "VCCINT_15_M9") (pintype "bidirectional"))
      (node (ref "IC1") (pin "N14") (pinfunction "VCCINT_19_N14") (pintype "bidirectional"))
      (node (ref "IC1") (pin "N9") (pinfunction "VCCINT_18_N9") (pintype "bidirectional"))
      (node (ref "IC1") (pin "P10") (pinfunction "VCCINT_21_P10") (pintype "bidirectional"))
      (node (ref "IC1") (pin "P11") (pinfunction "VCCINT_22_P11") (pintype "bidirectional"))
      (node (ref "IC1") (pin "P12") (pinfunction "VCCINT_23_P12") (pintype "bidirectional"))
      (node (ref "IC1") (pin "P13") (pinfunction "VCCINT_24_P13") (pintype "bidirectional"))
      (node (ref "IC1") (pin "P14") (pinfunction "VCCINT_25_P14") (pintype "bidirectional"))
      (node (ref "IC1") (pin "P9") (pinfunction "VCCINT_20_P9") (pintype "bidirectional"))
      (node (ref "IC1") (pin "R10") (pinfunction "VCCINT_27_R10") (pintype "bidirectional"))
      (node (ref "IC1") (pin "R12") (pinfunction "VCCINT_28_R12") (pintype "bidirectional"))
      (node (ref "IC1") (pin "R8") (pinfunction "VCCINT_26_R8") (pintype "bidirectional"))
      (node (ref "R18") (pin "P$2") (pinfunction "P$2_P$2") (pintype "bidirectional"))
    )
    (net (code "357") (name "VCCIO") (class "Default")
      (node (ref "C16") (pin "2") (pinfunction "2_2") (pintype "passive"))
      (node (ref "C17") (pin "2") (pinfunction "2_2") (pintype "passive"))
      (node (ref "C18") (pin "2") (pinfunction "2_2") (pintype "passive"))
      (node (ref "C19") (pin "2") (pinfunction "2_2") (pintype "passive"))
      (node (ref "C20") (pin "2") (pinfunction "2_2") (pintype "passive"))
      (node (ref "C21") (pin "2") (pinfunction "2_2") (pintype "passive"))
      (node (ref "C22") (pin "2") (pinfunction "2_2") (pintype "passive"))
      (node (ref "C23") (pin "2") (pinfunction "2_2") (pintype "passive"))
      (node (ref "IC1") (pin "A2") (pinfunction "VCCIO8_1_A2") (pintype "bidirectional"))
      (node (ref "IC1") (pin "A21") (pinfunction "VCCIO7_1_A21") (pintype "bidirectional"))
      (node (ref "IC1") (pin "AA6") (pinfunction "VCCIO3_4_AA6") (pintype "bidirectional"))
      (node (ref "IC1") (pin "AB2") (pinfunction "VCCIO3_5_AB2") (pintype "bidirectional"))
      (node (ref "IC1") (pin "AB21") (pinfunction "VCCIO4_5_AB21") (pintype "bidirectional"))
      (node (ref "IC1") (pin "D11") (pinfunction "VCCIO8_4_D11") (pintype "bidirectional"))
      (node (ref "IC1") (pin "D12") (pinfunction "VCCIO7_2_D12") (pintype "bidirectional"))
      (node (ref "IC1") (pin "D14") (pinfunction "VCCIO7_3_D14") (pintype "bidirectional"))
      (node (ref "IC1") (pin "D16") (pinfunction "VCCIO7_4_D16") (pintype "bidirectional"))
      (node (ref "IC1") (pin "D18") (pinfunction "VCCIO7_5_D18") (pintype "bidirectional"))
      (node (ref "IC1") (pin "D4") (pinfunction "VCCIO1_1_D4") (pintype "bidirectional"))
      (node (ref "IC1") (pin "D5") (pinfunction "VCCIO8_2_D5") (pintype "bidirectional"))
      (node (ref "IC1") (pin "D9") (pinfunction "VCCIO8_3_D9") (pintype "bidirectional"))
      (node (ref "IC1") (pin "E19") (pinfunction "VCCIO6_1_E19") (pintype "bidirectional"))
      (node (ref "IC1") (pin "E8") (pinfunction "VCCIO8_5_E8") (pintype "bidirectional"))
      (node (ref "IC1") (pin "F4") (pinfunction "VCCIO1_2_F4") (pintype "bidirectional"))
      (node (ref "IC1") (pin "G19") (pinfunction "VCCIO6_2_G19") (pintype "bidirectional"))
      (node (ref "IC1") (pin "H4") (pinfunction "VCCIO1_3_H4") (pintype "bidirectional"))
      (node (ref "IC1") (pin "J20") (pinfunction "VCCIO6_3_J20") (pintype "bidirectional"))
      (node (ref "IC1") (pin "K4") (pinfunction "VCCIO1_4_K4") (pintype "bidirectional"))
      (node (ref "IC1") (pin "L19") (pinfunction "VCCIO6_4_L19") (pintype "bidirectional"))
      (node (ref "IC1") (pin "N4") (pinfunction "VCCIO2_1_N4") (pintype "bidirectional"))
      (node (ref "IC1") (pin "P18") (pinfunction "VCCIO5_1_P18") (pintype "bidirectional"))
      (node (ref "IC1") (pin "R4") (pinfunction "VCCIO2_2_R4") (pintype "bidirectional"))
      (node (ref "IC1") (pin "T19") (pinfunction "VCCIO5_2_T19") (pintype "bidirectional"))
      (node (ref "IC1") (pin "U4") (pinfunction "VCCIO2_3_U4") (pintype "bidirectional"))
      (node (ref "IC1") (pin "V19") (pinfunction "VCCIO5_3_V19") (pintype "bidirectional"))
      (node (ref "IC1") (pin "W11") (pinfunction "VCCIO3_3_W11") (pintype "bidirectional"))
      (node (ref "IC1") (pin "W12") (pinfunction "VCCIO4_1_W12") (pintype "bidirectional"))
      (node (ref "IC1") (pin "W16") (pinfunction "VCCIO4_2_W16") (pintype "bidirectional"))
      (node (ref "IC1") (pin "W18") (pinfunction "VCCIO4_3_W18") (pintype "bidirectional"))
      (node (ref "IC1") (pin "W4") (pinfunction "VCCIO2_4_W4") (pintype "bidirectional"))
      (node (ref "IC1") (pin "W5") (pinfunction "VCCIO3_1_W5") (pintype "bidirectional"))
      (node (ref "IC1") (pin "W9") (pinfunction "VCCIO3_2_W9") (pintype "bidirectional"))
      (node (ref "IC1") (pin "Y14") (pinfunction "VCCIO4_4_Y14") (pintype "bidirectional"))
      (node (ref "IC1") (pin "Y19") (pinfunction "VCCIO5_4_Y19") (pintype "bidirectional"))
      (node (ref "R17") (pin "P$2") (pinfunction "P$2_P$2") (pintype "bidirectional"))
    )
    (net (code "358") (name "VCCPLL") (class "Default")
      (node (ref "C25") (pin "2") (pinfunction "2_2") (pintype "passive"))
      (node (ref "IC1") (pin "E17") (pinfunction "VCCD_PLL2_E17") (pintype "bidirectional"))
      (node (ref "IC1") (pin "F6") (pinfunction "VCCD_PLL3_F6") (pintype "bidirectional"))
      (node (ref "IC1") (pin "U6") (pinfunction "VCCD_PLL1_U6") (pintype "bidirectional"))
      (node (ref "IC1") (pin "V17") (pinfunction "VCCD_PLL4_V17") (pintype "bidirectional"))
      (node (ref "R19") (pin "P$2") (pinfunction "P$2_P$2") (pintype "bidirectional"))
    )
    (net (code "359") (name "unconnected-(J1-Pad6)") (class "Default")
      (node (ref "J1") (pin "6") (pinfunction "6_6") (pintype "passive"))
    )
    (net (code "360") (name "unconnected-(J1-Pad7)") (class "Default")
      (node (ref "J1") (pin "7") (pinfunction "7_7") (pintype "passive"))
    )
    (net (code "361") (name "unconnected-(J1-Pad8)") (class "Default")
      (node (ref "J1") (pin "8") (pinfunction "8_8") (pintype "passive"))
    )
    (net (code "362") (name "unconnected-(SW1-A0-Pad1)") (class "Default")
      (node (ref "SW1") (pin "1") (pinfunction "A0_1") (pintype "bidirectional"))
    )
    (net (code "363") (name "unconnected-(SW1-B0-Pad3)") (class "Default")
      (node (ref "SW1") (pin "3") (pinfunction "B0_3") (pintype "bidirectional"))
    )
    (net (code "364") (name "unconnected-(SW2-A0-Pad1)") (class "Default")
      (node (ref "SW2") (pin "1") (pinfunction "A0_1") (pintype "bidirectional"))
    )
    (net (code "365") (name "unconnected-(SW2-B0-Pad3)") (class "Default")
      (node (ref "SW2") (pin "3") (pinfunction "B0_3") (pintype "bidirectional"))
    )
    (net (code "366") (name "unconnected-(Y1-EN-Pad1)") (class "Default")
      (node (ref "Y1") (pin "1") (pinfunction "EN_1") (pintype "bidirectional"))
    )
  )
)
